# CH555-R0-1v0.net
KiCad netlist of a schematic drawn in Altium Designer
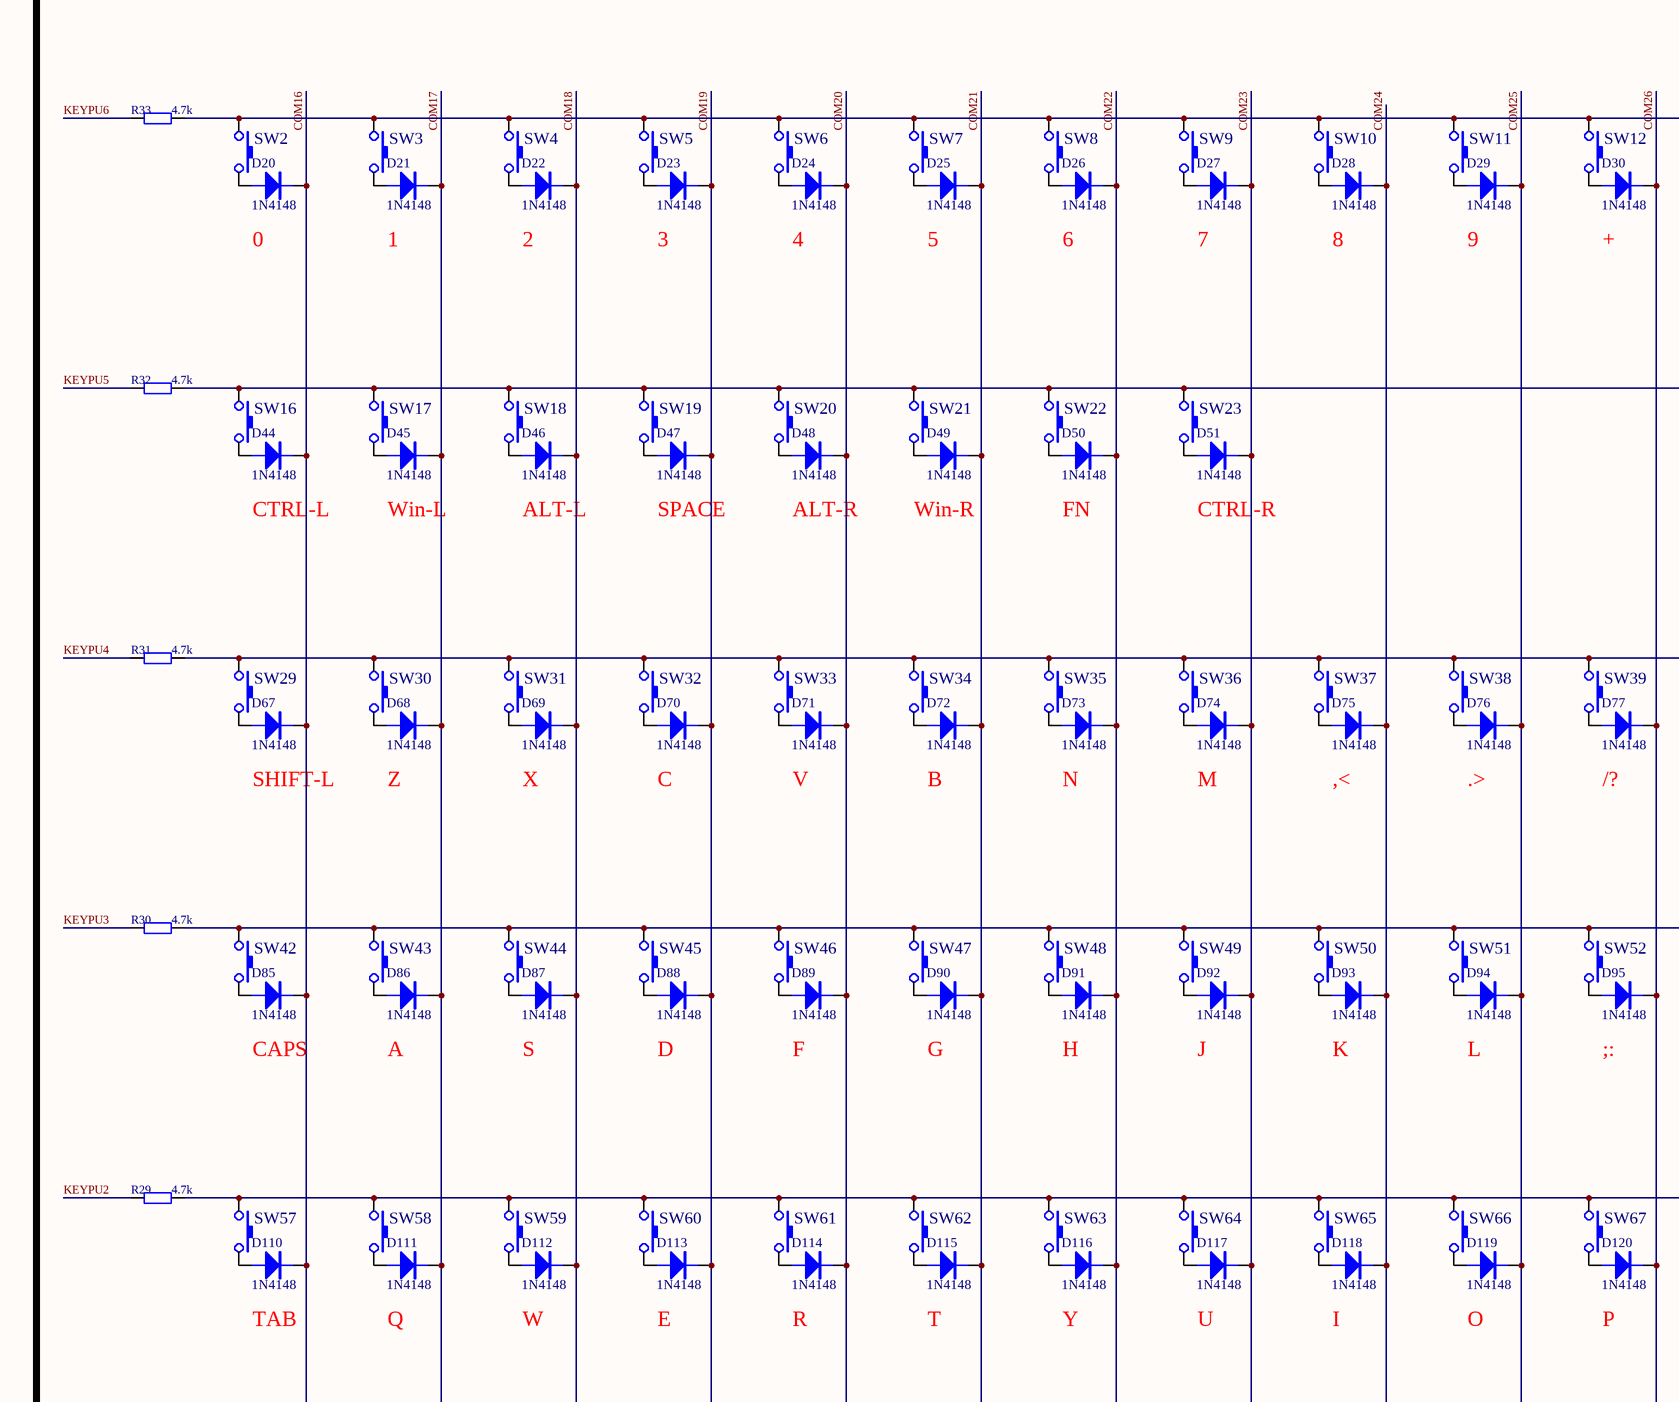
[diagram p0: CH555-R0-1v0.SchDoc, top left]
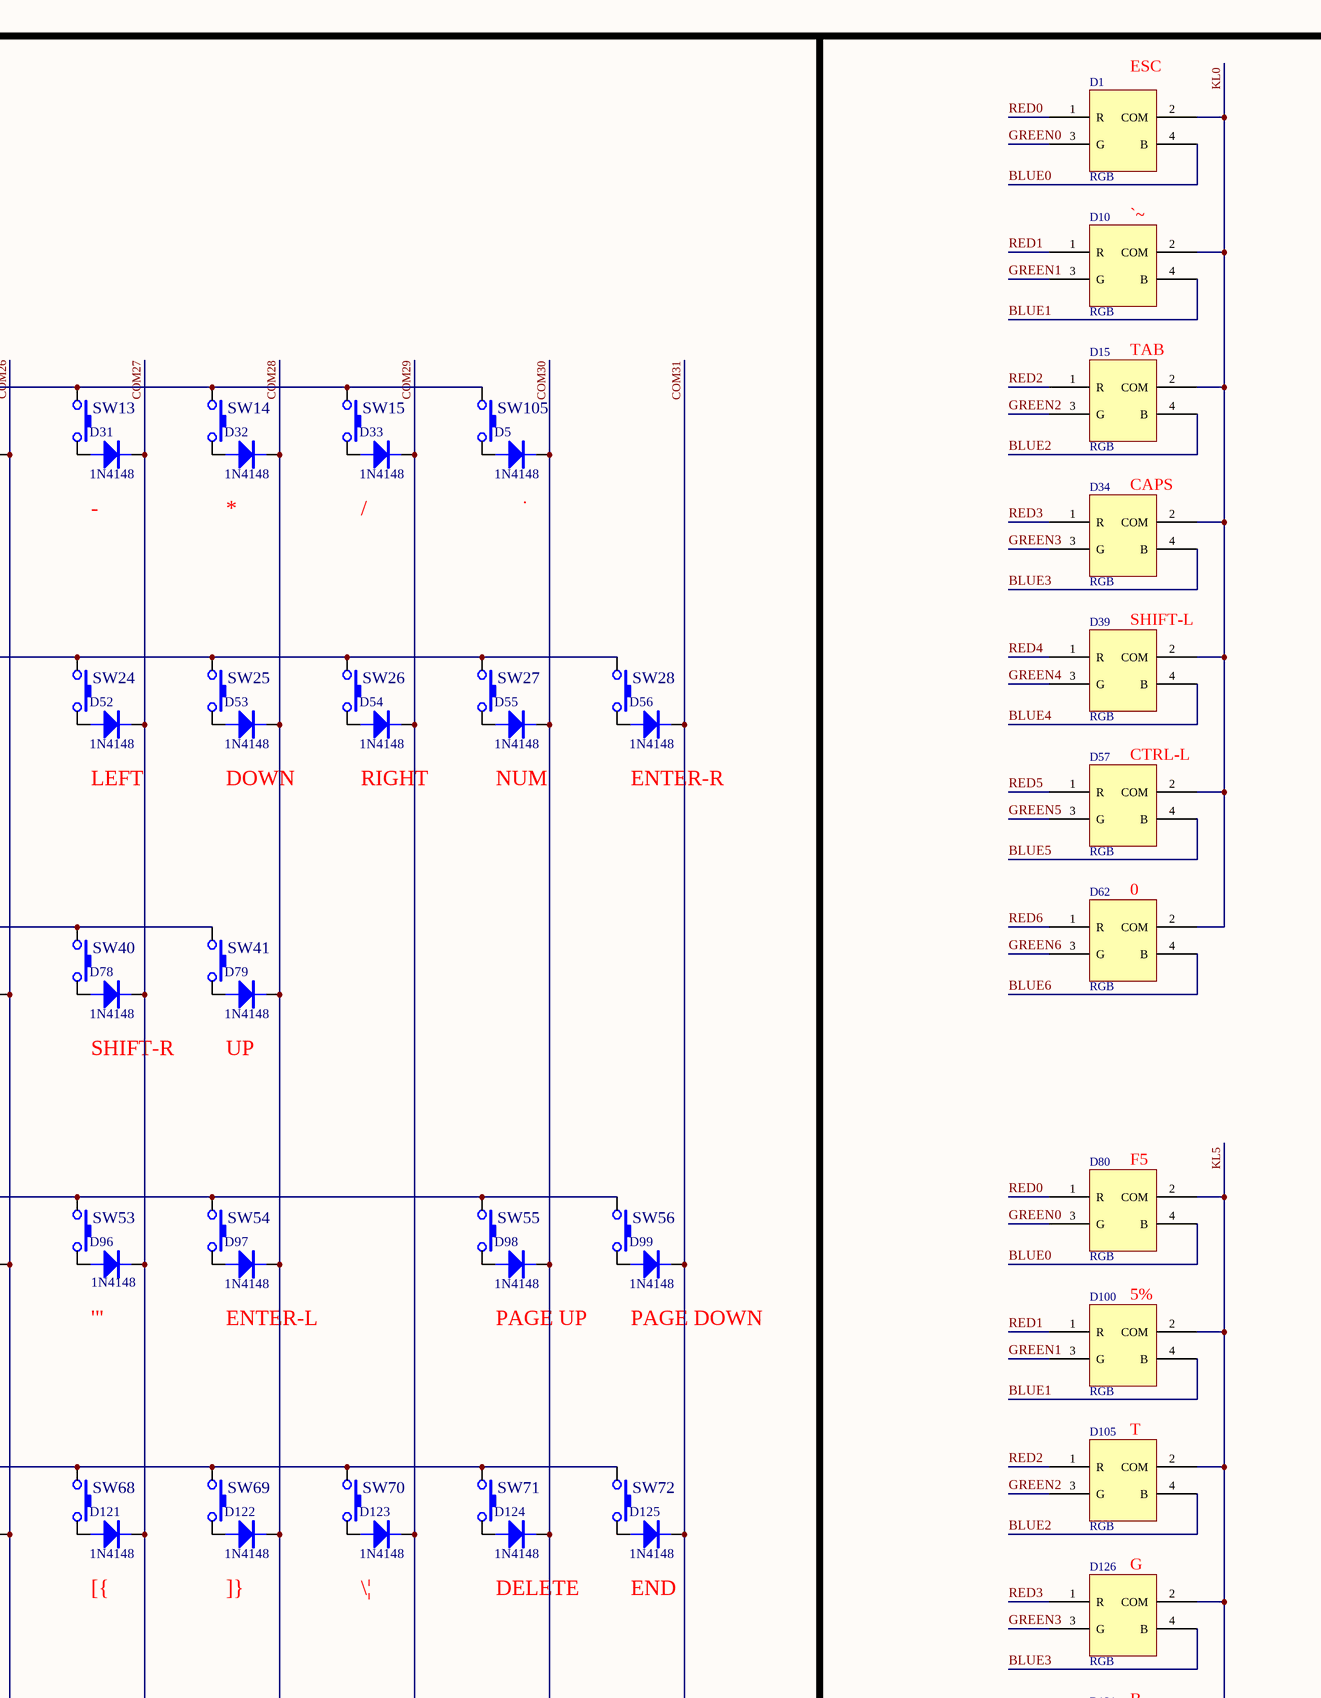
[diagram p1: CH555-R0-1v0.SchDoc, top middle]
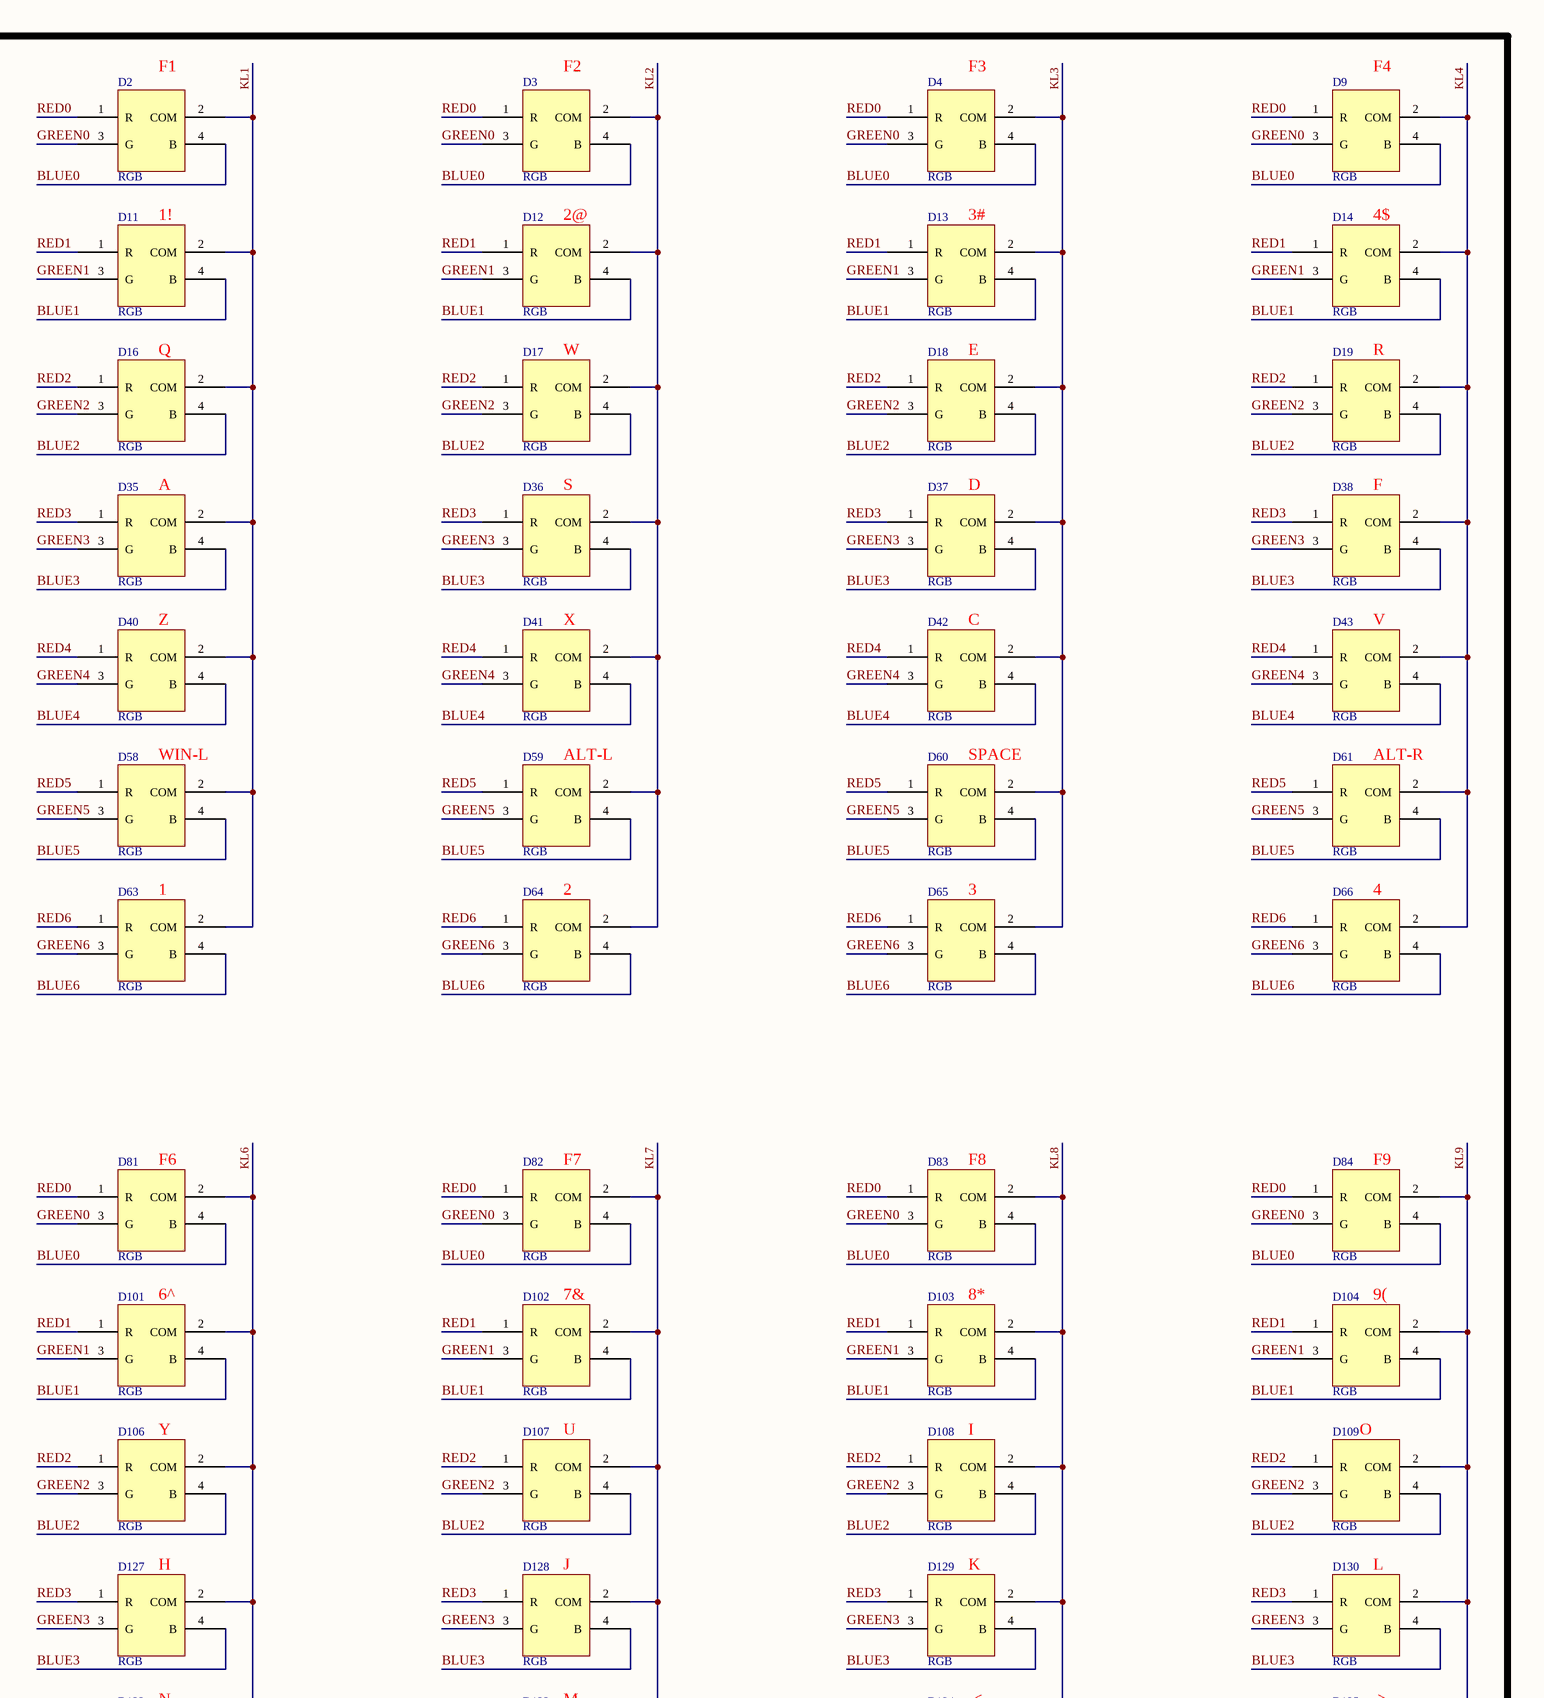
[diagram p2: CH555-R0-1v0.SchDoc, top right]
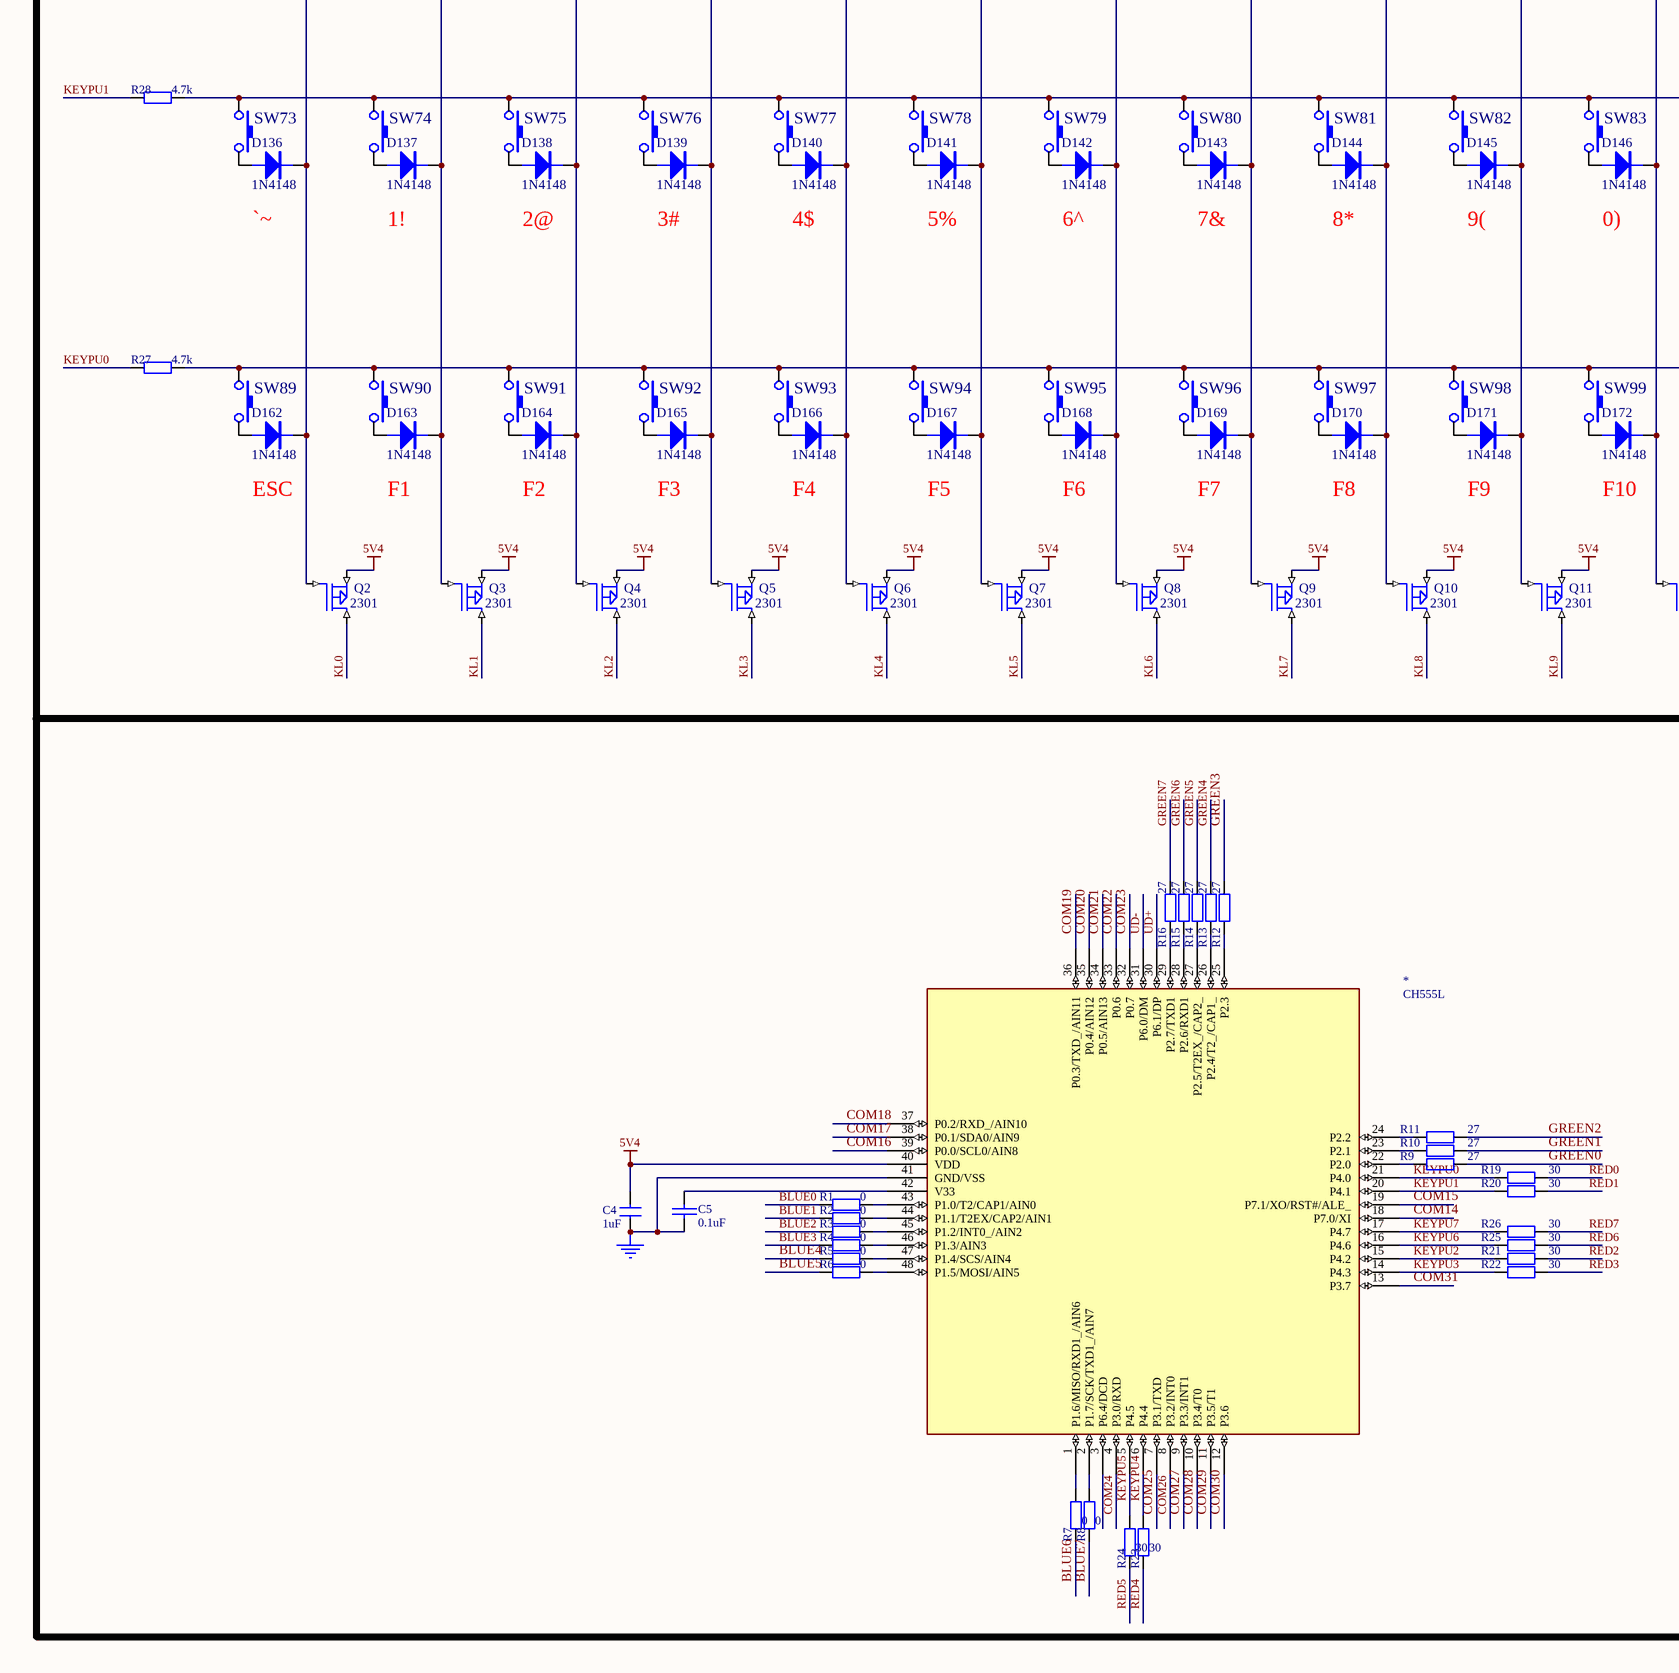
[diagram p3: CH555-R0-1v0.SchDoc, bottom left]
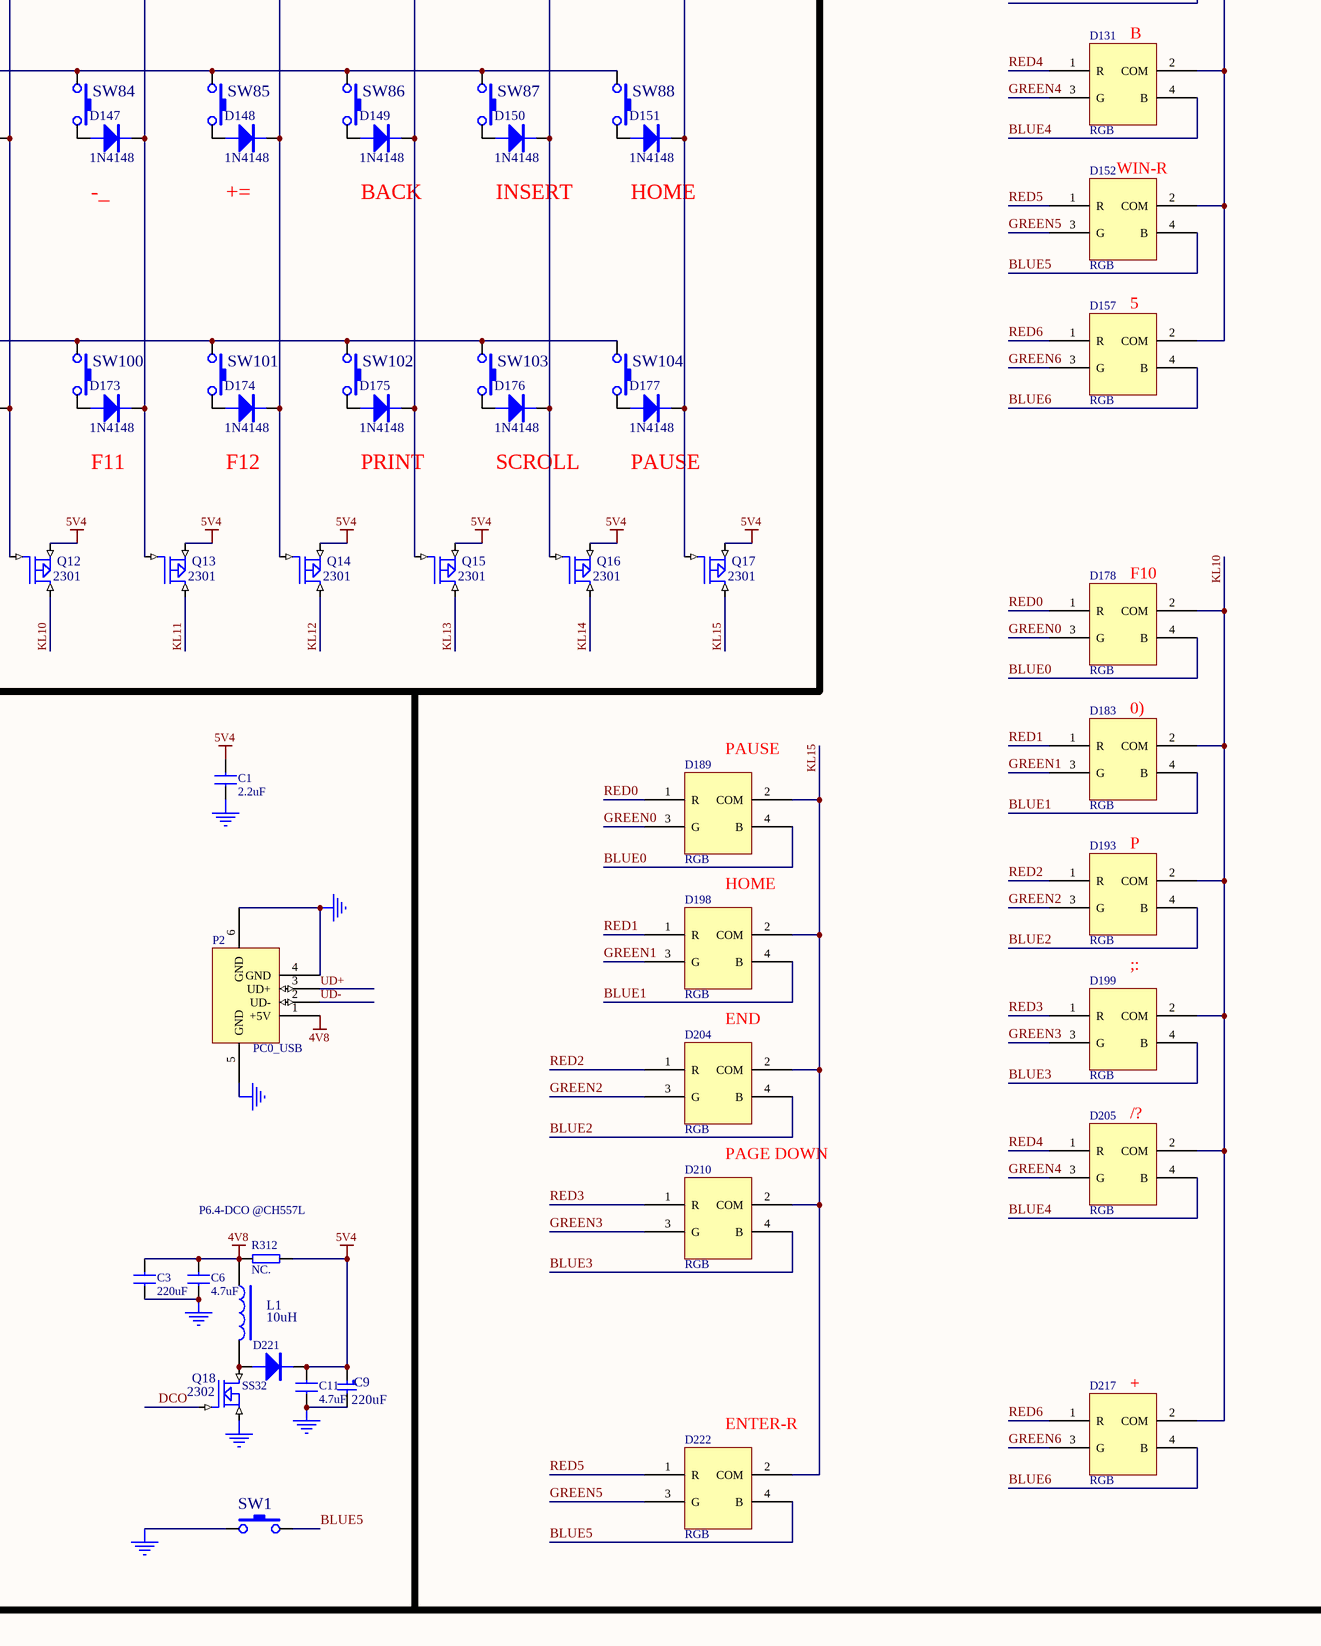
[diagram p4: CH555-R0-1v0.SchDoc, bottom middle]
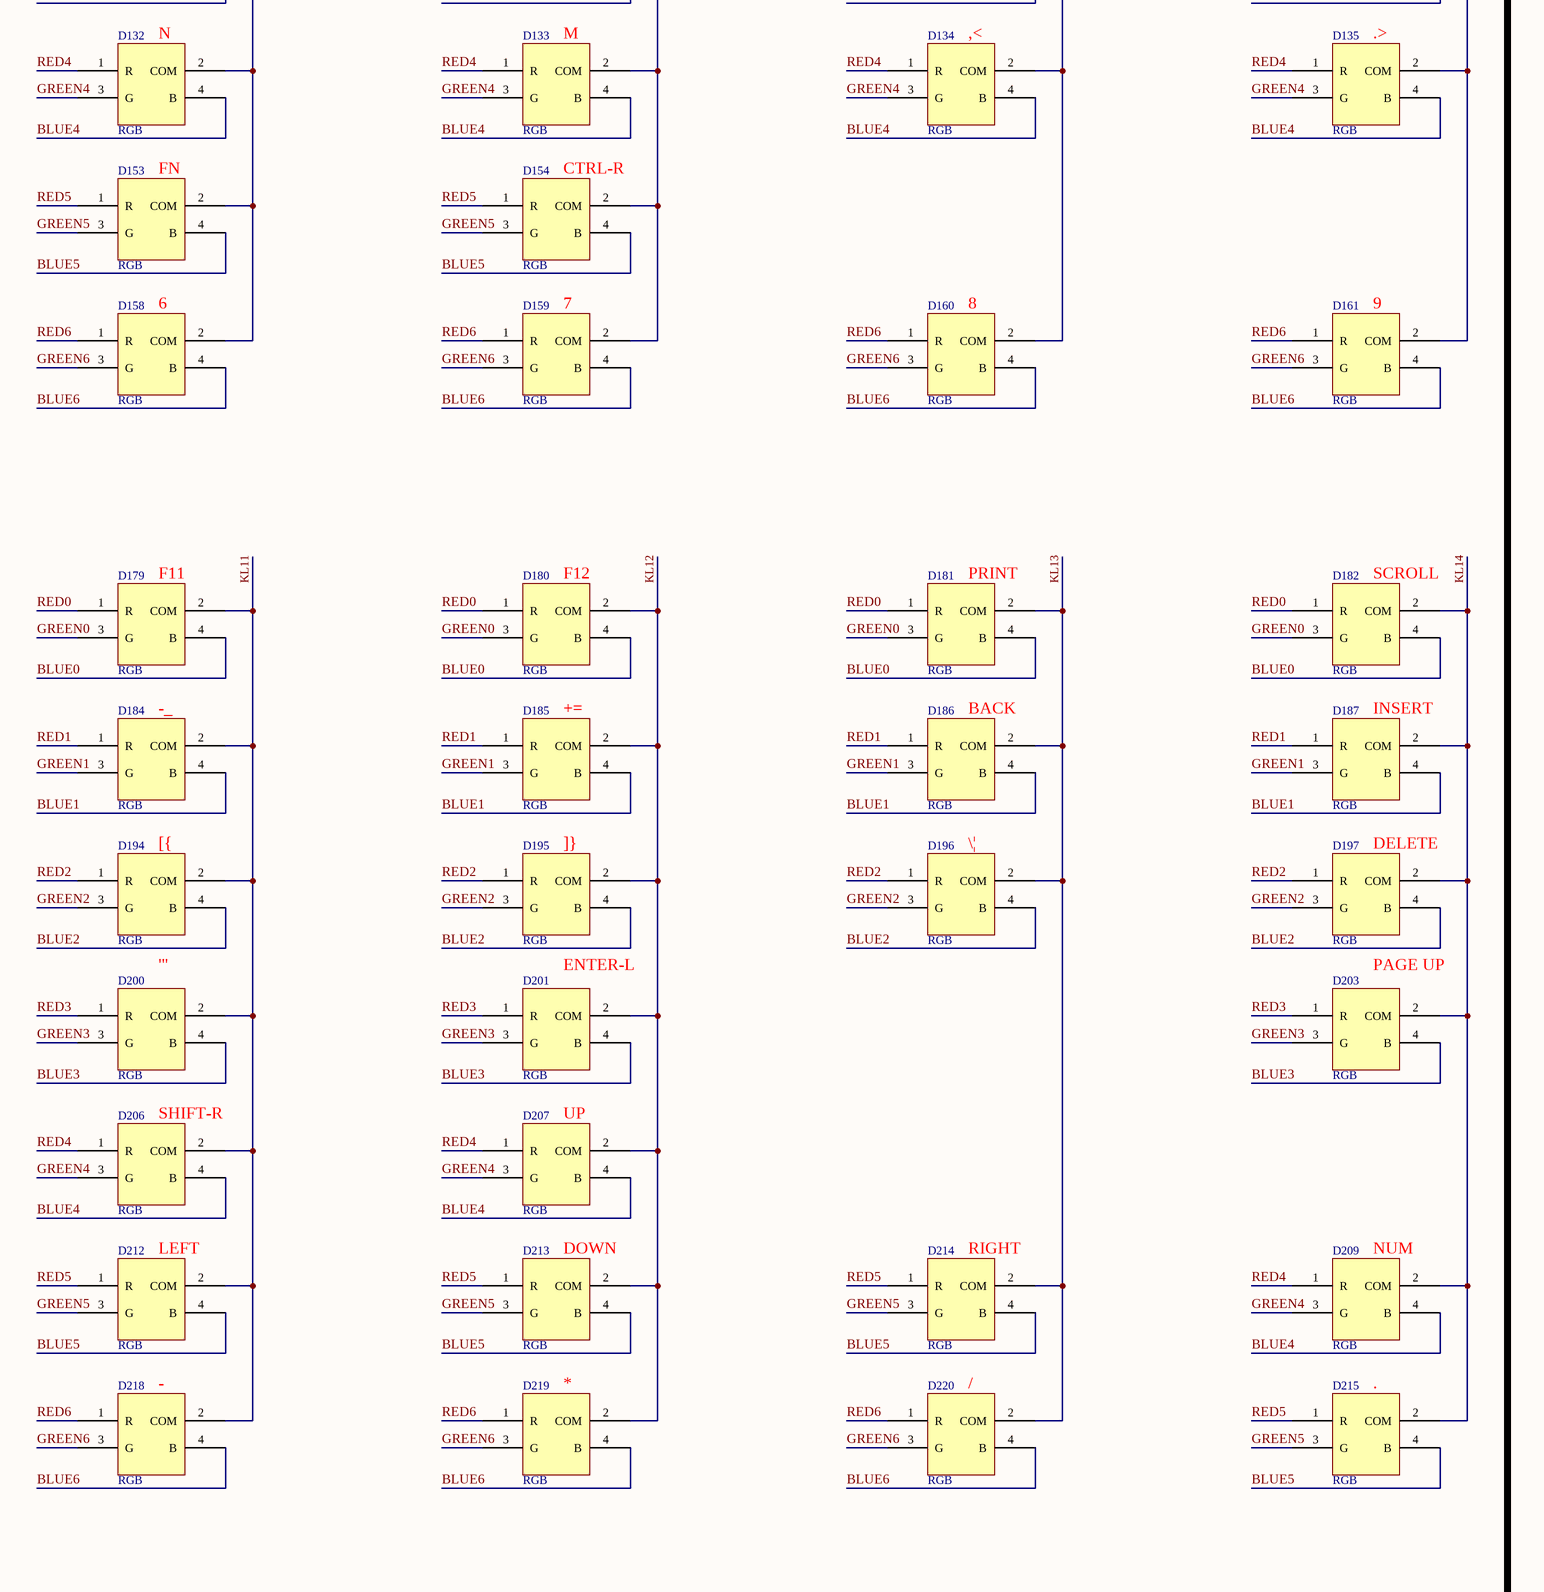
[diagram p5: CH555-R0-1v0.SchDoc, bottom right]

(export (version "E")
  (design (tool "Eeschema 10.0.6"))
  (components
    (comp (ref "*") (value "CH555L") (libsource (lib "WJ-CPU") (part "CH555L")))
    (comp (ref "C1")
      (value "2.2uF")
      (footprint "0603")
      (description "Capacitor")
      (libsource (lib "") (part "CAP_1"))
    )
    (comp (ref "C3")
      (value "220uF")
      (footprint "SMD_6.3x7.7mm")
      (description "Capacitor")
      (fields (field (name "Comment") "2.2uF"))
      (libsource (lib "") (part "CAP_1"))
    )
    (comp (ref "C4")
      (value "1uF")
      (footprint "0603")
      (description "Capacitor")
      (libsource (lib "") (part "CAP_1"))
    )
    (comp (ref "C5")
      (value "0.1uF")
      (footprint "0603")
      (description "Capacitor")
      (libsource (lib "*") (part "CAP"))
    )
    (comp (ref "C6")
      (value "4.7uF")
      (footprint "0603")
      (description "Capacitor")
      (fields (field (name "Comment") "2.2uF"))
      (libsource (lib "") (part "CAP_1"))
    )
    (comp (ref "C9")
      (value "220uF")
      (footprint "SMD_6.3x7.7mm")
      (libsource (lib "*") (part "Pro336.TMP_100u_11"))
    )
    (comp (ref "C11")
      (value "4.7uF")
      (footprint "0603")
      (description "Capacitor")
      (fields (field (name "Comment") "2.2uF"))
      (libsource (lib "") (part "CAP_1"))
    )
    (comp (ref "D1") (value "RGB") (footprint "RGB-2x5x5mm") (libsource (lib "*") (part "RGB")))
    (comp (ref "D2") (value "RGB") (footprint "RGB-2x5x5mm") (libsource (lib "*") (part "RGB")))
    (comp (ref "D3") (value "RGB") (footprint "RGB-2x5x5mm") (libsource (lib "*") (part "RGB")))
    (comp (ref "D4") (value "RGB") (footprint "RGB-2x5x5mm") (libsource (lib "*") (part "RGB")))
    (comp (ref "D5")
      (value "1N4148")
      (footprint "3216+")
      (description "Diode")
      (libsource (lib "*") (part "DIODE"))
    )
    (comp (ref "D9") (value "RGB") (footprint "RGB-2x5x5mm") (libsource (lib "*") (part "RGB")))
    (comp (ref "D10") (value "RGB") (footprint "RGB-2x5x5mm") (libsource (lib "*") (part "RGB")))
    (comp (ref "D11") (value "RGB") (footprint "RGB-2x5x5mm") (libsource (lib "*") (part "RGB")))
    (comp (ref "D12") (value "RGB") (footprint "RGB-2x5x5mm") (libsource (lib "*") (part "RGB")))
    (comp (ref "D13") (value "RGB") (footprint "RGB-2x5x5mm") (libsource (lib "*") (part "RGB")))
    (comp (ref "D14") (value "RGB") (footprint "RGB-2x5x5mm") (libsource (lib "*") (part "RGB")))
    (comp (ref "D15") (value "RGB") (footprint "RGB-2x5x5mm") (libsource (lib "*") (part "RGB")))
    (comp (ref "D16") (value "RGB") (footprint "RGB-2x5x5mm") (libsource (lib "*") (part "RGB")))
    (comp (ref "D17") (value "RGB") (footprint "RGB-2x5x5mm") (libsource (lib "*") (part "RGB")))
    (comp (ref "D18") (value "RGB") (footprint "RGB-2x5x5mm") (libsource (lib "*") (part "RGB")))
    (comp (ref "D19") (value "RGB") (footprint "RGB-2x5x5mm") (libsource (lib "*") (part "RGB")))
    (comp (ref "D20")
      (value "1N4148")
      (footprint "3216+")
      (description "Diode")
      (libsource (lib "*") (part "DIODE"))
    )
    (comp (ref "D21")
      (value "1N4148")
      (footprint "3216+")
      (description "Diode")
      (libsource (lib "*") (part "DIODE"))
    )
    (comp (ref "D22")
      (value "1N4148")
      (footprint "3216+")
      (description "Diode")
      (libsource (lib "*") (part "DIODE"))
    )
    (comp (ref "D23")
      (value "1N4148")
      (footprint "3216+")
      (description "Diode")
      (libsource (lib "*") (part "DIODE"))
    )
    (comp (ref "D24")
      (value "1N4148")
      (footprint "3216+")
      (description "Diode")
      (libsource (lib "*") (part "DIODE"))
    )
    (comp (ref "D25")
      (value "1N4148")
      (footprint "3216+")
      (description "Diode")
      (libsource (lib "*") (part "DIODE"))
    )
    (comp (ref "D26")
      (value "1N4148")
      (footprint "3216+")
      (description "Diode")
      (libsource (lib "*") (part "DIODE"))
    )
    (comp (ref "D27")
      (value "1N4148")
      (footprint "3216+")
      (description "Diode")
      (libsource (lib "*") (part "DIODE"))
    )
    (comp (ref "D28")
      (value "1N4148")
      (footprint "3216+")
      (description "Diode")
      (libsource (lib "*") (part "DIODE"))
    )
    (comp (ref "D29")
      (value "1N4148")
      (footprint "3216+")
      (description "Diode")
      (libsource (lib "*") (part "DIODE"))
    )
    (comp (ref "D30")
      (value "1N4148")
      (footprint "3216+")
      (description "Diode")
      (libsource (lib "*") (part "DIODE"))
    )
    (comp (ref "D31")
      (value "1N4148")
      (footprint "3216+")
      (description "Diode")
      (libsource (lib "*") (part "DIODE"))
    )
    (comp (ref "D32")
      (value "1N4148")
      (footprint "3216+")
      (description "Diode")
      (libsource (lib "*") (part "DIODE"))
    )
    (comp (ref "D33")
      (value "1N4148")
      (footprint "3216+")
      (description "Diode")
      (libsource (lib "*") (part "DIODE"))
    )
    (comp (ref "D34") (value "RGB") (footprint "RGB-2x5x5mm") (libsource (lib "*") (part "RGB")))
    (comp (ref "D35") (value "RGB") (footprint "RGB-2x5x5mm") (libsource (lib "*") (part "RGB")))
    (comp (ref "D36") (value "RGB") (footprint "RGB-2x5x5mm") (libsource (lib "*") (part "RGB")))
    (comp (ref "D37") (value "RGB") (footprint "RGB-2x5x5mm") (libsource (lib "*") (part "RGB")))
    (comp (ref "D38") (value "RGB") (footprint "RGB-2x5x5mm") (libsource (lib "*") (part "RGB")))
    (comp (ref "D39") (value "RGB") (footprint "RGB-2x5x5mm") (libsource (lib "*") (part "RGB")))
    (comp (ref "D40") (value "RGB") (footprint "RGB-2x5x5mm") (libsource (lib "*") (part "RGB")))
    (comp (ref "D41") (value "RGB") (footprint "RGB-2x5x5mm") (libsource (lib "*") (part "RGB")))
    (comp (ref "D42") (value "RGB") (footprint "RGB-2x5x5mm") (libsource (lib "*") (part "RGB")))
    (comp (ref "D43") (value "RGB") (footprint "RGB-2x5x5mm") (libsource (lib "*") (part "RGB")))
    (comp (ref "D44")
      (value "1N4148")
      (footprint "3216+")
      (description "Diode")
      (libsource (lib "*") (part "DIODE"))
    )
    (comp (ref "D45")
      (value "1N4148")
      (footprint "3216+")
      (description "Diode")
      (libsource (lib "*") (part "DIODE"))
    )
    (comp (ref "D46")
      (value "1N4148")
      (footprint "3216+")
      (description "Diode")
      (libsource (lib "*") (part "DIODE"))
    )
    (comp (ref "D47")
      (value "1N4148")
      (footprint "3216+")
      (description "Diode")
      (libsource (lib "*") (part "DIODE"))
    )
    (comp (ref "D48")
      (value "1N4148")
      (footprint "3216+")
      (description "Diode")
      (libsource (lib "*") (part "DIODE"))
    )
    (comp (ref "D49")
      (value "1N4148")
      (footprint "3216+")
      (description "Diode")
      (libsource (lib "*") (part "DIODE"))
    )
    (comp (ref "D50")
      (value "1N4148")
      (footprint "3216+")
      (description "Diode")
      (libsource (lib "*") (part "DIODE"))
    )
    (comp (ref "D51")
      (value "1N4148")
      (footprint "3216+")
      (description "Diode")
      (libsource (lib "*") (part "DIODE"))
    )
    (comp (ref "D52")
      (value "1N4148")
      (footprint "3216+")
      (description "Diode")
      (libsource (lib "*") (part "DIODE"))
    )
    (comp (ref "D53")
      (value "1N4148")
      (footprint "3216+")
      (description "Diode")
      (libsource (lib "*") (part "DIODE"))
    )
    (comp (ref "D54")
      (value "1N4148")
      (footprint "3216+")
      (description "Diode")
      (libsource (lib "*") (part "DIODE"))
    )
    (comp (ref "D55")
      (value "1N4148")
      (footprint "3216+")
      (description "Diode")
      (libsource (lib "*") (part "DIODE"))
    )
    (comp (ref "D56")
      (value "1N4148")
      (footprint "3216+")
      (description "Diode")
      (libsource (lib "*") (part "DIODE"))
    )
    (comp (ref "D57") (value "RGB") (footprint "RGB-2x5x5mm") (libsource (lib "*") (part "RGB")))
    (comp (ref "D58") (value "RGB") (footprint "RGB-2x5x5mm") (libsource (lib "*") (part "RGB")))
    (comp (ref "D59") (value "RGB") (footprint "RGB-2x5x5mm") (libsource (lib "*") (part "RGB")))
    (comp (ref "D60") (value "RGB") (footprint "RGB-2x5x5mm") (libsource (lib "*") (part "RGB")))
    (comp (ref "D61") (value "RGB") (footprint "RGB-2x5x5mm") (libsource (lib "*") (part "RGB")))
    (comp (ref "D62") (value "RGB") (footprint "RGB-2x5x5mm") (libsource (lib "*") (part "RGB")))
    (comp (ref "D63") (value "RGB") (footprint "RGB-2x5x5mm") (libsource (lib "*") (part "RGB")))
    (comp (ref "D64") (value "RGB") (footprint "RGB-2x5x5mm") (libsource (lib "*") (part "RGB")))
    (comp (ref "D65") (value "RGB") (footprint "RGB-2x5x5mm") (libsource (lib "*") (part "RGB")))
    (comp (ref "D66") (value "RGB") (footprint "RGB-2x5x5mm") (libsource (lib "*") (part "RGB")))
    (comp (ref "D67")
      (value "1N4148")
      (footprint "3216+")
      (description "Diode")
      (libsource (lib "*") (part "DIODE"))
    )
    (comp (ref "D68")
      (value "1N4148")
      (footprint "3216+")
      (description "Diode")
      (libsource (lib "*") (part "DIODE"))
    )
    (comp (ref "D69")
      (value "1N4148")
      (footprint "3216+")
      (description "Diode")
      (libsource (lib "*") (part "DIODE"))
    )
    (comp (ref "D70")
      (value "1N4148")
      (footprint "3216+")
      (description "Diode")
      (libsource (lib "*") (part "DIODE"))
    )
    (comp (ref "D71")
      (value "1N4148")
      (footprint "3216+")
      (description "Diode")
      (libsource (lib "*") (part "DIODE"))
    )
    (comp (ref "D72")
      (value "1N4148")
      (footprint "3216+")
      (description "Diode")
      (libsource (lib "*") (part "DIODE"))
    )
    (comp (ref "D73")
      (value "1N4148")
      (footprint "3216+")
      (description "Diode")
      (libsource (lib "*") (part "DIODE"))
    )
    (comp (ref "D74")
      (value "1N4148")
      (footprint "3216+")
      (description "Diode")
      (libsource (lib "*") (part "DIODE"))
    )
    (comp (ref "D75")
      (value "1N4148")
      (footprint "3216+")
      (description "Diode")
      (libsource (lib "*") (part "DIODE"))
    )
    (comp (ref "D76")
      (value "1N4148")
      (footprint "3216+")
      (description "Diode")
      (libsource (lib "*") (part "DIODE"))
    )
    (comp (ref "D77")
      (value "1N4148")
      (footprint "3216+")
      (description "Diode")
      (libsource (lib "*") (part "DIODE"))
    )
    (comp (ref "D78")
      (value "1N4148")
      (footprint "3216+")
      (description "Diode")
      (libsource (lib "*") (part "DIODE"))
    )
    (comp (ref "D79")
      (value "1N4148")
      (footprint "3216+")
      (description "Diode")
      (libsource (lib "*") (part "DIODE"))
    )
    (comp (ref "D80") (value "RGB") (footprint "RGB-2x5x5mm") (libsource (lib "*") (part "RGB")))
    (comp (ref "D81") (value "RGB") (footprint "RGB-2x5x5mm") (libsource (lib "*") (part "RGB")))
    (comp (ref "D82") (value "RGB") (footprint "RGB-2x5x5mm") (libsource (lib "*") (part "RGB")))
    (comp (ref "D83") (value "RGB") (footprint "RGB-2x5x5mm") (libsource (lib "*") (part "RGB")))
    (comp (ref "D84") (value "RGB") (footprint "RGB-2x5x5mm") (libsource (lib "*") (part "RGB")))
    (comp (ref "D85")
      (value "1N4148")
      (footprint "3216+")
      (description "Diode")
      (libsource (lib "*") (part "DIODE"))
    )
    (comp (ref "D86")
      (value "1N4148")
      (footprint "3216+")
      (description "Diode")
      (libsource (lib "*") (part "DIODE"))
    )
    (comp (ref "D87")
      (value "1N4148")
      (footprint "3216+")
      (description "Diode")
      (libsource (lib "*") (part "DIODE"))
    )
    (comp (ref "D88")
      (value "1N4148")
      (footprint "3216+")
      (description "Diode")
      (libsource (lib "*") (part "DIODE"))
    )
    (comp (ref "D89")
      (value "1N4148")
      (footprint "3216+")
      (description "Diode")
      (libsource (lib "*") (part "DIODE"))
    )
    (comp (ref "D90")
      (value "1N4148")
      (footprint "3216+")
      (description "Diode")
      (libsource (lib "*") (part "DIODE"))
    )
    (comp (ref "D91")
      (value "1N4148")
      (footprint "3216+")
      (description "Diode")
      (libsource (lib "*") (part "DIODE"))
    )
    (comp (ref "D92")
      (value "1N4148")
      (footprint "3216+")
      (description "Diode")
      (libsource (lib "*") (part "DIODE"))
    )
    (comp (ref "D93")
      (value "1N4148")
      (footprint "3216+")
      (description "Diode")
      (libsource (lib "*") (part "DIODE"))
    )
    (comp (ref "D94")
      (value "1N4148")
      (footprint "3216+")
      (description "Diode")
      (libsource (lib "*") (part "DIODE"))
    )
    (comp (ref "D95")
      (value "1N4148")
      (footprint "3216+")
      (description "Diode")
      (libsource (lib "*") (part "DIODE"))
    )
    (comp (ref "D96")
      (value "1N4148")
      (footprint "3216+")
      (description "Diode")
      (libsource (lib "*") (part "DIODE"))
    )
    (comp (ref "D97")
      (value "1N4148")
      (footprint "3216+")
      (description "Diode")
      (libsource (lib "*") (part "DIODE"))
    )
    (comp (ref "D98")
      (value "1N4148")
      (footprint "3216+")
      (description "Diode")
      (libsource (lib "*") (part "DIODE"))
    )
    (comp (ref "D99")
      (value "1N4148")
      (footprint "3216+")
      (description "Diode")
      (libsource (lib "*") (part "DIODE"))
    )
    (comp (ref "D100") (value "RGB") (footprint "RGB-2x5x5mm") (libsource (lib "*") (part "RGB")))
    (comp (ref "D101") (value "RGB") (footprint "RGB-2x5x5mm") (libsource (lib "*") (part "RGB")))
    (comp (ref "D102") (value "RGB") (footprint "RGB-2x5x5mm") (libsource (lib "*") (part "RGB")))
    (comp (ref "D103") (value "RGB") (footprint "RGB-2x5x5mm") (libsource (lib "*") (part "RGB")))
    (comp (ref "D104") (value "RGB") (footprint "RGB-2x5x5mm") (libsource (lib "*") (part "RGB")))
    (comp (ref "D105") (value "RGB") (footprint "RGB-2x5x5mm") (libsource (lib "*") (part "RGB")))
    (comp (ref "D106") (value "RGB") (footprint "RGB-2x5x5mm") (libsource (lib "*") (part "RGB")))
    (comp (ref "D107") (value "RGB") (footprint "RGB-2x5x5mm") (libsource (lib "*") (part "RGB")))
    (comp (ref "D108") (value "RGB") (footprint "RGB-2x5x5mm") (libsource (lib "*") (part "RGB")))
    (comp (ref "D109") (value "RGB") (footprint "RGB-2x5x5mm") (libsource (lib "*") (part "RGB")))
    (comp (ref "D110")
      (value "1N4148")
      (footprint "3216+")
      (description "Diode")
      (libsource (lib "*") (part "DIODE"))
    )
    (comp (ref "D111")
      (value "1N4148")
      (footprint "3216+")
      (description "Diode")
      (libsource (lib "*") (part "DIODE"))
    )
    (comp (ref "D112")
      (value "1N4148")
      (footprint "3216+")
      (description "Diode")
      (libsource (lib "*") (part "DIODE"))
    )
    (comp (ref "D113")
      (value "1N4148")
      (footprint "3216+")
      (description "Diode")
      (libsource (lib "*") (part "DIODE"))
    )
    (comp (ref "D114")
      (value "1N4148")
      (footprint "3216+")
      (description "Diode")
      (libsource (lib "*") (part "DIODE"))
    )
    (comp (ref "D115")
      (value "1N4148")
      (footprint "3216+")
      (description "Diode")
      (libsource (lib "*") (part "DIODE"))
    )
    (comp (ref "D116")
      (value "1N4148")
      (footprint "3216+")
      (description "Diode")
      (libsource (lib "*") (part "DIODE"))
    )
    (comp (ref "D117")
      (value "1N4148")
      (footprint "3216+")
      (description "Diode")
      (libsource (lib "*") (part "DIODE"))
    )
    (comp (ref "D118")
      (value "1N4148")
      (footprint "3216+")
      (description "Diode")
      (libsource (lib "*") (part "DIODE"))
    )
    (comp (ref "D119")
      (value "1N4148")
      (footprint "3216+")
      (description "Diode")
      (libsource (lib "*") (part "DIODE"))
    )
    (comp (ref "D120")
      (value "1N4148")
      (footprint "3216+")
      (description "Diode")
      (libsource (lib "*") (part "DIODE"))
    )
    (comp (ref "D121")
      (value "1N4148")
      (footprint "3216+")
      (description "Diode")
      (libsource (lib "*") (part "DIODE"))
    )
    (comp (ref "D122")
      (value "1N4148")
      (footprint "3216+")
      (description "Diode")
      (libsource (lib "*") (part "DIODE"))
    )
    (comp (ref "D123")
      (value "1N4148")
      (footprint "3216+")
      (description "Diode")
      (libsource (lib "*") (part "DIODE"))
    )
    (comp (ref "D124")
      (value "1N4148")
      (footprint "3216+")
      (description "Diode")
      (libsource (lib "*") (part "DIODE"))
    )
    (comp (ref "D125")
      (value "1N4148")
      (footprint "3216+")
      (description "Diode")
      (libsource (lib "*") (part "DIODE"))
    )
    (comp (ref "D126") (value "RGB") (footprint "RGB-2x5x5mm") (libsource (lib "*") (part "RGB")))
    (comp (ref "D127") (value "RGB") (footprint "RGB-2x5x5mm") (libsource (lib "*") (part "RGB")))
    (comp (ref "D128") (value "RGB") (footprint "RGB-2x5x5mm") (libsource (lib "*") (part "RGB")))
    (comp (ref "D129") (value "RGB") (footprint "RGB-2x5x5mm") (libsource (lib "*") (part "RGB")))
    (comp (ref "D130") (value "RGB") (footprint "RGB-2x5x5mm") (libsource (lib "*") (part "RGB")))
    (comp (ref "D131") (value "RGB") (footprint "RGB-2x5x5mm") (libsource (lib "*") (part "RGB")))
    (comp (ref "D132") (value "RGB") (footprint "RGB-2x5x5mm") (libsource (lib "*") (part "RGB")))
    (comp (ref "D133") (value "RGB") (footprint "RGB-2x5x5mm") (libsource (lib "*") (part "RGB")))
    (comp (ref "D134") (value "RGB") (footprint "RGB-2x5x5mm") (libsource (lib "*") (part "RGB")))
    (comp (ref "D135") (value "RGB") (footprint "RGB-2x5x5mm") (libsource (lib "*") (part "RGB")))
    (comp (ref "D136")
      (value "1N4148")
      (footprint "3216+")
      (description "Diode")
      (libsource (lib "*") (part "DIODE"))
    )
    (comp (ref "D137")
      (value "1N4148")
      (footprint "3216+")
      (description "Diode")
      (libsource (lib "*") (part "DIODE"))
    )
    (comp (ref "D138")
      (value "1N4148")
      (footprint "3216+")
      (description "Diode")
      (libsource (lib "*") (part "DIODE"))
    )
    (comp (ref "D139")
      (value "1N4148")
      (footprint "3216+")
      (description "Diode")
      (libsource (lib "*") (part "DIODE"))
    )
    (comp (ref "D140")
      (value "1N4148")
      (footprint "3216+")
      (description "Diode")
      (libsource (lib "*") (part "DIODE"))
    )
    (comp (ref "D141")
      (value "1N4148")
      (footprint "3216+")
      (description "Diode")
      (libsource (lib "*") (part "DIODE"))
    )
    (comp (ref "D142")
      (value "1N4148")
      (footprint "3216+")
      (description "Diode")
      (libsource (lib "*") (part "DIODE"))
    )
    (comp (ref "D143")
      (value "1N4148")
      (footprint "3216+")
      (description "Diode")
      (libsource (lib "*") (part "DIODE"))
    )
    (comp (ref "D144")
      (value "1N4148")
      (footprint "3216+")
      (description "Diode")
      (libsource (lib "*") (part "DIODE"))
    )
    (comp (ref "D145")
      (value "1N4148")
      (footprint "3216+")
      (description "Diode")
      (libsource (lib "*") (part "DIODE"))
    )
    (comp (ref "D146")
      (value "1N4148")
      (footprint "3216+")
      (description "Diode")
      (libsource (lib "*") (part "DIODE"))
    )
    (comp (ref "D147")
      (value "1N4148")
      (footprint "3216+")
      (description "Diode")
      (libsource (lib "*") (part "DIODE"))
    )
    (comp (ref "D148")
      (value "1N4148")
      (footprint "3216+")
      (description "Diode")
      (libsource (lib "*") (part "DIODE"))
    )
    (comp (ref "D149")
      (value "1N4148")
      (footprint "3216+")
      (description "Diode")
      (libsource (lib "*") (part "DIODE"))
    )
    (comp (ref "D150")
      (value "1N4148")
      (footprint "3216+")
      (description "Diode")
      (libsource (lib "*") (part "DIODE"))
    )
    (comp (ref "D151")
      (value "1N4148")
      (footprint "3216+")
      (description "Diode")
      (libsource (lib "*") (part "DIODE"))
    )
    (comp (ref "D152") (value "RGB") (footprint "RGB-2x5x5mm") (libsource (lib "*") (part "RGB")))
    (comp (ref "D153") (value "RGB") (footprint "RGB-2x5x5mm") (libsource (lib "*") (part "RGB")))
    (comp (ref "D154") (value "RGB") (footprint "RGB-2x5x5mm") (libsource (lib "*") (part "RGB")))
    (comp (ref "D157") (value "RGB") (footprint "RGB-2x5x5mm") (libsource (lib "*") (part "RGB")))
    (comp (ref "D158") (value "RGB") (footprint "RGB-2x5x5mm") (libsource (lib "*") (part "RGB")))
    (comp (ref "D159") (value "RGB") (footprint "RGB-2x5x5mm") (libsource (lib "*") (part "RGB")))
    (comp (ref "D160") (value "RGB") (footprint "RGB-2x5x5mm") (libsource (lib "*") (part "RGB")))
    (comp (ref "D161") (value "RGB") (footprint "RGB-2x5x5mm") (libsource (lib "*") (part "RGB")))
    (comp (ref "D162")
      (value "1N4148")
      (footprint "3216+")
      (description "Diode")
      (libsource (lib "*") (part "DIODE"))
    )
    (comp (ref "D163")
      (value "1N4148")
      (footprint "3216+")
      (description "Diode")
      (libsource (lib "*") (part "DIODE"))
    )
    (comp (ref "D164")
      (value "1N4148")
      (footprint "3216+")
      (description "Diode")
      (libsource (lib "*") (part "DIODE"))
    )
    (comp (ref "D165")
      (value "1N4148")
      (footprint "3216+")
      (description "Diode")
      (libsource (lib "*") (part "DIODE"))
    )
    (comp (ref "D166")
      (value "1N4148")
      (footprint "3216+")
      (description "Diode")
      (libsource (lib "*") (part "DIODE"))
    )
    (comp (ref "D167")
      (value "1N4148")
      (footprint "3216+")
      (description "Diode")
      (libsource (lib "*") (part "DIODE"))
    )
    (comp (ref "D168")
      (value "1N4148")
      (footprint "3216+")
      (description "Diode")
      (libsource (lib "*") (part "DIODE"))
    )
    (comp (ref "D169")
      (value "1N4148")
      (footprint "3216+")
      (description "Diode")
      (libsource (lib "*") (part "DIODE"))
    )
    (comp (ref "D170")
      (value "1N4148")
      (footprint "3216+")
      (description "Diode")
      (libsource (lib "*") (part "DIODE"))
    )
    (comp (ref "D171")
      (value "1N4148")
      (footprint "3216+")
      (description "Diode")
      (libsource (lib "*") (part "DIODE"))
    )
    (comp (ref "D172")
      (value "1N4148")
      (footprint "3216+")
      (description "Diode")
      (libsource (lib "*") (part "DIODE"))
    )
    (comp (ref "D173")
      (value "1N4148")
      (footprint "3216+")
      (description "Diode")
      (libsource (lib "*") (part "DIODE"))
    )
    (comp (ref "D174")
      (value "1N4148")
      (footprint "3216+")
      (description "Diode")
      (libsource (lib "*") (part "DIODE"))
    )
    (comp (ref "D175")
      (value "1N4148")
      (footprint "3216+")
      (description "Diode")
      (libsource (lib "*") (part "DIODE"))
    )
    (comp (ref "D176")
      (value "1N4148")
      (footprint "3216+")
      (description "Diode")
      (libsource (lib "*") (part "DIODE"))
    )
    (comp (ref "D177")
      (value "1N4148")
      (footprint "3216+")
      (description "Diode")
      (libsource (lib "*") (part "DIODE"))
    )
    (comp (ref "D178") (value "RGB") (footprint "RGB-2x5x5mm") (libsource (lib "*") (part "RGB")))
    (comp (ref "D179") (value "RGB") (footprint "RGB-2x5x5mm") (libsource (lib "*") (part "RGB")))
    (comp (ref "D180") (value "RGB") (footprint "RGB-2x5x5mm") (libsource (lib "*") (part "RGB")))
    (comp (ref "D181") (value "RGB") (footprint "RGB-2x5x5mm") (libsource (lib "*") (part "RGB")))
    (comp (ref "D182") (value "RGB") (footprint "RGB-2x5x5mm") (libsource (lib "*") (part "RGB")))
    (comp (ref "D183") (value "RGB") (footprint "RGB-2x5x5mm") (libsource (lib "*") (part "RGB")))
    (comp (ref "D184") (value "RGB") (footprint "RGB-2x5x5mm") (libsource (lib "*") (part "RGB")))
    (comp (ref "D185") (value "RGB") (footprint "RGB-2x5x5mm") (libsource (lib "*") (part "RGB")))
    (comp (ref "D186") (value "RGB") (footprint "RGB-2x5x5mm") (libsource (lib "*") (part "RGB")))
    (comp (ref "D187") (value "RGB") (footprint "RGB-2x5x5mm") (libsource (lib "*") (part "RGB")))
    (comp (ref "D189") (value "RGB") (footprint "RGB-2x5x5mm") (libsource (lib "*") (part "RGB")))
    (comp (ref "D193") (value "RGB") (footprint "RGB-2x5x5mm") (libsource (lib "*") (part "RGB")))
    (comp (ref "D194") (value "RGB") (footprint "RGB-2x5x5mm") (libsource (lib "*") (part "RGB")))
    (comp (ref "D195") (value "RGB") (footprint "RGB-2x5x5mm") (libsource (lib "*") (part "RGB")))
    (comp (ref "D196") (value "RGB") (footprint "RGB-2x5x5mm") (libsource (lib "*") (part "RGB")))
    (comp (ref "D197") (value "RGB") (footprint "RGB-2x5x5mm") (libsource (lib "*") (part "RGB")))
    (comp (ref "D198") (value "RGB") (footprint "RGB-2x5x5mm") (libsource (lib "*") (part "RGB")))
    (comp (ref "D199") (value "RGB") (footprint "RGB-2x5x5mm") (libsource (lib "*") (part "RGB")))
    (comp (ref "D200") (value "RGB") (footprint "RGB-2x5x5mm") (libsource (lib "*") (part "RGB")))
    (comp (ref "D201") (value "RGB") (footprint "RGB-2x5x5mm") (libsource (lib "*") (part "RGB")))
    (comp (ref "D203") (value "RGB") (footprint "RGB-2x5x5mm") (libsource (lib "*") (part "RGB")))
    (comp (ref "D204") (value "RGB") (footprint "RGB-2x5x5mm") (libsource (lib "*") (part "RGB")))
    (comp (ref "D205") (value "RGB") (footprint "RGB-2x5x5mm") (libsource (lib "*") (part "RGB")))
    (comp (ref "D206") (value "RGB") (footprint "RGB-2x5x5mm") (libsource (lib "*") (part "RGB")))
    (comp (ref "D207") (value "RGB") (footprint "RGB-2x5x5mm") (libsource (lib "*") (part "RGB")))
    (comp (ref "D209") (value "RGB") (footprint "RGB-2x5x5mm") (libsource (lib "*") (part "RGB")))
    (comp (ref "D210") (value "RGB") (footprint "RGB-2x5x5mm") (libsource (lib "*") (part "RGB")))
    (comp (ref "D212") (value "RGB") (footprint "RGB-2x5x5mm") (libsource (lib "*") (part "RGB")))
    (comp (ref "D213") (value "RGB") (footprint "RGB-2x5x5mm") (libsource (lib "*") (part "RGB")))
    (comp (ref "D214") (value "RGB") (footprint "RGB-2x5x5mm") (libsource (lib "*") (part "RGB")))
    (comp (ref "D215") (value "RGB") (footprint "RGB-2x5x5mm") (libsource (lib "*") (part "RGB")))
    (comp (ref "D217") (value "RGB") (footprint "RGB-2x5x5mm") (libsource (lib "*") (part "RGB")))
    (comp (ref "D218") (value "RGB") (footprint "RGB-2x5x5mm") (libsource (lib "*") (part "RGB")))
    (comp (ref "D219") (value "RGB") (footprint "RGB-2x5x5mm") (libsource (lib "*") (part "RGB")))
    (comp (ref "D220") (value "RGB") (footprint "RGB-2x5x5mm") (libsource (lib "*") (part "RGB")))
    (comp (ref "D221")
      (value "SS32")
      (footprint "7227+")
      (description "Diode")
      (libsource (lib "*") (part "DIODE"))
    )
    (comp (ref "D222") (value "RGB") (footprint "RGB-2x5x5mm") (libsource (lib "*") (part "RGB")))
    (comp (ref "L1") (value "10uH") (footprint "L3.3") (libsource (lib "*") (part "INDUCTOR2")))
    (comp (ref "P2")
      (value "PC0_USB")
      (footprint "USBA-L")
      (description "USB Port")
      (libsource (lib "*") (part "USB"))
    )
    (comp (ref "Q2")
      (value "2301")
      (footprint "SOT23")
      (description "P-MOSFET")
      (libsource (lib "*") (part "PMOS"))
    )
    (comp (ref "Q3")
      (value "2301")
      (footprint "SOT23")
      (description "P-MOSFET")
      (libsource (lib "*") (part "PMOS"))
    )
    (comp (ref "Q4")
      (value "2301")
      (footprint "SOT23")
      (description "P-MOSFET")
      (libsource (lib "*") (part "PMOS"))
    )
    (comp (ref "Q5")
      (value "2301")
      (footprint "SOT23")
      (description "P-MOSFET")
      (libsource (lib "*") (part "PMOS"))
    )
    (comp (ref "Q6")
      (value "2301")
      (footprint "SOT23")
      (description "P-MOSFET")
      (libsource (lib "*") (part "PMOS"))
    )
    (comp (ref "Q7")
      (value "2301")
      (footprint "SOT23")
      (description "P-MOSFET")
      (libsource (lib "*") (part "PMOS"))
    )
    (comp (ref "Q8")
      (value "2301")
      (footprint "SOT23")
      (description "P-MOSFET")
      (libsource (lib "*") (part "PMOS"))
    )
    (comp (ref "Q9")
      (value "2301")
      (footprint "SOT23")
      (description "P-MOSFET")
      (libsource (lib "*") (part "PMOS"))
    )
    (comp (ref "Q10")
      (value "2301")
      (footprint "SOT23")
      (description "P-MOSFET")
      (libsource (lib "*") (part "PMOS"))
    )
    (comp (ref "Q11")
      (value "2301")
      (footprint "SOT23")
      (description "P-MOSFET")
      (libsource (lib "*") (part "PMOS"))
    )
    (comp (ref "Q12")
      (value "2301")
      (footprint "SOT23")
      (description "P-MOSFET")
      (libsource (lib "*") (part "PMOS"))
    )
    (comp (ref "Q13")
      (value "2301")
      (footprint "SOT23")
      (description "P-MOSFET")
      (libsource (lib "*") (part "PMOS"))
    )
    (comp (ref "Q14")
      (value "2301")
      (footprint "SOT23")
      (description "P-MOSFET")
      (libsource (lib "*") (part "PMOS"))
    )
    (comp (ref "Q15")
      (value "2301")
      (footprint "SOT23")
      (description "P-MOSFET")
      (libsource (lib "*") (part "PMOS"))
    )
    (comp (ref "Q16")
      (value "2301")
      (footprint "SOT23")
      (description "P-MOSFET")
      (libsource (lib "*") (part "PMOS"))
    )
    (comp (ref "Q17")
      (value "2301")
      (footprint "SOT23")
      (description "P-MOSFET")
      (libsource (lib "*") (part "PMOS"))
    )
    (comp (ref "Q18")
      (value "2302")
      (footprint "SOT23")
      (description "N-MOSFET")
      (libsource (lib "*") (part "NMOS"))
    )
    (comp (ref "R1")
      (value "0")
      (footprint "0603")
      (description "Resistor")
      (fields (field (name "PUBLISHER") "Altium Limited"))
      (libsource (lib "*") (part "Res2"))
    )
    (comp (ref "R2")
      (value "0")
      (footprint "0603")
      (description "Resistor")
      (fields (field (name "PUBLISHER") "Altium Limited"))
      (libsource (lib "*") (part "Res2"))
    )
    (comp (ref "R3")
      (value "0")
      (footprint "0603")
      (description "Resistor")
      (fields (field (name "PUBLISHER") "Altium Limited"))
      (libsource (lib "*") (part "Res2"))
    )
    (comp (ref "R4")
      (value "0")
      (footprint "0603")
      (description "Resistor")
      (fields (field (name "PUBLISHER") "Altium Limited"))
      (libsource (lib "*") (part "Res2"))
    )
    (comp (ref "R5")
      (value "0")
      (footprint "0603")
      (description "Resistor")
      (fields (field (name "PUBLISHER") "Altium Limited"))
      (libsource (lib "*") (part "Res2"))
    )
    (comp (ref "R6")
      (value "0")
      (footprint "0603")
      (description "Resistor")
      (fields (field (name "PUBLISHER") "Altium Limited"))
      (libsource (lib "*") (part "Res2"))
    )
    (comp (ref "R7")
      (value "0")
      (footprint "0603")
      (description "Resistor")
      (fields (field (name "PUBLISHER") "Altium Limited"))
      (libsource (lib "") (part "Res2_2"))
    )
    (comp (ref "R8")
      (value "0")
      (footprint "0603")
      (description "Resistor")
      (fields (field (name "PUBLISHER") "Altium Limited"))
      (libsource (lib "") (part "Res2_1"))
    )
    (comp (ref "R9")
      (value "27")
      (footprint "0603")
      (description "Resistor")
      (fields (field (name "PUBLISHER") "Altium Limited"))
      (libsource (lib "*") (part "Res2"))
    )
    (comp (ref "R10")
      (value "27")
      (footprint "0603")
      (description "Resistor")
      (fields (field (name "PUBLISHER") "Altium Limited"))
      (libsource (lib "*") (part "Res2"))
    )
    (comp (ref "R11")
      (value "27")
      (footprint "0603")
      (description "Resistor")
      (fields (field (name "PUBLISHER") "Altium Limited"))
      (libsource (lib "*") (part "Res2"))
    )
    (comp (ref "R12")
      (value "27")
      (footprint "0603")
      (description "Resistor")
      (fields (field (name "PUBLISHER") "Altium Limited"))
      (libsource (lib "") (part "Res2_1"))
    )
    (comp (ref "R13")
      (value "27")
      (footprint "0603")
      (description "Resistor")
      (fields (field (name "PUBLISHER") "Altium Limited"))
      (libsource (lib "") (part "Res2_1"))
    )
    (comp (ref "R14")
      (value "27")
      (footprint "0603")
      (description "Resistor")
      (fields (field (name "PUBLISHER") "Altium Limited"))
      (libsource (lib "") (part "Res2_1"))
    )
    (comp (ref "R15")
      (value "27")
      (footprint "0603")
      (description "Resistor")
      (fields (field (name "PUBLISHER") "Altium Limited"))
      (libsource (lib "") (part "Res2_1"))
    )
    (comp (ref "R16")
      (value "27")
      (footprint "0603")
      (description "Resistor")
      (fields (field (name "PUBLISHER") "Altium Limited"))
      (libsource (lib "") (part "Res2_1"))
    )
    (comp (ref "R19")
      (value "30")
      (footprint "0603")
      (description "Resistor")
      (fields (field (name "PUBLISHER") "Altium Limited"))
      (libsource (lib "*") (part "Res2"))
    )
    (comp (ref "R20")
      (value "30")
      (footprint "0603")
      (description "Resistor")
      (fields (field (name "PUBLISHER") "Altium Limited"))
      (libsource (lib "*") (part "Res2"))
    )
    (comp (ref "R21")
      (value "30")
      (footprint "0603")
      (description "Resistor")
      (fields (field (name "PUBLISHER") "Altium Limited"))
      (libsource (lib "*") (part "Res2"))
    )
    (comp (ref "R22")
      (value "30")
      (footprint "0603")
      (description "Resistor")
      (fields (field (name "PUBLISHER") "Altium Limited"))
      (libsource (lib "*") (part "Res2"))
    )
    (comp (ref "R23")
      (value "30")
      (footprint "0603")
      (description "Resistor")
      (fields (field (name "PUBLISHER") "Altium Limited"))
      (libsource (lib "") (part "Res2_2"))
    )
    (comp (ref "R24")
      (value "30")
      (footprint "0603")
      (description "Resistor")
      (fields (field (name "PUBLISHER") "Altium Limited"))
      (libsource (lib "") (part "Res2_2"))
    )
    (comp (ref "R25")
      (value "30")
      (footprint "0603")
      (description "Resistor")
      (fields (field (name "PUBLISHER") "Altium Limited"))
      (libsource (lib "*") (part "Res2"))
    )
    (comp (ref "R26")
      (value "30")
      (footprint "0603")
      (description "Resistor")
      (fields (field (name "PUBLISHER") "Altium Limited"))
      (libsource (lib "*") (part "Res2"))
    )
    (comp (ref "R27")
      (value "4.7k")
      (footprint "0603")
      (description "Resistor")
      (fields (field (name "PUBLISHER") "Altium Limited"))
      (libsource (lib "*") (part "Res2"))
    )
    (comp (ref "R28")
      (value "4.7k")
      (footprint "0603")
      (description "Resistor")
      (fields (field (name "PUBLISHER") "Altium Limited"))
      (libsource (lib "*") (part "Res2"))
    )
    (comp (ref "R29")
      (value "4.7k")
      (footprint "0603")
      (description "Resistor")
      (fields (field (name "PUBLISHER") "Altium Limited"))
      (libsource (lib "*") (part "Res2"))
    )
    (comp (ref "R30")
      (value "4.7k")
      (footprint "0603")
      (description "Resistor")
      (fields (field (name "PUBLISHER") "Altium Limited"))
      (libsource (lib "*") (part "Res2"))
    )
    (comp (ref "R31")
      (value "4.7k")
      (footprint "0603")
      (description "Resistor")
      (fields (field (name "PUBLISHER") "Altium Limited"))
      (libsource (lib "*") (part "Res2"))
    )
    (comp (ref "R32")
      (value "4.7k")
      (footprint "0603")
      (description "Resistor")
      (fields (field (name "PUBLISHER") "Altium Limited"))
      (libsource (lib "*") (part "Res2"))
    )
    (comp (ref "R33")
      (value "4.7k")
      (footprint "0603")
      (description "Resistor")
      (fields (field (name "PUBLISHER") "Altium Limited"))
      (libsource (lib "*") (part "Res2"))
    )
    (comp (ref "R312") (value "NC.") (footprint "0603") (libsource (lib "*") (part "DZ")))
    (comp (ref "SW1")
      (value "~")
      (footprint "SMD_6.1x3.65x2.5mm-KEY")
      (libsource (lib "PCB_Project1") (part "Pro1BB.tmp_UnNamed_18"))
    )
    (comp (ref "SW2")
      (value "~")
      (footprint "黑轴4.2mm")
      (libsource (lib "PCB_Project1") (part "Pro1BB.tmp_UnNamed_18"))
    )
    (comp (ref "SW3")
      (value "~")
      (footprint "黑轴4.2mm")
      (libsource (lib "PCB_Project1") (part "Pro1BB.tmp_UnNamed_18"))
    )
    (comp (ref "SW4")
      (value "~")
      (footprint "黑轴4.2mm")
      (libsource (lib "PCB_Project1") (part "Pro1BB.tmp_UnNamed_18"))
    )
    (comp (ref "SW5")
      (value "~")
      (footprint "黑轴4.2mm")
      (libsource (lib "PCB_Project1") (part "Pro1BB.tmp_UnNamed_18"))
    )
    (comp (ref "SW6")
      (value "~")
      (footprint "黑轴4.2mm")
      (libsource (lib "PCB_Project1") (part "Pro1BB.tmp_UnNamed_18"))
    )
    (comp (ref "SW7")
      (value "~")
      (footprint "黑轴4.2mm")
      (libsource (lib "PCB_Project1") (part "Pro1BB.tmp_UnNamed_18"))
    )
    (comp (ref "SW8")
      (value "~")
      (footprint "黑轴4.2mm")
      (libsource (lib "PCB_Project1") (part "Pro1BB.tmp_UnNamed_18"))
    )
    (comp (ref "SW9")
      (value "~")
      (footprint "黑轴4.2mm")
      (libsource (lib "PCB_Project1") (part "Pro1BB.tmp_UnNamed_18"))
    )
    (comp (ref "SW10")
      (value "~")
      (footprint "黑轴4.2mm")
      (libsource (lib "PCB_Project1") (part "Pro1BB.tmp_UnNamed_18"))
    )
    (comp (ref "SW11")
      (value "~")
      (footprint "黑轴4.2mm")
      (libsource (lib "PCB_Project1") (part "Pro1BB.tmp_UnNamed_18"))
    )
    (comp (ref "SW12")
      (value "~")
      (footprint "黑轴4.2mm")
      (libsource (lib "PCB_Project1") (part "Pro1BB.tmp_UnNamed_18"))
    )
    (comp (ref "SW13")
      (value "~")
      (footprint "黑轴4.2mm")
      (libsource (lib "PCB_Project1") (part "Pro1BB.tmp_UnNamed_18"))
    )
    (comp (ref "SW14")
      (value "~")
      (footprint "黑轴4.2mm")
      (libsource (lib "PCB_Project1") (part "Pro1BB.tmp_UnNamed_18"))
    )
    (comp (ref "SW15")
      (value "~")
      (footprint "黑轴4.2mm")
      (libsource (lib "PCB_Project1") (part "Pro1BB.tmp_UnNamed_18"))
    )
    (comp (ref "SW16")
      (value "~")
      (footprint "黑轴4.2mm")
      (libsource (lib "PCB_Project1") (part "Pro1BB.tmp_UnNamed_18"))
    )
    (comp (ref "SW17")
      (value "~")
      (footprint "黑轴4.2mm")
      (libsource (lib "PCB_Project1") (part "Pro1BB.tmp_UnNamed_18"))
    )
    (comp (ref "SW18")
      (value "~")
      (footprint "黑轴4.2mm")
      (libsource (lib "PCB_Project1") (part "Pro1BB.tmp_UnNamed_18"))
    )
    (comp (ref "SW19")
      (value "~")
      (footprint "黑轴4.2mm")
      (libsource (lib "PCB_Project1") (part "Pro1BB.tmp_UnNamed_18"))
    )
    (comp (ref "SW20")
      (value "~")
      (footprint "黑轴4.2mm")
      (libsource (lib "PCB_Project1") (part "Pro1BB.tmp_UnNamed_18"))
    )
    (comp (ref "SW21")
      (value "~")
      (footprint "黑轴4.2mm")
      (libsource (lib "PCB_Project1") (part "Pro1BB.tmp_UnNamed_18"))
    )
    (comp (ref "SW22")
      (value "~")
      (footprint "黑轴4.2mm")
      (libsource (lib "PCB_Project1") (part "Pro1BB.tmp_UnNamed_18"))
    )
    (comp (ref "SW23")
      (value "~")
      (footprint "黑轴4.2mm")
      (libsource (lib "PCB_Project1") (part "Pro1BB.tmp_UnNamed_18"))
    )
    (comp (ref "SW24")
      (value "~")
      (footprint "黑轴4.2mm")
      (libsource (lib "PCB_Project1") (part "Pro1BB.tmp_UnNamed_18"))
    )
    (comp (ref "SW25")
      (value "~")
      (footprint "黑轴4.2mm")
      (libsource (lib "PCB_Project1") (part "Pro1BB.tmp_UnNamed_18"))
    )
    (comp (ref "SW26")
      (value "~")
      (footprint "黑轴4.2mm")
      (libsource (lib "PCB_Project1") (part "Pro1BB.tmp_UnNamed_18"))
    )
    (comp (ref "SW27")
      (value "~")
      (footprint "黑轴4.2mm")
      (libsource (lib "PCB_Project1") (part "Pro1BB.tmp_UnNamed_18"))
    )
    (comp (ref "SW28")
      (value "~")
      (footprint "黑轴4.2mm")
      (libsource (lib "PCB_Project1") (part "Pro1BB.tmp_UnNamed_18"))
    )
    (comp (ref "SW29")
      (value "~")
      (footprint "黑轴4.2mm")
      (libsource (lib "PCB_Project1") (part "Pro1BB.tmp_UnNamed_18"))
    )
    (comp (ref "SW30")
      (value "~")
      (footprint "黑轴4.2mm")
      (libsource (lib "PCB_Project1") (part "Pro1BB.tmp_UnNamed_18"))
    )
    (comp (ref "SW31")
      (value "~")
      (footprint "黑轴4.2mm")
      (libsource (lib "PCB_Project1") (part "Pro1BB.tmp_UnNamed_18"))
    )
    (comp (ref "SW32")
      (value "~")
      (footprint "黑轴4.2mm")
      (libsource (lib "PCB_Project1") (part "Pro1BB.tmp_UnNamed_18"))
    )
    (comp (ref "SW33")
      (value "~")
      (footprint "黑轴4.2mm")
      (libsource (lib "PCB_Project1") (part "Pro1BB.tmp_UnNamed_18"))
    )
    (comp (ref "SW34")
      (value "~")
      (footprint "黑轴4.2mm")
      (libsource (lib "PCB_Project1") (part "Pro1BB.tmp_UnNamed_18"))
    )
    (comp (ref "SW35")
      (value "~")
      (footprint "黑轴4.2mm")
      (libsource (lib "PCB_Project1") (part "Pro1BB.tmp_UnNamed_18"))
    )
    (comp (ref "SW36")
      (value "~")
      (footprint "黑轴4.2mm")
      (libsource (lib "PCB_Project1") (part "Pro1BB.tmp_UnNamed_18"))
    )
    (comp (ref "SW37")
      (value "~")
      (footprint "黑轴4.2mm")
      (libsource (lib "PCB_Project1") (part "Pro1BB.tmp_UnNamed_18"))
    )
    (comp (ref "SW38")
      (value "~")
      (footprint "黑轴4.2mm")
      (libsource (lib "PCB_Project1") (part "Pro1BB.tmp_UnNamed_18"))
    )
    (comp (ref "SW39")
      (value "~")
      (footprint "黑轴4.2mm")
      (libsource (lib "PCB_Project1") (part "Pro1BB.tmp_UnNamed_18"))
    )
    (comp (ref "SW40")
      (value "~")
      (footprint "黑轴4.2mm")
      (libsource (lib "PCB_Project1") (part "Pro1BB.tmp_UnNamed_18"))
    )
    (comp (ref "SW41")
      (value "~")
      (footprint "黑轴4.2mm")
      (libsource (lib "PCB_Project1") (part "Pro1BB.tmp_UnNamed_18"))
    )
    (comp (ref "SW42")
      (value "~")
      (footprint "黑轴4.2mm")
      (libsource (lib "PCB_Project1") (part "Pro1BB.tmp_UnNamed_18"))
    )
    (comp (ref "SW43")
      (value "~")
      (footprint "黑轴4.2mm")
      (libsource (lib "PCB_Project1") (part "Pro1BB.tmp_UnNamed_18"))
    )
    (comp (ref "SW44")
      (value "~")
      (footprint "黑轴4.2mm")
      (libsource (lib "PCB_Project1") (part "Pro1BB.tmp_UnNamed_18"))
    )
    (comp (ref "SW45")
      (value "~")
      (footprint "黑轴4.2mm")
      (libsource (lib "PCB_Project1") (part "Pro1BB.tmp_UnNamed_18"))
    )
    (comp (ref "SW46")
      (value "~")
      (footprint "黑轴4.2mm")
      (libsource (lib "PCB_Project1") (part "Pro1BB.tmp_UnNamed_18"))
    )
    (comp (ref "SW47")
      (value "~")
      (footprint "黑轴4.2mm")
      (libsource (lib "PCB_Project1") (part "Pro1BB.tmp_UnNamed_18"))
    )
    (comp (ref "SW48")
      (value "~")
      (footprint "黑轴4.2mm")
      (libsource (lib "PCB_Project1") (part "Pro1BB.tmp_UnNamed_18"))
    )
    (comp (ref "SW49")
      (value "~")
      (footprint "黑轴4.2mm")
      (libsource (lib "PCB_Project1") (part "Pro1BB.tmp_UnNamed_18"))
    )
    (comp (ref "SW50")
      (value "~")
      (footprint "黑轴4.2mm")
      (libsource (lib "PCB_Project1") (part "Pro1BB.tmp_UnNamed_18"))
    )
    (comp (ref "SW51")
      (value "~")
      (footprint "黑轴4.2mm")
      (libsource (lib "PCB_Project1") (part "Pro1BB.tmp_UnNamed_18"))
    )
    (comp (ref "SW52")
      (value "~")
      (footprint "黑轴4.2mm")
      (libsource (lib "PCB_Project1") (part "Pro1BB.tmp_UnNamed_18"))
    )
    (comp (ref "SW53")
      (value "~")
      (footprint "黑轴4.2mm")
      (libsource (lib "PCB_Project1") (part "Pro1BB.tmp_UnNamed_18"))
    )
    (comp (ref "SW54")
      (value "~")
      (footprint "黑轴4.2mm")
      (libsource (lib "PCB_Project1") (part "Pro1BB.tmp_UnNamed_18"))
    )
    (comp (ref "SW55")
      (value "~")
      (footprint "黑轴4.2mm")
      (libsource (lib "PCB_Project1") (part "Pro1BB.tmp_UnNamed_18"))
    )
    (comp (ref "SW56")
      (value "~")
      (footprint "黑轴4.2mm")
      (libsource (lib "PCB_Project1") (part "Pro1BB.tmp_UnNamed_18"))
    )
    (comp (ref "SW57")
      (value "~")
      (footprint "黑轴4.2mm")
      (libsource (lib "PCB_Project1") (part "Pro1BB.tmp_UnNamed_18"))
    )
    (comp (ref "SW58")
      (value "~")
      (footprint "黑轴4.2mm")
      (libsource (lib "PCB_Project1") (part "Pro1BB.tmp_UnNamed_18"))
    )
    (comp (ref "SW59")
      (value "~")
      (footprint "黑轴4.2mm")
      (libsource (lib "PCB_Project1") (part "Pro1BB.tmp_UnNamed_18"))
    )
    (comp (ref "SW60")
      (value "~")
      (footprint "黑轴4.2mm")
      (libsource (lib "PCB_Project1") (part "Pro1BB.tmp_UnNamed_18"))
    )
    (comp (ref "SW61")
      (value "~")
      (footprint "黑轴4.2mm")
      (libsource (lib "PCB_Project1") (part "Pro1BB.tmp_UnNamed_18"))
    )
    (comp (ref "SW62")
      (value "~")
      (footprint "黑轴4.2mm")
      (libsource (lib "PCB_Project1") (part "Pro1BB.tmp_UnNamed_18"))
    )
    (comp (ref "SW63")
      (value "~")
      (footprint "黑轴4.2mm")
      (libsource (lib "PCB_Project1") (part "Pro1BB.tmp_UnNamed_18"))
    )
    (comp (ref "SW64")
      (value "~")
      (footprint "黑轴4.2mm")
      (libsource (lib "PCB_Project1") (part "Pro1BB.tmp_UnNamed_18"))
    )
    (comp (ref "SW65")
      (value "~")
      (footprint "黑轴4.2mm")
      (libsource (lib "PCB_Project1") (part "Pro1BB.tmp_UnNamed_18"))
    )
    (comp (ref "SW66")
      (value "~")
      (footprint "黑轴4.2mm")
      (libsource (lib "PCB_Project1") (part "Pro1BB.tmp_UnNamed_18"))
    )
    (comp (ref "SW67")
      (value "~")
      (footprint "黑轴4.2mm")
      (libsource (lib "PCB_Project1") (part "Pro1BB.tmp_UnNamed_18"))
    )
    (comp (ref "SW68")
      (value "~")
      (footprint "黑轴4.2mm")
      (libsource (lib "PCB_Project1") (part "Pro1BB.tmp_UnNamed_18"))
    )
    (comp (ref "SW69")
      (value "~")
      (footprint "黑轴4.2mm")
      (libsource (lib "PCB_Project1") (part "Pro1BB.tmp_UnNamed_18"))
    )
    (comp (ref "SW70")
      (value "~")
      (footprint "黑轴4.2mm")
      (libsource (lib "PCB_Project1") (part "Pro1BB.tmp_UnNamed_18"))
    )
    (comp (ref "SW71")
      (value "~")
      (footprint "黑轴4.2mm")
      (libsource (lib "PCB_Project1") (part "Pro1BB.tmp_UnNamed_18"))
    )
    (comp (ref "SW72")
      (value "~")
      (footprint "黑轴4.2mm")
      (libsource (lib "PCB_Project1") (part "Pro1BB.tmp_UnNamed_18"))
    )
    (comp (ref "SW73")
      (value "~")
      (footprint "黑轴4.2mm")
      (libsource (lib "PCB_Project1") (part "Pro1BB.tmp_UnNamed_18"))
    )
    (comp (ref "SW74")
      (value "~")
      (footprint "黑轴4.2mm")
      (libsource (lib "PCB_Project1") (part "Pro1BB.tmp_UnNamed_18"))
    )
    (comp (ref "SW75")
      (value "~")
      (footprint "黑轴4.2mm")
      (libsource (lib "PCB_Project1") (part "Pro1BB.tmp_UnNamed_18"))
    )
    (comp (ref "SW76")
      (value "~")
      (footprint "黑轴4.2mm")
      (libsource (lib "PCB_Project1") (part "Pro1BB.tmp_UnNamed_18"))
    )
    (comp (ref "SW77")
      (value "~")
      (footprint "黑轴4.2mm")
      (libsource (lib "PCB_Project1") (part "Pro1BB.tmp_UnNamed_18"))
    )
    (comp (ref "SW78")
      (value "~")
      (footprint "黑轴4.2mm")
      (libsource (lib "PCB_Project1") (part "Pro1BB.tmp_UnNamed_18"))
    )
    (comp (ref "SW79")
      (value "~")
      (footprint "黑轴4.2mm")
      (libsource (lib "PCB_Project1") (part "Pro1BB.tmp_UnNamed_18"))
    )
    (comp (ref "SW80")
      (value "~")
      (footprint "黑轴4.2mm")
      (libsource (lib "PCB_Project1") (part "Pro1BB.tmp_UnNamed_18"))
    )
    (comp (ref "SW81")
      (value "~")
      (footprint "黑轴4.2mm")
      (libsource (lib "PCB_Project1") (part "Pro1BB.tmp_UnNamed_18"))
    )
    (comp (ref "SW82")
      (value "~")
      (footprint "黑轴4.2mm")
      (libsource (lib "PCB_Project1") (part "Pro1BB.tmp_UnNamed_18"))
    )
    (comp (ref "SW83")
      (value "~")
      (footprint "黑轴4.2mm")
      (libsource (lib "PCB_Project1") (part "Pro1BB.tmp_UnNamed_18"))
    )
    (comp (ref "SW84")
      (value "~")
      (footprint "黑轴4.2mm")
      (libsource (lib "PCB_Project1") (part "Pro1BB.tmp_UnNamed_18"))
    )
    (comp (ref "SW85")
      (value "~")
      (footprint "黑轴4.2mm")
      (libsource (lib "PCB_Project1") (part "Pro1BB.tmp_UnNamed_18"))
    )
    (comp (ref "SW86")
      (value "~")
      (footprint "黑轴4.2mm")
      (libsource (lib "PCB_Project1") (part "Pro1BB.tmp_UnNamed_18"))
    )
    (comp (ref "SW87")
      (value "~")
      (footprint "黑轴4.2mm")
      (libsource (lib "PCB_Project1") (part "Pro1BB.tmp_UnNamed_18"))
    )
    (comp (ref "SW88")
      (value "~")
      (footprint "黑轴4.2mm")
      (libsource (lib "PCB_Project1") (part "Pro1BB.tmp_UnNamed_18"))
    )
    (comp (ref "SW89")
      (value "~")
      (footprint "黑轴4.2mm")
      (libsource (lib "PCB_Project1") (part "Pro1BB.tmp_UnNamed_18"))
    )
    (comp (ref "SW90")
      (value "~")
      (footprint "黑轴4.2mm")
      (libsource (lib "PCB_Project1") (part "Pro1BB.tmp_UnNamed_18"))
    )
    (comp (ref "SW91")
      (value "~")
      (footprint "黑轴4.2mm")
      (libsource (lib "PCB_Project1") (part "Pro1BB.tmp_UnNamed_18"))
    )
    (comp (ref "SW92")
      (value "~")
      (footprint "黑轴4.2mm")
      (libsource (lib "PCB_Project1") (part "Pro1BB.tmp_UnNamed_18"))
    )
    (comp (ref "SW93")
      (value "~")
      (footprint "黑轴4.2mm")
      (libsource (lib "PCB_Project1") (part "Pro1BB.tmp_UnNamed_18"))
    )
    (comp (ref "SW94")
      (value "~")
      (footprint "黑轴4.2mm")
      (libsource (lib "PCB_Project1") (part "Pro1BB.tmp_UnNamed_18"))
    )
    (comp (ref "SW95")
      (value "~")
      (footprint "黑轴4.2mm")
      (libsource (lib "PCB_Project1") (part "Pro1BB.tmp_UnNamed_18"))
    )
    (comp (ref "SW96")
      (value "~")
      (footprint "黑轴4.2mm")
      (libsource (lib "PCB_Project1") (part "Pro1BB.tmp_UnNamed_18"))
    )
    (comp (ref "SW97")
      (value "~")
      (footprint "黑轴4.2mm")
      (libsource (lib "PCB_Project1") (part "Pro1BB.tmp_UnNamed_18"))
    )
    (comp (ref "SW98")
      (value "~")
      (footprint "黑轴4.2mm")
      (libsource (lib "PCB_Project1") (part "Pro1BB.tmp_UnNamed_18"))
    )
    (comp (ref "SW99")
      (value "~")
      (footprint "黑轴4.2mm")
      (libsource (lib "PCB_Project1") (part "Pro1BB.tmp_UnNamed_18"))
    )
    (comp (ref "SW100")
      (value "~")
      (footprint "黑轴4.2mm")
      (libsource (lib "PCB_Project1") (part "Pro1BB.tmp_UnNamed_18"))
    )
    (comp (ref "SW101")
      (value "~")
      (footprint "黑轴4.2mm")
      (libsource (lib "PCB_Project1") (part "Pro1BB.tmp_UnNamed_18"))
    )
    (comp (ref "SW102")
      (value "~")
      (footprint "黑轴4.2mm")
      (libsource (lib "PCB_Project1") (part "Pro1BB.tmp_UnNamed_18"))
    )
    (comp (ref "SW103")
      (value "~")
      (footprint "黑轴4.2mm")
      (libsource (lib "PCB_Project1") (part "Pro1BB.tmp_UnNamed_18"))
    )
    (comp (ref "SW104")
      (value "~")
      (footprint "黑轴4.2mm")
      (libsource (lib "PCB_Project1") (part "Pro1BB.tmp_UnNamed_18"))
    )
    (comp (ref "SW105")
      (value "~")
      (footprint "黑轴4.2mm")
      (libsource (lib "PCB_Project1") (part "Pro1BB.tmp_UnNamed_18"))
    )
  )
  (nets
    (net (code "1") (name "/BLUE0") (class "Default")
      (node (ref "D1") (pin "4") (pinfunction "B_4") (pintype "passive"))
      (node (ref "D178") (pin "4") (pinfunction "B_4") (pintype "passive"))
      (node (ref "D179") (pin "4") (pinfunction "B_4") (pintype "passive"))
      (node (ref "D180") (pin "4") (pinfunction "B_4") (pintype "passive"))
      (node (ref "D181") (pin "4") (pinfunction "B_4") (pintype "passive"))
      (node (ref "D182") (pin "4") (pinfunction "B_4") (pintype "passive"))
      (node (ref "D189") (pin "4") (pinfunction "B_4") (pintype "passive"))
      (node (ref "D2") (pin "4") (pinfunction "B_4") (pintype "passive"))
      (node (ref "D3") (pin "4") (pinfunction "B_4") (pintype "passive"))
      (node (ref "D4") (pin "4") (pinfunction "B_4") (pintype "passive"))
      (node (ref "D80") (pin "4") (pinfunction "B_4") (pintype "passive"))
      (node (ref "D81") (pin "4") (pinfunction "B_4") (pintype "passive"))
      (node (ref "D82") (pin "4") (pinfunction "B_4") (pintype "passive"))
      (node (ref "D83") (pin "4") (pinfunction "B_4") (pintype "passive"))
      (node (ref "D84") (pin "4") (pinfunction "B_4") (pintype "passive"))
      (node (ref "D9") (pin "4") (pinfunction "B_4") (pintype "passive"))
      (node (ref "R1") (pin "1") (pinfunction "1_1") (pintype "passive"))
    )
    (net (code "2") (name "/BLUE1") (class "Default")
      (node (ref "D10") (pin "4") (pinfunction "B_4") (pintype "passive"))
      (node (ref "D100") (pin "4") (pinfunction "B_4") (pintype "passive"))
      (node (ref "D101") (pin "4") (pinfunction "B_4") (pintype "passive"))
      (node (ref "D102") (pin "4") (pinfunction "B_4") (pintype "passive"))
      (node (ref "D103") (pin "4") (pinfunction "B_4") (pintype "passive"))
      (node (ref "D104") (pin "4") (pinfunction "B_4") (pintype "passive"))
      (node (ref "D11") (pin "4") (pinfunction "B_4") (pintype "passive"))
      (node (ref "D12") (pin "4") (pinfunction "B_4") (pintype "passive"))
      (node (ref "D13") (pin "4") (pinfunction "B_4") (pintype "passive"))
      (node (ref "D14") (pin "4") (pinfunction "B_4") (pintype "passive"))
      (node (ref "D183") (pin "4") (pinfunction "B_4") (pintype "passive"))
      (node (ref "D184") (pin "4") (pinfunction "B_4") (pintype "passive"))
      (node (ref "D185") (pin "4") (pinfunction "B_4") (pintype "passive"))
      (node (ref "D186") (pin "4") (pinfunction "B_4") (pintype "passive"))
      (node (ref "D187") (pin "4") (pinfunction "B_4") (pintype "passive"))
      (node (ref "D198") (pin "4") (pinfunction "B_4") (pintype "passive"))
      (node (ref "R2") (pin "1") (pinfunction "1_1") (pintype "passive"))
    )
    (net (code "3") (name "/BLUE2") (class "Default")
      (node (ref "D105") (pin "4") (pinfunction "B_4") (pintype "passive"))
      (node (ref "D106") (pin "4") (pinfunction "B_4") (pintype "passive"))
      (node (ref "D107") (pin "4") (pinfunction "B_4") (pintype "passive"))
      (node (ref "D108") (pin "4") (pinfunction "B_4") (pintype "passive"))
      (node (ref "D109") (pin "4") (pinfunction "B_4") (pintype "passive"))
      (node (ref "D15") (pin "4") (pinfunction "B_4") (pintype "passive"))
      (node (ref "D16") (pin "4") (pinfunction "B_4") (pintype "passive"))
      (node (ref "D17") (pin "4") (pinfunction "B_4") (pintype "passive"))
      (node (ref "D18") (pin "4") (pinfunction "B_4") (pintype "passive"))
      (node (ref "D19") (pin "4") (pinfunction "B_4") (pintype "passive"))
      (node (ref "D193") (pin "4") (pinfunction "B_4") (pintype "passive"))
      (node (ref "D194") (pin "4") (pinfunction "B_4") (pintype "passive"))
      (node (ref "D195") (pin "4") (pinfunction "B_4") (pintype "passive"))
      (node (ref "D196") (pin "4") (pinfunction "B_4") (pintype "passive"))
      (node (ref "D197") (pin "4") (pinfunction "B_4") (pintype "passive"))
      (node (ref "D204") (pin "4") (pinfunction "B_4") (pintype "passive"))
      (node (ref "R3") (pin "1") (pinfunction "1_1") (pintype "passive"))
    )
    (net (code "4") (name "/BLUE3") (class "Default")
      (node (ref "D126") (pin "4") (pinfunction "B_4") (pintype "passive"))
      (node (ref "D127") (pin "4") (pinfunction "B_4") (pintype "passive"))
      (node (ref "D128") (pin "4") (pinfunction "B_4") (pintype "passive"))
      (node (ref "D129") (pin "4") (pinfunction "B_4") (pintype "passive"))
      (node (ref "D130") (pin "4") (pinfunction "B_4") (pintype "passive"))
      (node (ref "D199") (pin "4") (pinfunction "B_4") (pintype "passive"))
      (node (ref "D200") (pin "4") (pinfunction "B_4") (pintype "passive"))
      (node (ref "D201") (pin "4") (pinfunction "B_4") (pintype "passive"))
      (node (ref "D203") (pin "4") (pinfunction "B_4") (pintype "passive"))
      (node (ref "D210") (pin "4") (pinfunction "B_4") (pintype "passive"))
      (node (ref "D34") (pin "4") (pinfunction "B_4") (pintype "passive"))
      (node (ref "D35") (pin "4") (pinfunction "B_4") (pintype "passive"))
      (node (ref "D36") (pin "4") (pinfunction "B_4") (pintype "passive"))
      (node (ref "D37") (pin "4") (pinfunction "B_4") (pintype "passive"))
      (node (ref "D38") (pin "4") (pinfunction "B_4") (pintype "passive"))
      (node (ref "R4") (pin "1") (pinfunction "1_1") (pintype "passive"))
    )
    (net (code "5") (name "/BLUE4") (class "Default")
      (node (ref "D131") (pin "4") (pinfunction "B_4") (pintype "passive"))
      (node (ref "D132") (pin "4") (pinfunction "B_4") (pintype "passive"))
      (node (ref "D133") (pin "4") (pinfunction "B_4") (pintype "passive"))
      (node (ref "D134") (pin "4") (pinfunction "B_4") (pintype "passive"))
      (node (ref "D135") (pin "4") (pinfunction "B_4") (pintype "passive"))
      (node (ref "D205") (pin "4") (pinfunction "B_4") (pintype "passive"))
      (node (ref "D206") (pin "4") (pinfunction "B_4") (pintype "passive"))
      (node (ref "D207") (pin "4") (pinfunction "B_4") (pintype "passive"))
      (node (ref "D209") (pin "4") (pinfunction "B_4") (pintype "passive"))
      (node (ref "D39") (pin "4") (pinfunction "B_4") (pintype "passive"))
      (node (ref "D40") (pin "4") (pinfunction "B_4") (pintype "passive"))
      (node (ref "D41") (pin "4") (pinfunction "B_4") (pintype "passive"))
      (node (ref "D42") (pin "4") (pinfunction "B_4") (pintype "passive"))
      (node (ref "D43") (pin "4") (pinfunction "B_4") (pintype "passive"))
      (node (ref "R5") (pin "1") (pinfunction "1_1") (pintype "passive"))
    )
    (net (code "6") (name "/BLUE5") (class "Default")
      (node (ref "D152") (pin "4") (pinfunction "B_4") (pintype "passive"))
      (node (ref "D153") (pin "4") (pinfunction "B_4") (pintype "passive"))
      (node (ref "D154") (pin "4") (pinfunction "B_4") (pintype "passive"))
      (node (ref "D212") (pin "4") (pinfunction "B_4") (pintype "passive"))
      (node (ref "D213") (pin "4") (pinfunction "B_4") (pintype "passive"))
      (node (ref "D214") (pin "4") (pinfunction "B_4") (pintype "passive"))
      (node (ref "D215") (pin "4") (pinfunction "B_4") (pintype "passive"))
      (node (ref "D222") (pin "4") (pinfunction "B_4") (pintype "passive"))
      (node (ref "D57") (pin "4") (pinfunction "B_4") (pintype "passive"))
      (node (ref "D58") (pin "4") (pinfunction "B_4") (pintype "passive"))
      (node (ref "D59") (pin "4") (pinfunction "B_4") (pintype "passive"))
      (node (ref "D60") (pin "4") (pinfunction "B_4") (pintype "passive"))
      (node (ref "D61") (pin "4") (pinfunction "B_4") (pintype "passive"))
      (node (ref "R6") (pin "1") (pinfunction "1_1") (pintype "passive"))
      (node (ref "SW1") (pin "1") (pintype "passive"))
    )
    (net (code "7") (name "/BLUE6") (class "Default")
      (node (ref "D157") (pin "4") (pinfunction "B_4") (pintype "passive"))
      (node (ref "D158") (pin "4") (pinfunction "B_4") (pintype "passive"))
      (node (ref "D159") (pin "4") (pinfunction "B_4") (pintype "passive"))
      (node (ref "D160") (pin "4") (pinfunction "B_4") (pintype "passive"))
      (node (ref "D161") (pin "4") (pinfunction "B_4") (pintype "passive"))
      (node (ref "D217") (pin "4") (pinfunction "B_4") (pintype "passive"))
      (node (ref "D218") (pin "4") (pinfunction "B_4") (pintype "passive"))
      (node (ref "D219") (pin "4") (pinfunction "B_4") (pintype "passive"))
      (node (ref "D220") (pin "4") (pinfunction "B_4") (pintype "passive"))
      (node (ref "D62") (pin "4") (pinfunction "B_4") (pintype "passive"))
      (node (ref "D63") (pin "4") (pinfunction "B_4") (pintype "passive"))
      (node (ref "D64") (pin "4") (pinfunction "B_4") (pintype "passive"))
      (node (ref "D65") (pin "4") (pinfunction "B_4") (pintype "passive"))
      (node (ref "D66") (pin "4") (pinfunction "B_4") (pintype "passive"))
      (node (ref "R7") (pin "2") (pinfunction "2_2") (pintype "passive"))
    )
    (net (code "8") (name "/BLUE7") (class "Default")
      (node (ref "R8") (pin "1") (pinfunction "1_1") (pintype "passive"))
    )
    (net (code "9") (name "/COM14") (class "Default")
      (node (ref "*") (pin "18") (pinfunction "P7.0/XI_18") (pintype "bidirectional"))
    )
    (net (code "10") (name "/COM15") (class "Default")
      (node (ref "*") (pin "19") (pinfunction "P7.1/XO/RST#/ALE__19") (pintype "bidirectional"))
    )
    (net (code "11") (name "/COM16") (class "Default")
      (node (ref "*") (pin "39") (pinfunction "P0.0/SCL0/AIN8_39") (pintype "bidirectional"))
      (node (ref "D110") (pin "2") (pinfunction "K_2") (pintype "passive"))
      (node (ref "D136") (pin "2") (pinfunction "K_2") (pintype "passive"))
      (node (ref "D162") (pin "2") (pinfunction "K_2") (pintype "passive"))
      (node (ref "D20") (pin "2") (pinfunction "K_2") (pintype "passive"))
      (node (ref "D44") (pin "2") (pinfunction "K_2") (pintype "passive"))
      (node (ref "D67") (pin "2") (pinfunction "K_2") (pintype "passive"))
      (node (ref "D85") (pin "2") (pinfunction "K_2") (pintype "passive"))
      (node (ref "Q2") (pin "1") (pinfunction "G_1") (pintype "input"))
    )
    (net (code "12") (name "/COM17") (class "Default")
      (node (ref "*") (pin "38") (pinfunction "P0.1/SDA0/AIN9_38") (pintype "bidirectional"))
      (node (ref "D111") (pin "2") (pinfunction "K_2") (pintype "passive"))
      (node (ref "D137") (pin "2") (pinfunction "K_2") (pintype "passive"))
      (node (ref "D163") (pin "2") (pinfunction "K_2") (pintype "passive"))
      (node (ref "D21") (pin "2") (pinfunction "K_2") (pintype "passive"))
      (node (ref "D45") (pin "2") (pinfunction "K_2") (pintype "passive"))
      (node (ref "D68") (pin "2") (pinfunction "K_2") (pintype "passive"))
      (node (ref "D86") (pin "2") (pinfunction "K_2") (pintype "passive"))
      (node (ref "Q3") (pin "1") (pinfunction "G_1") (pintype "input"))
    )
    (net (code "13") (name "/COM18") (class "Default")
      (node (ref "*") (pin "37") (pinfunction "P0.2/RXD_/AIN10_37") (pintype "bidirectional"))
      (node (ref "D112") (pin "2") (pinfunction "K_2") (pintype "passive"))
      (node (ref "D138") (pin "2") (pinfunction "K_2") (pintype "passive"))
      (node (ref "D164") (pin "2") (pinfunction "K_2") (pintype "passive"))
      (node (ref "D22") (pin "2") (pinfunction "K_2") (pintype "passive"))
      (node (ref "D46") (pin "2") (pinfunction "K_2") (pintype "passive"))
      (node (ref "D69") (pin "2") (pinfunction "K_2") (pintype "passive"))
      (node (ref "D87") (pin "2") (pinfunction "K_2") (pintype "passive"))
      (node (ref "Q4") (pin "1") (pinfunction "G_1") (pintype "input"))
    )
    (net (code "14") (name "/COM19") (class "Default")
      (node (ref "*") (pin "36") (pinfunction "P0.3/TXD_/AIN11_36") (pintype "bidirectional"))
      (node (ref "D113") (pin "2") (pinfunction "K_2") (pintype "passive"))
      (node (ref "D139") (pin "2") (pinfunction "K_2") (pintype "passive"))
      (node (ref "D165") (pin "2") (pinfunction "K_2") (pintype "passive"))
      (node (ref "D23") (pin "2") (pinfunction "K_2") (pintype "passive"))
      (node (ref "D47") (pin "2") (pinfunction "K_2") (pintype "passive"))
      (node (ref "D70") (pin "2") (pinfunction "K_2") (pintype "passive"))
      (node (ref "D88") (pin "2") (pinfunction "K_2") (pintype "passive"))
      (node (ref "Q5") (pin "1") (pinfunction "G_1") (pintype "input"))
    )
    (net (code "15") (name "/COM20") (class "Default")
      (node (ref "*") (pin "35") (pinfunction "P0.4/AIN12_35") (pintype "bidirectional"))
      (node (ref "D114") (pin "2") (pinfunction "K_2") (pintype "passive"))
      (node (ref "D140") (pin "2") (pinfunction "K_2") (pintype "passive"))
      (node (ref "D166") (pin "2") (pinfunction "K_2") (pintype "passive"))
      (node (ref "D24") (pin "2") (pinfunction "K_2") (pintype "passive"))
      (node (ref "D48") (pin "2") (pinfunction "K_2") (pintype "passive"))
      (node (ref "D71") (pin "2") (pinfunction "K_2") (pintype "passive"))
      (node (ref "D89") (pin "2") (pinfunction "K_2") (pintype "passive"))
      (node (ref "Q6") (pin "1") (pinfunction "G_1") (pintype "input"))
    )
    (net (code "16") (name "/COM21") (class "Default")
      (node (ref "*") (pin "34") (pinfunction "P0.5/AIN13_34") (pintype "bidirectional"))
      (node (ref "D115") (pin "2") (pinfunction "K_2") (pintype "passive"))
      (node (ref "D141") (pin "2") (pinfunction "K_2") (pintype "passive"))
      (node (ref "D167") (pin "2") (pinfunction "K_2") (pintype "passive"))
      (node (ref "D25") (pin "2") (pinfunction "K_2") (pintype "passive"))
      (node (ref "D49") (pin "2") (pinfunction "K_2") (pintype "passive"))
      (node (ref "D72") (pin "2") (pinfunction "K_2") (pintype "passive"))
      (node (ref "D90") (pin "2") (pinfunction "K_2") (pintype "passive"))
      (node (ref "Q7") (pin "1") (pinfunction "G_1") (pintype "input"))
    )
    (net (code "17") (name "/COM22") (class "Default")
      (node (ref "*") (pin "33") (pinfunction "P0.6_33") (pintype "bidirectional"))
      (node (ref "D116") (pin "2") (pinfunction "K_2") (pintype "passive"))
      (node (ref "D142") (pin "2") (pinfunction "K_2") (pintype "passive"))
      (node (ref "D168") (pin "2") (pinfunction "K_2") (pintype "passive"))
      (node (ref "D26") (pin "2") (pinfunction "K_2") (pintype "passive"))
      (node (ref "D50") (pin "2") (pinfunction "K_2") (pintype "passive"))
      (node (ref "D73") (pin "2") (pinfunction "K_2") (pintype "passive"))
      (node (ref "D91") (pin "2") (pinfunction "K_2") (pintype "passive"))
      (node (ref "Q8") (pin "1") (pinfunction "G_1") (pintype "input"))
    )
    (net (code "18") (name "/COM23") (class "Default")
      (node (ref "*") (pin "32") (pinfunction "P0.7_32") (pintype "bidirectional"))
      (node (ref "D117") (pin "2") (pinfunction "K_2") (pintype "passive"))
      (node (ref "D143") (pin "2") (pinfunction "K_2") (pintype "passive"))
      (node (ref "D169") (pin "2") (pinfunction "K_2") (pintype "passive"))
      (node (ref "D27") (pin "2") (pinfunction "K_2") (pintype "passive"))
      (node (ref "D51") (pin "2") (pinfunction "K_2") (pintype "passive"))
      (node (ref "D74") (pin "2") (pinfunction "K_2") (pintype "passive"))
      (node (ref "D92") (pin "2") (pinfunction "K_2") (pintype "passive"))
      (node (ref "Q9") (pin "1") (pinfunction "G_1") (pintype "input"))
    )
    (net (code "19") (name "/COM24") (class "Default")
      (node (ref "*") (pin "4") (pinfunction "P3.0/RXD_4") (pintype "bidirectional"))
      (node (ref "D118") (pin "2") (pinfunction "K_2") (pintype "passive"))
      (node (ref "D144") (pin "2") (pinfunction "K_2") (pintype "passive"))
      (node (ref "D170") (pin "2") (pinfunction "K_2") (pintype "passive"))
      (node (ref "D28") (pin "2") (pinfunction "K_2") (pintype "passive"))
      (node (ref "D75") (pin "2") (pinfunction "K_2") (pintype "passive"))
      (node (ref "D93") (pin "2") (pinfunction "K_2") (pintype "passive"))
      (node (ref "Q10") (pin "1") (pinfunction "G_1") (pintype "input"))
    )
    (net (code "20") (name "/COM25") (class "Default")
      (node (ref "*") (pin "7") (pinfunction "P3.1/TXD_7") (pintype "bidirectional"))
      (node (ref "D119") (pin "2") (pinfunction "K_2") (pintype "passive"))
      (node (ref "D145") (pin "2") (pinfunction "K_2") (pintype "passive"))
      (node (ref "D171") (pin "2") (pinfunction "K_2") (pintype "passive"))
      (node (ref "D29") (pin "2") (pinfunction "K_2") (pintype "passive"))
      (node (ref "D76") (pin "2") (pinfunction "K_2") (pintype "passive"))
      (node (ref "D94") (pin "2") (pinfunction "K_2") (pintype "passive"))
      (node (ref "Q11") (pin "1") (pinfunction "G_1") (pintype "input"))
    )
    (net (code "21") (name "/COM26") (class "Default")
      (node (ref "*") (pin "8") (pinfunction "P3.2/INT0_8") (pintype "bidirectional"))
      (node (ref "D120") (pin "2") (pinfunction "K_2") (pintype "passive"))
      (node (ref "D146") (pin "2") (pinfunction "K_2") (pintype "passive"))
      (node (ref "D172") (pin "2") (pinfunction "K_2") (pintype "passive"))
      (node (ref "D30") (pin "2") (pinfunction "K_2") (pintype "passive"))
      (node (ref "D77") (pin "2") (pinfunction "K_2") (pintype "passive"))
      (node (ref "D95") (pin "2") (pinfunction "K_2") (pintype "passive"))
      (node (ref "Q12") (pin "1") (pinfunction "G_1") (pintype "input"))
    )
    (net (code "22") (name "/COM27") (class "Default")
      (node (ref "*") (pin "9") (pinfunction "P3.3/INT1_9") (pintype "bidirectional"))
      (node (ref "D121") (pin "2") (pinfunction "K_2") (pintype "passive"))
      (node (ref "D147") (pin "2") (pinfunction "K_2") (pintype "passive"))
      (node (ref "D173") (pin "2") (pinfunction "K_2") (pintype "passive"))
      (node (ref "D31") (pin "2") (pinfunction "K_2") (pintype "passive"))
      (node (ref "D52") (pin "2") (pinfunction "K_2") (pintype "passive"))
      (node (ref "D78") (pin "2") (pinfunction "K_2") (pintype "passive"))
      (node (ref "D96") (pin "2") (pinfunction "K_2") (pintype "passive"))
      (node (ref "Q13") (pin "1") (pinfunction "G_1") (pintype "input"))
    )
    (net (code "23") (name "/COM28") (class "Default")
      (node (ref "*") (pin "10") (pinfunction "P3.4/T0_10") (pintype "bidirectional"))
      (node (ref "D122") (pin "2") (pinfunction "K_2") (pintype "passive"))
      (node (ref "D148") (pin "2") (pinfunction "K_2") (pintype "passive"))
      (node (ref "D174") (pin "2") (pinfunction "K_2") (pintype "passive"))
      (node (ref "D32") (pin "2") (pinfunction "K_2") (pintype "passive"))
      (node (ref "D53") (pin "2") (pinfunction "K_2") (pintype "passive"))
      (node (ref "D79") (pin "2") (pinfunction "K_2") (pintype "passive"))
      (node (ref "D97") (pin "2") (pinfunction "K_2") (pintype "passive"))
      (node (ref "Q14") (pin "1") (pinfunction "G_1") (pintype "input"))
    )
    (net (code "24") (name "/COM29") (class "Default")
      (node (ref "*") (pin "11") (pinfunction "P3.5/T1_11") (pintype "bidirectional"))
      (node (ref "D123") (pin "2") (pinfunction "K_2") (pintype "passive"))
      (node (ref "D149") (pin "2") (pinfunction "K_2") (pintype "passive"))
      (node (ref "D175") (pin "2") (pinfunction "K_2") (pintype "passive"))
      (node (ref "D33") (pin "2") (pinfunction "K_2") (pintype "passive"))
      (node (ref "D54") (pin "2") (pinfunction "K_2") (pintype "passive"))
      (node (ref "Q15") (pin "1") (pinfunction "G_1") (pintype "input"))
    )
    (net (code "25") (name "/COM30") (class "Default")
      (node (ref "*") (pin "12") (pinfunction "P3.6_12") (pintype "bidirectional"))
      (node (ref "D124") (pin "2") (pinfunction "K_2") (pintype "passive"))
      (node (ref "D150") (pin "2") (pinfunction "K_2") (pintype "passive"))
      (node (ref "D176") (pin "2") (pinfunction "K_2") (pintype "passive"))
      (node (ref "D5") (pin "2") (pinfunction "K_2") (pintype "passive"))
      (node (ref "D55") (pin "2") (pinfunction "K_2") (pintype "passive"))
      (node (ref "D98") (pin "2") (pinfunction "K_2") (pintype "passive"))
      (node (ref "Q16") (pin "1") (pinfunction "G_1") (pintype "input"))
    )
    (net (code "26") (name "/COM31") (class "Default")
      (node (ref "*") (pin "13") (pinfunction "P3.7_13") (pintype "bidirectional"))
      (node (ref "D125") (pin "2") (pinfunction "K_2") (pintype "passive"))
      (node (ref "D151") (pin "2") (pinfunction "K_2") (pintype "passive"))
      (node (ref "D177") (pin "2") (pinfunction "K_2") (pintype "passive"))
      (node (ref "D56") (pin "2") (pinfunction "K_2") (pintype "passive"))
      (node (ref "D99") (pin "2") (pinfunction "K_2") (pintype "passive"))
      (node (ref "Q17") (pin "1") (pinfunction "G_1") (pintype "input"))
    )
    (net (code "27") (name "/DCO") (class "Default")
      (node (ref "Q18") (pin "1") (pinfunction "G_1") (pintype "input"))
    )
    (net (code "28") (name "/GREEN0") (class "Default")
      (node (ref "D1") (pin "3") (pinfunction "G_3") (pintype "passive"))
      (node (ref "D178") (pin "3") (pinfunction "G_3") (pintype "passive"))
      (node (ref "D179") (pin "3") (pinfunction "G_3") (pintype "passive"))
      (node (ref "D180") (pin "3") (pinfunction "G_3") (pintype "passive"))
      (node (ref "D181") (pin "3") (pinfunction "G_3") (pintype "passive"))
      (node (ref "D182") (pin "3") (pinfunction "G_3") (pintype "passive"))
      (node (ref "D189") (pin "3") (pinfunction "G_3") (pintype "passive"))
      (node (ref "D2") (pin "3") (pinfunction "G_3") (pintype "passive"))
      (node (ref "D3") (pin "3") (pinfunction "G_3") (pintype "passive"))
      (node (ref "D4") (pin "3") (pinfunction "G_3") (pintype "passive"))
      (node (ref "D80") (pin "3") (pinfunction "G_3") (pintype "passive"))
      (node (ref "D81") (pin "3") (pinfunction "G_3") (pintype "passive"))
      (node (ref "D82") (pin "3") (pinfunction "G_3") (pintype "passive"))
      (node (ref "D83") (pin "3") (pinfunction "G_3") (pintype "passive"))
      (node (ref "D84") (pin "3") (pinfunction "G_3") (pintype "passive"))
      (node (ref "D9") (pin "3") (pinfunction "G_3") (pintype "passive"))
      (node (ref "R9") (pin "2") (pinfunction "2_2") (pintype "passive"))
    )
    (net (code "29") (name "/GREEN1") (class "Default")
      (node (ref "D10") (pin "3") (pinfunction "G_3") (pintype "passive"))
      (node (ref "D100") (pin "3") (pinfunction "G_3") (pintype "passive"))
      (node (ref "D101") (pin "3") (pinfunction "G_3") (pintype "passive"))
      (node (ref "D102") (pin "3") (pinfunction "G_3") (pintype "passive"))
      (node (ref "D103") (pin "3") (pinfunction "G_3") (pintype "passive"))
      (node (ref "D104") (pin "3") (pinfunction "G_3") (pintype "passive"))
      (node (ref "D11") (pin "3") (pinfunction "G_3") (pintype "passive"))
      (node (ref "D12") (pin "3") (pinfunction "G_3") (pintype "passive"))
      (node (ref "D13") (pin "3") (pinfunction "G_3") (pintype "passive"))
      (node (ref "D14") (pin "3") (pinfunction "G_3") (pintype "passive"))
      (node (ref "D183") (pin "3") (pinfunction "G_3") (pintype "passive"))
      (node (ref "D184") (pin "3") (pinfunction "G_3") (pintype "passive"))
      (node (ref "D185") (pin "3") (pinfunction "G_3") (pintype "passive"))
      (node (ref "D186") (pin "3") (pinfunction "G_3") (pintype "passive"))
      (node (ref "D187") (pin "3") (pinfunction "G_3") (pintype "passive"))
      (node (ref "D198") (pin "3") (pinfunction "G_3") (pintype "passive"))
      (node (ref "R10") (pin "2") (pinfunction "2_2") (pintype "passive"))
    )
    (net (code "30") (name "/GREEN2") (class "Default")
      (node (ref "D105") (pin "3") (pinfunction "G_3") (pintype "passive"))
      (node (ref "D106") (pin "3") (pinfunction "G_3") (pintype "passive"))
      (node (ref "D107") (pin "3") (pinfunction "G_3") (pintype "passive"))
      (node (ref "D108") (pin "3") (pinfunction "G_3") (pintype "passive"))
      (node (ref "D109") (pin "3") (pinfunction "G_3") (pintype "passive"))
      (node (ref "D15") (pin "3") (pinfunction "G_3") (pintype "passive"))
      (node (ref "D16") (pin "3") (pinfunction "G_3") (pintype "passive"))
      (node (ref "D17") (pin "3") (pinfunction "G_3") (pintype "passive"))
      (node (ref "D18") (pin "3") (pinfunction "G_3") (pintype "passive"))
      (node (ref "D19") (pin "3") (pinfunction "G_3") (pintype "passive"))
      (node (ref "D193") (pin "3") (pinfunction "G_3") (pintype "passive"))
      (node (ref "D194") (pin "3") (pinfunction "G_3") (pintype "passive"))
      (node (ref "D195") (pin "3") (pinfunction "G_3") (pintype "passive"))
      (node (ref "D196") (pin "3") (pinfunction "G_3") (pintype "passive"))
      (node (ref "D197") (pin "3") (pinfunction "G_3") (pintype "passive"))
      (node (ref "D204") (pin "3") (pinfunction "G_3") (pintype "passive"))
      (node (ref "R11") (pin "2") (pinfunction "2_2") (pintype "passive"))
    )
    (net (code "31") (name "/GREEN3") (class "Default")
      (node (ref "D126") (pin "3") (pinfunction "G_3") (pintype "passive"))
      (node (ref "D127") (pin "3") (pinfunction "G_3") (pintype "passive"))
      (node (ref "D128") (pin "3") (pinfunction "G_3") (pintype "passive"))
      (node (ref "D129") (pin "3") (pinfunction "G_3") (pintype "passive"))
      (node (ref "D130") (pin "3") (pinfunction "G_3") (pintype "passive"))
      (node (ref "D199") (pin "3") (pinfunction "G_3") (pintype "passive"))
      (node (ref "D200") (pin "3") (pinfunction "G_3") (pintype "passive"))
      (node (ref "D201") (pin "3") (pinfunction "G_3") (pintype "passive"))
      (node (ref "D203") (pin "3") (pinfunction "G_3") (pintype "passive"))
      (node (ref "D210") (pin "3") (pinfunction "G_3") (pintype "passive"))
      (node (ref "D34") (pin "3") (pinfunction "G_3") (pintype "passive"))
      (node (ref "D35") (pin "3") (pinfunction "G_3") (pintype "passive"))
      (node (ref "D36") (pin "3") (pinfunction "G_3") (pintype "passive"))
      (node (ref "D37") (pin "3") (pinfunction "G_3") (pintype "passive"))
      (node (ref "D38") (pin "3") (pinfunction "G_3") (pintype "passive"))
      (node (ref "R12") (pin "2") (pinfunction "2_2") (pintype "passive"))
    )
    (net (code "32") (name "/GREEN4") (class "Default")
      (node (ref "D131") (pin "3") (pinfunction "G_3") (pintype "passive"))
      (node (ref "D132") (pin "3") (pinfunction "G_3") (pintype "passive"))
      (node (ref "D133") (pin "3") (pinfunction "G_3") (pintype "passive"))
      (node (ref "D134") (pin "3") (pinfunction "G_3") (pintype "passive"))
      (node (ref "D135") (pin "3") (pinfunction "G_3") (pintype "passive"))
      (node (ref "D205") (pin "3") (pinfunction "G_3") (pintype "passive"))
      (node (ref "D206") (pin "3") (pinfunction "G_3") (pintype "passive"))
      (node (ref "D207") (pin "3") (pinfunction "G_3") (pintype "passive"))
      (node (ref "D209") (pin "3") (pinfunction "G_3") (pintype "passive"))
      (node (ref "D39") (pin "3") (pinfunction "G_3") (pintype "passive"))
      (node (ref "D40") (pin "3") (pinfunction "G_3") (pintype "passive"))
      (node (ref "D41") (pin "3") (pinfunction "G_3") (pintype "passive"))
      (node (ref "D42") (pin "3") (pinfunction "G_3") (pintype "passive"))
      (node (ref "D43") (pin "3") (pinfunction "G_3") (pintype "passive"))
      (node (ref "R13") (pin "2") (pinfunction "2_2") (pintype "passive"))
    )
    (net (code "33") (name "/GREEN5") (class "Default")
      (node (ref "D152") (pin "3") (pinfunction "G_3") (pintype "passive"))
      (node (ref "D153") (pin "3") (pinfunction "G_3") (pintype "passive"))
      (node (ref "D154") (pin "3") (pinfunction "G_3") (pintype "passive"))
      (node (ref "D212") (pin "3") (pinfunction "G_3") (pintype "passive"))
      (node (ref "D213") (pin "3") (pinfunction "G_3") (pintype "passive"))
      (node (ref "D214") (pin "3") (pinfunction "G_3") (pintype "passive"))
      (node (ref "D215") (pin "3") (pinfunction "G_3") (pintype "passive"))
      (node (ref "D222") (pin "3") (pinfunction "G_3") (pintype "passive"))
      (node (ref "D57") (pin "3") (pinfunction "G_3") (pintype "passive"))
      (node (ref "D58") (pin "3") (pinfunction "G_3") (pintype "passive"))
      (node (ref "D59") (pin "3") (pinfunction "G_3") (pintype "passive"))
      (node (ref "D60") (pin "3") (pinfunction "G_3") (pintype "passive"))
      (node (ref "D61") (pin "3") (pinfunction "G_3") (pintype "passive"))
      (node (ref "R14") (pin "2") (pinfunction "2_2") (pintype "passive"))
    )
    (net (code "34") (name "/GREEN6") (class "Default")
      (node (ref "D157") (pin "3") (pinfunction "G_3") (pintype "passive"))
      (node (ref "D158") (pin "3") (pinfunction "G_3") (pintype "passive"))
      (node (ref "D159") (pin "3") (pinfunction "G_3") (pintype "passive"))
      (node (ref "D160") (pin "3") (pinfunction "G_3") (pintype "passive"))
      (node (ref "D161") (pin "3") (pinfunction "G_3") (pintype "passive"))
      (node (ref "D217") (pin "3") (pinfunction "G_3") (pintype "passive"))
      (node (ref "D218") (pin "3") (pinfunction "G_3") (pintype "passive"))
      (node (ref "D219") (pin "3") (pinfunction "G_3") (pintype "passive"))
      (node (ref "D220") (pin "3") (pinfunction "G_3") (pintype "passive"))
      (node (ref "D62") (pin "3") (pinfunction "G_3") (pintype "passive"))
      (node (ref "D63") (pin "3") (pinfunction "G_3") (pintype "passive"))
      (node (ref "D64") (pin "3") (pinfunction "G_3") (pintype "passive"))
      (node (ref "D65") (pin "3") (pinfunction "G_3") (pintype "passive"))
      (node (ref "D66") (pin "3") (pinfunction "G_3") (pintype "passive"))
      (node (ref "R15") (pin "2") (pinfunction "2_2") (pintype "passive"))
    )
    (net (code "35") (name "/GREEN7") (class "Default")
      (node (ref "R16") (pin "2") (pinfunction "2_2") (pintype "passive"))
    )
    (net (code "36") (name "/KEYPU0") (class "Default")
      (node (ref "*") (pin "21") (pinfunction "P4.0_21") (pintype "bidirectional"))
      (node (ref "R19") (pin "1") (pinfunction "1_1") (pintype "passive"))
      (node (ref "R27") (pin "1") (pinfunction "1_1") (pintype "passive"))
    )
    (net (code "37") (name "/KEYPU1") (class "Default")
      (node (ref "*") (pin "20") (pinfunction "P4.1_20") (pintype "bidirectional"))
      (node (ref "R20") (pin "1") (pinfunction "1_1") (pintype "passive"))
      (node (ref "R28") (pin "1") (pinfunction "1_1") (pintype "passive"))
    )
    (net (code "38") (name "/KEYPU2") (class "Default")
      (node (ref "*") (pin "15") (pinfunction "P4.2_15") (pintype "bidirectional"))
      (node (ref "R21") (pin "1") (pinfunction "1_1") (pintype "passive"))
      (node (ref "R29") (pin "1") (pinfunction "1_1") (pintype "passive"))
    )
    (net (code "39") (name "/KEYPU3") (class "Default")
      (node (ref "*") (pin "14") (pinfunction "P4.3_14") (pintype "bidirectional"))
      (node (ref "R22") (pin "1") (pinfunction "1_1") (pintype "passive"))
      (node (ref "R30") (pin "1") (pinfunction "1_1") (pintype "passive"))
    )
    (net (code "40") (name "/KEYPU4") (class "Default")
      (node (ref "*") (pin "6") (pinfunction "P4.4_6") (pintype "bidirectional"))
      (node (ref "R23") (pin "1") (pinfunction "1_1") (pintype "passive"))
      (node (ref "R31") (pin "1") (pinfunction "1_1") (pintype "passive"))
    )
    (net (code "41") (name "/KEYPU5") (class "Default")
      (node (ref "*") (pin "5") (pinfunction "P4.5_5") (pintype "bidirectional"))
      (node (ref "R24") (pin "1") (pinfunction "1_1") (pintype "passive"))
      (node (ref "R32") (pin "1") (pinfunction "1_1") (pintype "passive"))
    )
    (net (code "42") (name "/KEYPU6") (class "Default")
      (node (ref "*") (pin "16") (pinfunction "P4.6_16") (pintype "bidirectional"))
      (node (ref "R25") (pin "1") (pinfunction "1_1") (pintype "passive"))
      (node (ref "R33") (pin "1") (pinfunction "1_1") (pintype "passive"))
    )
    (net (code "43") (name "/KEYPU7") (class "Default")
      (node (ref "*") (pin "17") (pinfunction "P4.7_17") (pintype "bidirectional"))
      (node (ref "R26") (pin "1") (pinfunction "1_1") (pintype "passive"))
    )
    (net (code "44") (name "/KL0") (class "Default")
      (node (ref "D1") (pin "2") (pinfunction "COM_2") (pintype "passive"))
      (node (ref "D10") (pin "2") (pinfunction "COM_2") (pintype "passive"))
      (node (ref "D15") (pin "2") (pinfunction "COM_2") (pintype "passive"))
      (node (ref "D34") (pin "2") (pinfunction "COM_2") (pintype "passive"))
      (node (ref "D39") (pin "2") (pinfunction "COM_2") (pintype "passive"))
      (node (ref "D57") (pin "2") (pinfunction "COM_2") (pintype "passive"))
      (node (ref "D62") (pin "2") (pinfunction "COM_2") (pintype "passive"))
      (node (ref "Q2") (pin "3") (pinfunction "D_3") (pintype "input"))
    )
    (net (code "45") (name "/KL1") (class "Default")
      (node (ref "D11") (pin "2") (pinfunction "COM_2") (pintype "passive"))
      (node (ref "D16") (pin "2") (pinfunction "COM_2") (pintype "passive"))
      (node (ref "D2") (pin "2") (pinfunction "COM_2") (pintype "passive"))
      (node (ref "D35") (pin "2") (pinfunction "COM_2") (pintype "passive"))
      (node (ref "D40") (pin "2") (pinfunction "COM_2") (pintype "passive"))
      (node (ref "D58") (pin "2") (pinfunction "COM_2") (pintype "passive"))
      (node (ref "D63") (pin "2") (pinfunction "COM_2") (pintype "passive"))
      (node (ref "Q3") (pin "3") (pinfunction "D_3") (pintype "input"))
    )
    (net (code "46") (name "/KL2") (class "Default")
      (node (ref "D12") (pin "2") (pinfunction "COM_2") (pintype "passive"))
      (node (ref "D17") (pin "2") (pinfunction "COM_2") (pintype "passive"))
      (node (ref "D3") (pin "2") (pinfunction "COM_2") (pintype "passive"))
      (node (ref "D36") (pin "2") (pinfunction "COM_2") (pintype "passive"))
      (node (ref "D41") (pin "2") (pinfunction "COM_2") (pintype "passive"))
      (node (ref "D59") (pin "2") (pinfunction "COM_2") (pintype "passive"))
      (node (ref "D64") (pin "2") (pinfunction "COM_2") (pintype "passive"))
      (node (ref "Q4") (pin "3") (pinfunction "D_3") (pintype "input"))
    )
    (net (code "47") (name "/KL3") (class "Default")
      (node (ref "D13") (pin "2") (pinfunction "COM_2") (pintype "passive"))
      (node (ref "D18") (pin "2") (pinfunction "COM_2") (pintype "passive"))
      (node (ref "D37") (pin "2") (pinfunction "COM_2") (pintype "passive"))
      (node (ref "D4") (pin "2") (pinfunction "COM_2") (pintype "passive"))
      (node (ref "D42") (pin "2") (pinfunction "COM_2") (pintype "passive"))
      (node (ref "D60") (pin "2") (pinfunction "COM_2") (pintype "passive"))
      (node (ref "D65") (pin "2") (pinfunction "COM_2") (pintype "passive"))
      (node (ref "Q5") (pin "3") (pinfunction "D_3") (pintype "input"))
    )
    (net (code "48") (name "/KL4") (class "Default")
      (node (ref "D14") (pin "2") (pinfunction "COM_2") (pintype "passive"))
      (node (ref "D19") (pin "2") (pinfunction "COM_2") (pintype "passive"))
      (node (ref "D38") (pin "2") (pinfunction "COM_2") (pintype "passive"))
      (node (ref "D43") (pin "2") (pinfunction "COM_2") (pintype "passive"))
      (node (ref "D61") (pin "2") (pinfunction "COM_2") (pintype "passive"))
      (node (ref "D66") (pin "2") (pinfunction "COM_2") (pintype "passive"))
      (node (ref "D9") (pin "2") (pinfunction "COM_2") (pintype "passive"))
      (node (ref "Q6") (pin "3") (pinfunction "D_3") (pintype "input"))
    )
    (net (code "49") (name "/KL5") (class "Default")
      (node (ref "D100") (pin "2") (pinfunction "COM_2") (pintype "passive"))
      (node (ref "D105") (pin "2") (pinfunction "COM_2") (pintype "passive"))
      (node (ref "D126") (pin "2") (pinfunction "COM_2") (pintype "passive"))
      (node (ref "D131") (pin "2") (pinfunction "COM_2") (pintype "passive"))
      (node (ref "D152") (pin "2") (pinfunction "COM_2") (pintype "passive"))
      (node (ref "D157") (pin "2") (pinfunction "COM_2") (pintype "passive"))
      (node (ref "D80") (pin "2") (pinfunction "COM_2") (pintype "passive"))
      (node (ref "Q7") (pin "3") (pinfunction "D_3") (pintype "input"))
    )
    (net (code "50") (name "/KL6") (class "Default")
      (node (ref "D101") (pin "2") (pinfunction "COM_2") (pintype "passive"))
      (node (ref "D106") (pin "2") (pinfunction "COM_2") (pintype "passive"))
      (node (ref "D127") (pin "2") (pinfunction "COM_2") (pintype "passive"))
      (node (ref "D132") (pin "2") (pinfunction "COM_2") (pintype "passive"))
      (node (ref "D153") (pin "2") (pinfunction "COM_2") (pintype "passive"))
      (node (ref "D158") (pin "2") (pinfunction "COM_2") (pintype "passive"))
      (node (ref "D81") (pin "2") (pinfunction "COM_2") (pintype "passive"))
      (node (ref "Q8") (pin "3") (pinfunction "D_3") (pintype "input"))
    )
    (net (code "51") (name "/KL7") (class "Default")
      (node (ref "D102") (pin "2") (pinfunction "COM_2") (pintype "passive"))
      (node (ref "D107") (pin "2") (pinfunction "COM_2") (pintype "passive"))
      (node (ref "D128") (pin "2") (pinfunction "COM_2") (pintype "passive"))
      (node (ref "D133") (pin "2") (pinfunction "COM_2") (pintype "passive"))
      (node (ref "D154") (pin "2") (pinfunction "COM_2") (pintype "passive"))
      (node (ref "D159") (pin "2") (pinfunction "COM_2") (pintype "passive"))
      (node (ref "D82") (pin "2") (pinfunction "COM_2") (pintype "passive"))
      (node (ref "Q9") (pin "3") (pinfunction "D_3") (pintype "input"))
    )
    (net (code "52") (name "/KL8") (class "Default")
      (node (ref "D103") (pin "2") (pinfunction "COM_2") (pintype "passive"))
      (node (ref "D108") (pin "2") (pinfunction "COM_2") (pintype "passive"))
      (node (ref "D129") (pin "2") (pinfunction "COM_2") (pintype "passive"))
      (node (ref "D134") (pin "2") (pinfunction "COM_2") (pintype "passive"))
      (node (ref "D160") (pin "2") (pinfunction "COM_2") (pintype "passive"))
      (node (ref "D83") (pin "2") (pinfunction "COM_2") (pintype "passive"))
      (node (ref "Q10") (pin "3") (pinfunction "D_3") (pintype "input"))
    )
    (net (code "53") (name "/KL9") (class "Default")
      (node (ref "D104") (pin "2") (pinfunction "COM_2") (pintype "passive"))
      (node (ref "D109") (pin "2") (pinfunction "COM_2") (pintype "passive"))
      (node (ref "D130") (pin "2") (pinfunction "COM_2") (pintype "passive"))
      (node (ref "D135") (pin "2") (pinfunction "COM_2") (pintype "passive"))
      (node (ref "D161") (pin "2") (pinfunction "COM_2") (pintype "passive"))
      (node (ref "D84") (pin "2") (pinfunction "COM_2") (pintype "passive"))
      (node (ref "Q11") (pin "3") (pinfunction "D_3") (pintype "input"))
    )
    (net (code "54") (name "/KL10") (class "Default")
      (node (ref "D178") (pin "2") (pinfunction "COM_2") (pintype "passive"))
      (node (ref "D183") (pin "2") (pinfunction "COM_2") (pintype "passive"))
      (node (ref "D193") (pin "2") (pinfunction "COM_2") (pintype "passive"))
      (node (ref "D199") (pin "2") (pinfunction "COM_2") (pintype "passive"))
      (node (ref "D205") (pin "2") (pinfunction "COM_2") (pintype "passive"))
      (node (ref "D217") (pin "2") (pinfunction "COM_2") (pintype "passive"))
      (node (ref "Q12") (pin "3") (pinfunction "D_3") (pintype "input"))
    )
    (net (code "55") (name "/KL11") (class "Default")
      (node (ref "D179") (pin "2") (pinfunction "COM_2") (pintype "passive"))
      (node (ref "D184") (pin "2") (pinfunction "COM_2") (pintype "passive"))
      (node (ref "D194") (pin "2") (pinfunction "COM_2") (pintype "passive"))
      (node (ref "D200") (pin "2") (pinfunction "COM_2") (pintype "passive"))
      (node (ref "D206") (pin "2") (pinfunction "COM_2") (pintype "passive"))
      (node (ref "D212") (pin "2") (pinfunction "COM_2") (pintype "passive"))
      (node (ref "D218") (pin "2") (pinfunction "COM_2") (pintype "passive"))
      (node (ref "Q13") (pin "3") (pinfunction "D_3") (pintype "input"))
    )
    (net (code "56") (name "/KL12") (class "Default")
      (node (ref "D180") (pin "2") (pinfunction "COM_2") (pintype "passive"))
      (node (ref "D185") (pin "2") (pinfunction "COM_2") (pintype "passive"))
      (node (ref "D195") (pin "2") (pinfunction "COM_2") (pintype "passive"))
      (node (ref "D201") (pin "2") (pinfunction "COM_2") (pintype "passive"))
      (node (ref "D207") (pin "2") (pinfunction "COM_2") (pintype "passive"))
      (node (ref "D213") (pin "2") (pinfunction "COM_2") (pintype "passive"))
      (node (ref "D219") (pin "2") (pinfunction "COM_2") (pintype "passive"))
      (node (ref "Q14") (pin "3") (pinfunction "D_3") (pintype "input"))
    )
    (net (code "57") (name "/KL13") (class "Default")
      (node (ref "D181") (pin "2") (pinfunction "COM_2") (pintype "passive"))
      (node (ref "D186") (pin "2") (pinfunction "COM_2") (pintype "passive"))
      (node (ref "D196") (pin "2") (pinfunction "COM_2") (pintype "passive"))
      (node (ref "D214") (pin "2") (pinfunction "COM_2") (pintype "passive"))
      (node (ref "D220") (pin "2") (pinfunction "COM_2") (pintype "passive"))
      (node (ref "Q15") (pin "3") (pinfunction "D_3") (pintype "input"))
    )
    (net (code "58") (name "/KL14") (class "Default")
      (node (ref "D182") (pin "2") (pinfunction "COM_2") (pintype "passive"))
      (node (ref "D187") (pin "2") (pinfunction "COM_2") (pintype "passive"))
      (node (ref "D197") (pin "2") (pinfunction "COM_2") (pintype "passive"))
      (node (ref "D203") (pin "2") (pinfunction "COM_2") (pintype "passive"))
      (node (ref "D209") (pin "2") (pinfunction "COM_2") (pintype "passive"))
      (node (ref "D215") (pin "2") (pinfunction "COM_2") (pintype "passive"))
      (node (ref "Q16") (pin "3") (pinfunction "D_3") (pintype "input"))
    )
    (net (code "59") (name "/KL15") (class "Default")
      (node (ref "D189") (pin "2") (pinfunction "COM_2") (pintype "passive"))
      (node (ref "D198") (pin "2") (pinfunction "COM_2") (pintype "passive"))
      (node (ref "D204") (pin "2") (pinfunction "COM_2") (pintype "passive"))
      (node (ref "D210") (pin "2") (pinfunction "COM_2") (pintype "passive"))
      (node (ref "D222") (pin "2") (pinfunction "COM_2") (pintype "passive"))
      (node (ref "Q17") (pin "3") (pinfunction "D_3") (pintype "input"))
    )
    (net (code "60") (name "/RED0") (class "Default")
      (node (ref "D1") (pin "1") (pinfunction "R_1") (pintype "passive"))
      (node (ref "D178") (pin "1") (pinfunction "R_1") (pintype "passive"))
      (node (ref "D179") (pin "1") (pinfunction "R_1") (pintype "passive"))
      (node (ref "D180") (pin "1") (pinfunction "R_1") (pintype "passive"))
      (node (ref "D181") (pin "1") (pinfunction "R_1") (pintype "passive"))
      (node (ref "D182") (pin "1") (pinfunction "R_1") (pintype "passive"))
      (node (ref "D189") (pin "1") (pinfunction "R_1") (pintype "passive"))
      (node (ref "D2") (pin "1") (pinfunction "R_1") (pintype "passive"))
      (node (ref "D3") (pin "1") (pinfunction "R_1") (pintype "passive"))
      (node (ref "D4") (pin "1") (pinfunction "R_1") (pintype "passive"))
      (node (ref "D80") (pin "1") (pinfunction "R_1") (pintype "passive"))
      (node (ref "D81") (pin "1") (pinfunction "R_1") (pintype "passive"))
      (node (ref "D82") (pin "1") (pinfunction "R_1") (pintype "passive"))
      (node (ref "D83") (pin "1") (pinfunction "R_1") (pintype "passive"))
      (node (ref "D84") (pin "1") (pinfunction "R_1") (pintype "passive"))
      (node (ref "D9") (pin "1") (pinfunction "R_1") (pintype "passive"))
      (node (ref "R19") (pin "2") (pinfunction "2_2") (pintype "passive"))
    )
    (net (code "61") (name "/RED1") (class "Default")
      (node (ref "D10") (pin "1") (pinfunction "R_1") (pintype "passive"))
      (node (ref "D100") (pin "1") (pinfunction "R_1") (pintype "passive"))
      (node (ref "D101") (pin "1") (pinfunction "R_1") (pintype "passive"))
      (node (ref "D102") (pin "1") (pinfunction "R_1") (pintype "passive"))
      (node (ref "D103") (pin "1") (pinfunction "R_1") (pintype "passive"))
      (node (ref "D104") (pin "1") (pinfunction "R_1") (pintype "passive"))
      (node (ref "D11") (pin "1") (pinfunction "R_1") (pintype "passive"))
      (node (ref "D12") (pin "1") (pinfunction "R_1") (pintype "passive"))
      (node (ref "D13") (pin "1") (pinfunction "R_1") (pintype "passive"))
      (node (ref "D14") (pin "1") (pinfunction "R_1") (pintype "passive"))
      (node (ref "D183") (pin "1") (pinfunction "R_1") (pintype "passive"))
      (node (ref "D184") (pin "1") (pinfunction "R_1") (pintype "passive"))
      (node (ref "D185") (pin "1") (pinfunction "R_1") (pintype "passive"))
      (node (ref "D186") (pin "1") (pinfunction "R_1") (pintype "passive"))
      (node (ref "D187") (pin "1") (pinfunction "R_1") (pintype "passive"))
      (node (ref "D198") (pin "1") (pinfunction "R_1") (pintype "passive"))
      (node (ref "R20") (pin "2") (pinfunction "2_2") (pintype "passive"))
    )
    (net (code "62") (name "/RED2") (class "Default")
      (node (ref "D105") (pin "1") (pinfunction "R_1") (pintype "passive"))
      (node (ref "D106") (pin "1") (pinfunction "R_1") (pintype "passive"))
      (node (ref "D107") (pin "1") (pinfunction "R_1") (pintype "passive"))
      (node (ref "D108") (pin "1") (pinfunction "R_1") (pintype "passive"))
      (node (ref "D109") (pin "1") (pinfunction "R_1") (pintype "passive"))
      (node (ref "D15") (pin "1") (pinfunction "R_1") (pintype "passive"))
      (node (ref "D16") (pin "1") (pinfunction "R_1") (pintype "passive"))
      (node (ref "D17") (pin "1") (pinfunction "R_1") (pintype "passive"))
      (node (ref "D18") (pin "1") (pinfunction "R_1") (pintype "passive"))
      (node (ref "D19") (pin "1") (pinfunction "R_1") (pintype "passive"))
      (node (ref "D193") (pin "1") (pinfunction "R_1") (pintype "passive"))
      (node (ref "D194") (pin "1") (pinfunction "R_1") (pintype "passive"))
      (node (ref "D195") (pin "1") (pinfunction "R_1") (pintype "passive"))
      (node (ref "D196") (pin "1") (pinfunction "R_1") (pintype "passive"))
      (node (ref "D197") (pin "1") (pinfunction "R_1") (pintype "passive"))
      (node (ref "D204") (pin "1") (pinfunction "R_1") (pintype "passive"))
      (node (ref "R21") (pin "2") (pinfunction "2_2") (pintype "passive"))
    )
    (net (code "63") (name "/RED3") (class "Default")
      (node (ref "D126") (pin "1") (pinfunction "R_1") (pintype "passive"))
      (node (ref "D127") (pin "1") (pinfunction "R_1") (pintype "passive"))
      (node (ref "D128") (pin "1") (pinfunction "R_1") (pintype "passive"))
      (node (ref "D129") (pin "1") (pinfunction "R_1") (pintype "passive"))
      (node (ref "D130") (pin "1") (pinfunction "R_1") (pintype "passive"))
      (node (ref "D199") (pin "1") (pinfunction "R_1") (pintype "passive"))
      (node (ref "D200") (pin "1") (pinfunction "R_1") (pintype "passive"))
      (node (ref "D201") (pin "1") (pinfunction "R_1") (pintype "passive"))
      (node (ref "D203") (pin "1") (pinfunction "R_1") (pintype "passive"))
      (node (ref "D210") (pin "1") (pinfunction "R_1") (pintype "passive"))
      (node (ref "D34") (pin "1") (pinfunction "R_1") (pintype "passive"))
      (node (ref "D35") (pin "1") (pinfunction "R_1") (pintype "passive"))
      (node (ref "D36") (pin "1") (pinfunction "R_1") (pintype "passive"))
      (node (ref "D37") (pin "1") (pinfunction "R_1") (pintype "passive"))
      (node (ref "D38") (pin "1") (pinfunction "R_1") (pintype "passive"))
      (node (ref "R22") (pin "2") (pinfunction "2_2") (pintype "passive"))
    )
    (net (code "64") (name "/RED4") (class "Default")
      (node (ref "D131") (pin "1") (pinfunction "R_1") (pintype "passive"))
      (node (ref "D132") (pin "1") (pinfunction "R_1") (pintype "passive"))
      (node (ref "D133") (pin "1") (pinfunction "R_1") (pintype "passive"))
      (node (ref "D134") (pin "1") (pinfunction "R_1") (pintype "passive"))
      (node (ref "D135") (pin "1") (pinfunction "R_1") (pintype "passive"))
      (node (ref "D205") (pin "1") (pinfunction "R_1") (pintype "passive"))
      (node (ref "D206") (pin "1") (pinfunction "R_1") (pintype "passive"))
      (node (ref "D207") (pin "1") (pinfunction "R_1") (pintype "passive"))
      (node (ref "D209") (pin "1") (pinfunction "R_1") (pintype "passive"))
      (node (ref "D39") (pin "1") (pinfunction "R_1") (pintype "passive"))
      (node (ref "D40") (pin "1") (pinfunction "R_1") (pintype "passive"))
      (node (ref "D41") (pin "1") (pinfunction "R_1") (pintype "passive"))
      (node (ref "D42") (pin "1") (pinfunction "R_1") (pintype "passive"))
      (node (ref "D43") (pin "1") (pinfunction "R_1") (pintype "passive"))
      (node (ref "R23") (pin "2") (pinfunction "2_2") (pintype "passive"))
    )
    (net (code "65") (name "/RED5") (class "Default")
      (node (ref "D152") (pin "1") (pinfunction "R_1") (pintype "passive"))
      (node (ref "D153") (pin "1") (pinfunction "R_1") (pintype "passive"))
      (node (ref "D154") (pin "1") (pinfunction "R_1") (pintype "passive"))
      (node (ref "D212") (pin "1") (pinfunction "R_1") (pintype "passive"))
      (node (ref "D213") (pin "1") (pinfunction "R_1") (pintype "passive"))
      (node (ref "D214") (pin "1") (pinfunction "R_1") (pintype "passive"))
      (node (ref "D215") (pin "1") (pinfunction "R_1") (pintype "passive"))
      (node (ref "D222") (pin "1") (pinfunction "R_1") (pintype "passive"))
      (node (ref "D57") (pin "1") (pinfunction "R_1") (pintype "passive"))
      (node (ref "D58") (pin "1") (pinfunction "R_1") (pintype "passive"))
      (node (ref "D59") (pin "1") (pinfunction "R_1") (pintype "passive"))
      (node (ref "D60") (pin "1") (pinfunction "R_1") (pintype "passive"))
      (node (ref "D61") (pin "1") (pinfunction "R_1") (pintype "passive"))
      (node (ref "R24") (pin "2") (pinfunction "2_2") (pintype "passive"))
    )
    (net (code "66") (name "/RED6") (class "Default")
      (node (ref "D157") (pin "1") (pinfunction "R_1") (pintype "passive"))
      (node (ref "D158") (pin "1") (pinfunction "R_1") (pintype "passive"))
      (node (ref "D159") (pin "1") (pinfunction "R_1") (pintype "passive"))
      (node (ref "D160") (pin "1") (pinfunction "R_1") (pintype "passive"))
      (node (ref "D161") (pin "1") (pinfunction "R_1") (pintype "passive"))
      (node (ref "D217") (pin "1") (pinfunction "R_1") (pintype "passive"))
      (node (ref "D218") (pin "1") (pinfunction "R_1") (pintype "passive"))
      (node (ref "D219") (pin "1") (pinfunction "R_1") (pintype "passive"))
      (node (ref "D220") (pin "1") (pinfunction "R_1") (pintype "passive"))
      (node (ref "D62") (pin "1") (pinfunction "R_1") (pintype "passive"))
      (node (ref "D63") (pin "1") (pinfunction "R_1") (pintype "passive"))
      (node (ref "D64") (pin "1") (pinfunction "R_1") (pintype "passive"))
      (node (ref "D65") (pin "1") (pinfunction "R_1") (pintype "passive"))
      (node (ref "D66") (pin "1") (pinfunction "R_1") (pintype "passive"))
      (node (ref "R25") (pin "2") (pinfunction "2_2") (pintype "passive"))
    )
    (net (code "67") (name "/RED7") (class "Default")
      (node (ref "R26") (pin "2") (pinfunction "2_2") (pintype "passive"))
    )
    (net (code "68") (name "/UD+") (class "Default")
      (node (ref "*") (pin "30") (pinfunction "P6.1/DP_30") (pintype "bidirectional"))
      (node (ref "P2") (pin "3") (pinfunction "UD+_3") (pintype "bidirectional"))
    )
    (net (code "69") (name "/UD-") (class "Default")
      (node (ref "*") (pin "31") (pinfunction "P6.0/DM_31") (pintype "bidirectional"))
      (node (ref "P2") (pin "2") (pinfunction "UD-_2") (pintype "bidirectional"))
    )
    (net (code "70") (name "4V8") (class "Default")
      (node (ref "C3") (pin "1") (pinfunction "1_1") (pintype "passive"))
      (node (ref "C6") (pin "1") (pinfunction "1_1") (pintype "passive"))
      (node (ref "L1") (pin "1") (pinfunction "1_1") (pintype "passive"))
      (node (ref "P2") (pin "1") (pinfunction "+5V_1") (pintype "power_in"))
      (node (ref "R312") (pin "1") (pintype "passive"))
    )
    (net (code "71") (name "5V4") (class "Default")
      (node (ref "*") (pin "40") (pinfunction "VDD_40") (pintype "power_in"))
      (node (ref "C1") (pin "1") (pinfunction "1_1") (pintype "passive"))
      (node (ref "C11") (pin "1") (pinfunction "1_1") (pintype "passive"))
      (node (ref "C4") (pin "1") (pinfunction "1_1") (pintype "passive"))
      (node (ref "C9") (pin "1") (pintype "passive"))
      (node (ref "D221") (pin "2") (pinfunction "K_2") (pintype "passive"))
      (node (ref "Q10") (pin "2") (pinfunction "S_2") (pintype "input"))
      (node (ref "Q11") (pin "2") (pinfunction "S_2") (pintype "input"))
      (node (ref "Q12") (pin "2") (pinfunction "S_2") (pintype "input"))
      (node (ref "Q13") (pin "2") (pinfunction "S_2") (pintype "input"))
      (node (ref "Q14") (pin "2") (pinfunction "S_2") (pintype "input"))
      (node (ref "Q15") (pin "2") (pinfunction "S_2") (pintype "input"))
      (node (ref "Q16") (pin "2") (pinfunction "S_2") (pintype "input"))
      (node (ref "Q17") (pin "2") (pinfunction "S_2") (pintype "input"))
      (node (ref "Q2") (pin "2") (pinfunction "S_2") (pintype "input"))
      (node (ref "Q3") (pin "2") (pinfunction "S_2") (pintype "input"))
      (node (ref "Q4") (pin "2") (pinfunction "S_2") (pintype "input"))
      (node (ref "Q5") (pin "2") (pinfunction "S_2") (pintype "input"))
      (node (ref "Q6") (pin "2") (pinfunction "S_2") (pintype "input"))
      (node (ref "Q7") (pin "2") (pinfunction "S_2") (pintype "input"))
      (node (ref "Q8") (pin "2") (pinfunction "S_2") (pintype "input"))
      (node (ref "Q9") (pin "2") (pinfunction "S_2") (pintype "input"))
      (node (ref "R312") (pin "2") (pintype "passive"))
    )
    (net (code "72") (name "GND") (class "Default")
      (node (ref "*") (pin "41") (pinfunction "GND/VSS_41") (pintype "power_in"))
      (node (ref "C1") (pin "2") (pinfunction "2_2") (pintype "passive"))
      (node (ref "C11") (pin "2") (pinfunction "2_2") (pintype "passive"))
      (node (ref "C3") (pin "2") (pinfunction "2_2") (pintype "passive"))
      (node (ref "C4") (pin "2") (pinfunction "2_2") (pintype "passive"))
      (node (ref "C5") (pin "2") (pinfunction "2_2") (pintype "passive"))
      (node (ref "C6") (pin "2") (pinfunction "2_2") (pintype "passive"))
      (node (ref "C9") (pin "2") (pintype "passive"))
      (node (ref "P2") (pin "4") (pinfunction "GND_4") (pintype "power_in"))
      (node (ref "P2") (pin "5") (pinfunction "GND_5") (pintype "power_in"))
      (node (ref "P2") (pin "6") (pinfunction "GND_6") (pintype "power_in"))
      (node (ref "Q18") (pin "2") (pinfunction "S_2") (pintype "input"))
      (node (ref "SW1") (pin "2") (pintype "passive"))
    )
    (net (code "73") (name "Net-(*-P1.0{slash}T2{slash}CAP1{slash}AIN0)") (class "Default")
      (node (ref "*") (pin "43") (pinfunction "P1.0/T2/CAP1/AIN0_43") (pintype "bidirectional"))
      (node (ref "R1") (pin "2") (pinfunction "2_2") (pintype "passive"))
    )
    (net (code "74") (name "Net-(*-P1.1{slash}T2EX{slash}CAP2{slash}AIN1)") (class "Default")
      (node (ref "*") (pin "44") (pinfunction "P1.1/T2EX/CAP2/AIN1_44") (pintype "bidirectional"))
      (node (ref "R2") (pin "2") (pinfunction "2_2") (pintype "passive"))
    )
    (net (code "75") (name "Net-(*-P1.2{slash}INT0_{slash}AIN2)") (class "Default")
      (node (ref "*") (pin "45") (pinfunction "P1.2/INT0_/AIN2_45") (pintype "bidirectional"))
      (node (ref "R3") (pin "2") (pinfunction "2_2") (pintype "passive"))
    )
    (net (code "76") (name "Net-(*-P1.3{slash}AIN3)") (class "Default")
      (node (ref "*") (pin "46") (pinfunction "P1.3/AIN3_46") (pintype "bidirectional"))
      (node (ref "R4") (pin "2") (pinfunction "2_2") (pintype "passive"))
    )
    (net (code "77") (name "Net-(*-P1.4{slash}SCS{slash}AIN4)") (class "Default")
      (node (ref "*") (pin "47") (pinfunction "P1.4/SCS/AIN4_47") (pintype "bidirectional"))
      (node (ref "R5") (pin "2") (pinfunction "2_2") (pintype "passive"))
    )
    (net (code "78") (name "Net-(*-P1.5{slash}MOSI{slash}AIN5)") (class "Default")
      (node (ref "*") (pin "48") (pinfunction "P1.5/MOSI/AIN5_48") (pintype "bidirectional"))
      (node (ref "R6") (pin "2") (pinfunction "2_2") (pintype "passive"))
    )
    (net (code "79") (name "Net-(*-P1.6{slash}MISO{slash}RXD1_{slash}AIN6)") (class "Default")
      (node (ref "*") (pin "1") (pinfunction "P1.6/MISO/RXD1_/AIN6_1") (pintype "bidirectional"))
      (node (ref "R7") (pin "1") (pinfunction "1_1") (pintype "passive"))
    )
    (net (code "80") (name "Net-(*-P1.7{slash}SCK{slash}TXD1_{slash}AIN7)") (class "Default")
      (node (ref "*") (pin "2") (pinfunction "P1.7/SCK/TXD1_/AIN7_2") (pintype "bidirectional"))
      (node (ref "R8") (pin "2") (pinfunction "2_2") (pintype "passive"))
    )
    (net (code "81") (name "Net-(*-P2.0)") (class "Default")
      (node (ref "*") (pin "22") (pinfunction "P2.0_22") (pintype "bidirectional"))
      (node (ref "R9") (pin "1") (pinfunction "1_1") (pintype "passive"))
    )
    (net (code "82") (name "Net-(*-P2.1)") (class "Default")
      (node (ref "*") (pin "23") (pinfunction "P2.1_23") (pintype "bidirectional"))
      (node (ref "R10") (pin "1") (pinfunction "1_1") (pintype "passive"))
    )
    (net (code "83") (name "Net-(*-P2.2)") (class "Default")
      (node (ref "*") (pin "24") (pinfunction "P2.2_24") (pintype "bidirectional"))
      (node (ref "R11") (pin "1") (pinfunction "1_1") (pintype "passive"))
    )
    (net (code "84") (name "Net-(*-P2.3)") (class "Default")
      (node (ref "*") (pin "25") (pinfunction "P2.3_25") (pintype "bidirectional"))
      (node (ref "R12") (pin "1") (pinfunction "1_1") (pintype "passive"))
    )
    (net (code "85") (name "Net-(*-P2.4{slash}T2_{slash}CAP1_)") (class "Default")
      (node (ref "*") (pin "26") (pinfunction "P2.4/T2_/CAP1__26") (pintype "bidirectional"))
      (node (ref "R13") (pin "1") (pinfunction "1_1") (pintype "passive"))
    )
    (net (code "86") (name "Net-(*-P2.5{slash}T2EX_{slash}CAP2_)") (class "Default")
      (node (ref "*") (pin "27") (pinfunction "P2.5/T2EX_/CAP2__27") (pintype "bidirectional"))
      (node (ref "R14") (pin "1") (pinfunction "1_1") (pintype "passive"))
    )
    (net (code "87") (name "Net-(*-P2.6{slash}RXD1)") (class "Default")
      (node (ref "*") (pin "28") (pinfunction "P2.6/RXD1_28") (pintype "bidirectional"))
      (node (ref "R15") (pin "1") (pinfunction "1_1") (pintype "passive"))
    )
    (net (code "88") (name "Net-(*-P2.7{slash}TXD1)") (class "Default")
      (node (ref "*") (pin "29") (pinfunction "P2.7/TXD1_29") (pintype "bidirectional"))
      (node (ref "R16") (pin "1") (pinfunction "1_1") (pintype "passive"))
    )
    (net (code "89") (name "Net-(*-V33)") (class "Default")
      (node (ref "*") (pin "42") (pinfunction "V33_42") (pintype "power_in"))
      (node (ref "C5") (pin "1") (pinfunction "1_1") (pintype "passive"))
    )
    (net (code "90") (name "Net-(D5-A)") (class "Default")
      (node (ref "D5") (pin "1") (pinfunction "A_1") (pintype "passive"))
      (node (ref "SW105") (pin "1") (pintype "passive"))
    )
    (net (code "91") (name "Net-(D20-A)") (class "Default")
      (node (ref "D20") (pin "1") (pinfunction "A_1") (pintype "passive"))
      (node (ref "SW2") (pin "1") (pintype "passive"))
    )
    (net (code "92") (name "Net-(D21-A)") (class "Default")
      (node (ref "D21") (pin "1") (pinfunction "A_1") (pintype "passive"))
      (node (ref "SW3") (pin "1") (pintype "passive"))
    )
    (net (code "93") (name "Net-(D22-A)") (class "Default")
      (node (ref "D22") (pin "1") (pinfunction "A_1") (pintype "passive"))
      (node (ref "SW4") (pin "1") (pintype "passive"))
    )
    (net (code "94") (name "Net-(D23-A)") (class "Default")
      (node (ref "D23") (pin "1") (pinfunction "A_1") (pintype "passive"))
      (node (ref "SW5") (pin "1") (pintype "passive"))
    )
    (net (code "95") (name "Net-(D24-A)") (class "Default")
      (node (ref "D24") (pin "1") (pinfunction "A_1") (pintype "passive"))
      (node (ref "SW6") (pin "1") (pintype "passive"))
    )
    (net (code "96") (name "Net-(D25-A)") (class "Default")
      (node (ref "D25") (pin "1") (pinfunction "A_1") (pintype "passive"))
      (node (ref "SW7") (pin "1") (pintype "passive"))
    )
    (net (code "97") (name "Net-(D26-A)") (class "Default")
      (node (ref "D26") (pin "1") (pinfunction "A_1") (pintype "passive"))
      (node (ref "SW8") (pin "1") (pintype "passive"))
    )
    (net (code "98") (name "Net-(D27-A)") (class "Default")
      (node (ref "D27") (pin "1") (pinfunction "A_1") (pintype "passive"))
      (node (ref "SW9") (pin "1") (pintype "passive"))
    )
    (net (code "99") (name "Net-(D28-A)") (class "Default")
      (node (ref "D28") (pin "1") (pinfunction "A_1") (pintype "passive"))
      (node (ref "SW10") (pin "1") (pintype "passive"))
    )
    (net (code "100") (name "Net-(D29-A)") (class "Default")
      (node (ref "D29") (pin "1") (pinfunction "A_1") (pintype "passive"))
      (node (ref "SW11") (pin "1") (pintype "passive"))
    )
    (net (code "101") (name "Net-(D30-A)") (class "Default")
      (node (ref "D30") (pin "1") (pinfunction "A_1") (pintype "passive"))
      (node (ref "SW12") (pin "1") (pintype "passive"))
    )
    (net (code "102") (name "Net-(D31-A)") (class "Default")
      (node (ref "D31") (pin "1") (pinfunction "A_1") (pintype "passive"))
      (node (ref "SW13") (pin "1") (pintype "passive"))
    )
    (net (code "103") (name "Net-(D32-A)") (class "Default")
      (node (ref "D32") (pin "1") (pinfunction "A_1") (pintype "passive"))
      (node (ref "SW14") (pin "1") (pintype "passive"))
    )
    (net (code "104") (name "Net-(D33-A)") (class "Default")
      (node (ref "D33") (pin "1") (pinfunction "A_1") (pintype "passive"))
      (node (ref "SW15") (pin "1") (pintype "passive"))
    )
    (net (code "105") (name "Net-(D44-A)") (class "Default")
      (node (ref "D44") (pin "1") (pinfunction "A_1") (pintype "passive"))
      (node (ref "SW16") (pin "1") (pintype "passive"))
    )
    (net (code "106") (name "Net-(D45-A)") (class "Default")
      (node (ref "D45") (pin "1") (pinfunction "A_1") (pintype "passive"))
      (node (ref "SW17") (pin "1") (pintype "passive"))
    )
    (net (code "107") (name "Net-(D46-A)") (class "Default")
      (node (ref "D46") (pin "1") (pinfunction "A_1") (pintype "passive"))
      (node (ref "SW18") (pin "1") (pintype "passive"))
    )
    (net (code "108") (name "Net-(D47-A)") (class "Default")
      (node (ref "D47") (pin "1") (pinfunction "A_1") (pintype "passive"))
      (node (ref "SW19") (pin "1") (pintype "passive"))
    )
    (net (code "109") (name "Net-(D48-A)") (class "Default")
      (node (ref "D48") (pin "1") (pinfunction "A_1") (pintype "passive"))
      (node (ref "SW20") (pin "1") (pintype "passive"))
    )
    (net (code "110") (name "Net-(D49-A)") (class "Default")
      (node (ref "D49") (pin "1") (pinfunction "A_1") (pintype "passive"))
      (node (ref "SW21") (pin "1") (pintype "passive"))
    )
    (net (code "111") (name "Net-(D50-A)") (class "Default")
      (node (ref "D50") (pin "1") (pinfunction "A_1") (pintype "passive"))
      (node (ref "SW22") (pin "1") (pintype "passive"))
    )
    (net (code "112") (name "Net-(D51-A)") (class "Default")
      (node (ref "D51") (pin "1") (pinfunction "A_1") (pintype "passive"))
      (node (ref "SW23") (pin "1") (pintype "passive"))
    )
    (net (code "113") (name "Net-(D52-A)") (class "Default")
      (node (ref "D52") (pin "1") (pinfunction "A_1") (pintype "passive"))
      (node (ref "SW24") (pin "1") (pintype "passive"))
    )
    (net (code "114") (name "Net-(D53-A)") (class "Default")
      (node (ref "D53") (pin "1") (pinfunction "A_1") (pintype "passive"))
      (node (ref "SW25") (pin "1") (pintype "passive"))
    )
    (net (code "115") (name "Net-(D54-A)") (class "Default")
      (node (ref "D54") (pin "1") (pinfunction "A_1") (pintype "passive"))
      (node (ref "SW26") (pin "1") (pintype "passive"))
    )
    (net (code "116") (name "Net-(D55-A)") (class "Default")
      (node (ref "D55") (pin "1") (pinfunction "A_1") (pintype "passive"))
      (node (ref "SW27") (pin "1") (pintype "passive"))
    )
    (net (code "117") (name "Net-(D56-A)") (class "Default")
      (node (ref "D56") (pin "1") (pinfunction "A_1") (pintype "passive"))
      (node (ref "SW28") (pin "1") (pintype "passive"))
    )
    (net (code "118") (name "Net-(D67-A)") (class "Default")
      (node (ref "D67") (pin "1") (pinfunction "A_1") (pintype "passive"))
      (node (ref "SW29") (pin "1") (pintype "passive"))
    )
    (net (code "119") (name "Net-(D68-A)") (class "Default")
      (node (ref "D68") (pin "1") (pinfunction "A_1") (pintype "passive"))
      (node (ref "SW30") (pin "1") (pintype "passive"))
    )
    (net (code "120") (name "Net-(D69-A)") (class "Default")
      (node (ref "D69") (pin "1") (pinfunction "A_1") (pintype "passive"))
      (node (ref "SW31") (pin "1") (pintype "passive"))
    )
    (net (code "121") (name "Net-(D70-A)") (class "Default")
      (node (ref "D70") (pin "1") (pinfunction "A_1") (pintype "passive"))
      (node (ref "SW32") (pin "1") (pintype "passive"))
    )
    (net (code "122") (name "Net-(D71-A)") (class "Default")
      (node (ref "D71") (pin "1") (pinfunction "A_1") (pintype "passive"))
      (node (ref "SW33") (pin "1") (pintype "passive"))
    )
    (net (code "123") (name "Net-(D72-A)") (class "Default")
      (node (ref "D72") (pin "1") (pinfunction "A_1") (pintype "passive"))
      (node (ref "SW34") (pin "1") (pintype "passive"))
    )
    (net (code "124") (name "Net-(D73-A)") (class "Default")
      (node (ref "D73") (pin "1") (pinfunction "A_1") (pintype "passive"))
      (node (ref "SW35") (pin "1") (pintype "passive"))
    )
    (net (code "125") (name "Net-(D74-A)") (class "Default")
      (node (ref "D74") (pin "1") (pinfunction "A_1") (pintype "passive"))
      (node (ref "SW36") (pin "1") (pintype "passive"))
    )
    (net (code "126") (name "Net-(D75-A)") (class "Default")
      (node (ref "D75") (pin "1") (pinfunction "A_1") (pintype "passive"))
      (node (ref "SW37") (pin "1") (pintype "passive"))
    )
    (net (code "127") (name "Net-(D76-A)") (class "Default")
      (node (ref "D76") (pin "1") (pinfunction "A_1") (pintype "passive"))
      (node (ref "SW38") (pin "1") (pintype "passive"))
    )
    (net (code "128") (name "Net-(D77-A)") (class "Default")
      (node (ref "D77") (pin "1") (pinfunction "A_1") (pintype "passive"))
      (node (ref "SW39") (pin "1") (pintype "passive"))
    )
    (net (code "129") (name "Net-(D78-A)") (class "Default")
      (node (ref "D78") (pin "1") (pinfunction "A_1") (pintype "passive"))
      (node (ref "SW40") (pin "1") (pintype "passive"))
    )
    (net (code "130") (name "Net-(D79-A)") (class "Default")
      (node (ref "D79") (pin "1") (pinfunction "A_1") (pintype "passive"))
      (node (ref "SW41") (pin "1") (pintype "passive"))
    )
    (net (code "131") (name "Net-(D85-A)") (class "Default")
      (node (ref "D85") (pin "1") (pinfunction "A_1") (pintype "passive"))
      (node (ref "SW42") (pin "1") (pintype "passive"))
    )
    (net (code "132") (name "Net-(D86-A)") (class "Default")
      (node (ref "D86") (pin "1") (pinfunction "A_1") (pintype "passive"))
      (node (ref "SW43") (pin "1") (pintype "passive"))
    )
    (net (code "133") (name "Net-(D87-A)") (class "Default")
      (node (ref "D87") (pin "1") (pinfunction "A_1") (pintype "passive"))
      (node (ref "SW44") (pin "1") (pintype "passive"))
    )
    (net (code "134") (name "Net-(D88-A)") (class "Default")
      (node (ref "D88") (pin "1") (pinfunction "A_1") (pintype "passive"))
      (node (ref "SW45") (pin "1") (pintype "passive"))
    )
    (net (code "135") (name "Net-(D89-A)") (class "Default")
      (node (ref "D89") (pin "1") (pinfunction "A_1") (pintype "passive"))
      (node (ref "SW46") (pin "1") (pintype "passive"))
    )
    (net (code "136") (name "Net-(D90-A)") (class "Default")
      (node (ref "D90") (pin "1") (pinfunction "A_1") (pintype "passive"))
      (node (ref "SW47") (pin "1") (pintype "passive"))
    )
    (net (code "137") (name "Net-(D91-A)") (class "Default")
      (node (ref "D91") (pin "1") (pinfunction "A_1") (pintype "passive"))
      (node (ref "SW48") (pin "1") (pintype "passive"))
    )
    (net (code "138") (name "Net-(D92-A)") (class "Default")
      (node (ref "D92") (pin "1") (pinfunction "A_1") (pintype "passive"))
      (node (ref "SW49") (pin "1") (pintype "passive"))
    )
    (net (code "139") (name "Net-(D93-A)") (class "Default")
      (node (ref "D93") (pin "1") (pinfunction "A_1") (pintype "passive"))
      (node (ref "SW50") (pin "1") (pintype "passive"))
    )
    (net (code "140") (name "Net-(D94-A)") (class "Default")
      (node (ref "D94") (pin "1") (pinfunction "A_1") (pintype "passive"))
      (node (ref "SW51") (pin "1") (pintype "passive"))
    )
    (net (code "141") (name "Net-(D95-A)") (class "Default")
      (node (ref "D95") (pin "1") (pinfunction "A_1") (pintype "passive"))
      (node (ref "SW52") (pin "1") (pintype "passive"))
    )
    (net (code "142") (name "Net-(D96-A)") (class "Default")
      (node (ref "D96") (pin "1") (pinfunction "A_1") (pintype "passive"))
      (node (ref "SW53") (pin "1") (pintype "passive"))
    )
    (net (code "143") (name "Net-(D97-A)") (class "Default")
      (node (ref "D97") (pin "1") (pinfunction "A_1") (pintype "passive"))
      (node (ref "SW54") (pin "1") (pintype "passive"))
    )
    (net (code "144") (name "Net-(D98-A)") (class "Default")
      (node (ref "D98") (pin "1") (pinfunction "A_1") (pintype "passive"))
      (node (ref "SW55") (pin "1") (pintype "passive"))
    )
    (net (code "145") (name "Net-(D99-A)") (class "Default")
      (node (ref "D99") (pin "1") (pinfunction "A_1") (pintype "passive"))
      (node (ref "SW56") (pin "1") (pintype "passive"))
    )
    (net (code "146") (name "Net-(D110-A)") (class "Default")
      (node (ref "D110") (pin "1") (pinfunction "A_1") (pintype "passive"))
      (node (ref "SW57") (pin "1") (pintype "passive"))
    )
    (net (code "147") (name "Net-(D111-A)") (class "Default")
      (node (ref "D111") (pin "1") (pinfunction "A_1") (pintype "passive"))
      (node (ref "SW58") (pin "1") (pintype "passive"))
    )
    (net (code "148") (name "Net-(D112-A)") (class "Default")
      (node (ref "D112") (pin "1") (pinfunction "A_1") (pintype "passive"))
      (node (ref "SW59") (pin "1") (pintype "passive"))
    )
    (net (code "149") (name "Net-(D113-A)") (class "Default")
      (node (ref "D113") (pin "1") (pinfunction "A_1") (pintype "passive"))
      (node (ref "SW60") (pin "1") (pintype "passive"))
    )
    (net (code "150") (name "Net-(D114-A)") (class "Default")
      (node (ref "D114") (pin "1") (pinfunction "A_1") (pintype "passive"))
      (node (ref "SW61") (pin "1") (pintype "passive"))
    )
    (net (code "151") (name "Net-(D115-A)") (class "Default")
      (node (ref "D115") (pin "1") (pinfunction "A_1") (pintype "passive"))
      (node (ref "SW62") (pin "1") (pintype "passive"))
    )
    (net (code "152") (name "Net-(D116-A)") (class "Default")
      (node (ref "D116") (pin "1") (pinfunction "A_1") (pintype "passive"))
      (node (ref "SW63") (pin "1") (pintype "passive"))
    )
    (net (code "153") (name "Net-(D117-A)") (class "Default")
      (node (ref "D117") (pin "1") (pinfunction "A_1") (pintype "passive"))
      (node (ref "SW64") (pin "1") (pintype "passive"))
    )
    (net (code "154") (name "Net-(D118-A)") (class "Default")
      (node (ref "D118") (pin "1") (pinfunction "A_1") (pintype "passive"))
      (node (ref "SW65") (pin "1") (pintype "passive"))
    )
    (net (code "155") (name "Net-(D119-A)") (class "Default")
      (node (ref "D119") (pin "1") (pinfunction "A_1") (pintype "passive"))
      (node (ref "SW66") (pin "1") (pintype "passive"))
    )
    (net (code "156") (name "Net-(D120-A)") (class "Default")
      (node (ref "D120") (pin "1") (pinfunction "A_1") (pintype "passive"))
      (node (ref "SW67") (pin "1") (pintype "passive"))
    )
    (net (code "157") (name "Net-(D121-A)") (class "Default")
      (node (ref "D121") (pin "1") (pinfunction "A_1") (pintype "passive"))
      (node (ref "SW68") (pin "1") (pintype "passive"))
    )
    (net (code "158") (name "Net-(D122-A)") (class "Default")
      (node (ref "D122") (pin "1") (pinfunction "A_1") (pintype "passive"))
      (node (ref "SW69") (pin "1") (pintype "passive"))
    )
    (net (code "159") (name "Net-(D123-A)") (class "Default")
      (node (ref "D123") (pin "1") (pinfunction "A_1") (pintype "passive"))
      (node (ref "SW70") (pin "1") (pintype "passive"))
    )
    (net (code "160") (name "Net-(D124-A)") (class "Default")
      (node (ref "D124") (pin "1") (pinfunction "A_1") (pintype "passive"))
      (node (ref "SW71") (pin "1") (pintype "passive"))
    )
    (net (code "161") (name "Net-(D125-A)") (class "Default")
      (node (ref "D125") (pin "1") (pinfunction "A_1") (pintype "passive"))
      (node (ref "SW72") (pin "1") (pintype "passive"))
    )
    (net (code "162") (name "Net-(D136-A)") (class "Default")
      (node (ref "D136") (pin "1") (pinfunction "A_1") (pintype "passive"))
      (node (ref "SW73") (pin "1") (pintype "passive"))
    )
    (net (code "163") (name "Net-(D137-A)") (class "Default")
      (node (ref "D137") (pin "1") (pinfunction "A_1") (pintype "passive"))
      (node (ref "SW74") (pin "1") (pintype "passive"))
    )
    (net (code "164") (name "Net-(D138-A)") (class "Default")
      (node (ref "D138") (pin "1") (pinfunction "A_1") (pintype "passive"))
      (node (ref "SW75") (pin "1") (pintype "passive"))
    )
    (net (code "165") (name "Net-(D139-A)") (class "Default")
      (node (ref "D139") (pin "1") (pinfunction "A_1") (pintype "passive"))
      (node (ref "SW76") (pin "1") (pintype "passive"))
    )
    (net (code "166") (name "Net-(D140-A)") (class "Default")
      (node (ref "D140") (pin "1") (pinfunction "A_1") (pintype "passive"))
      (node (ref "SW77") (pin "1") (pintype "passive"))
    )
    (net (code "167") (name "Net-(D141-A)") (class "Default")
      (node (ref "D141") (pin "1") (pinfunction "A_1") (pintype "passive"))
      (node (ref "SW78") (pin "1") (pintype "passive"))
    )
    (net (code "168") (name "Net-(D142-A)") (class "Default")
      (node (ref "D142") (pin "1") (pinfunction "A_1") (pintype "passive"))
      (node (ref "SW79") (pin "1") (pintype "passive"))
    )
    (net (code "169") (name "Net-(D143-A)") (class "Default")
      (node (ref "D143") (pin "1") (pinfunction "A_1") (pintype "passive"))
      (node (ref "SW80") (pin "1") (pintype "passive"))
    )
    (net (code "170") (name "Net-(D144-A)") (class "Default")
      (node (ref "D144") (pin "1") (pinfunction "A_1") (pintype "passive"))
      (node (ref "SW81") (pin "1") (pintype "passive"))
    )
    (net (code "171") (name "Net-(D145-A)") (class "Default")
      (node (ref "D145") (pin "1") (pinfunction "A_1") (pintype "passive"))
      (node (ref "SW82") (pin "1") (pintype "passive"))
    )
    (net (code "172") (name "Net-(D146-A)") (class "Default")
      (node (ref "D146") (pin "1") (pinfunction "A_1") (pintype "passive"))
      (node (ref "SW83") (pin "1") (pintype "passive"))
    )
    (net (code "173") (name "Net-(D147-A)") (class "Default")
      (node (ref "D147") (pin "1") (pinfunction "A_1") (pintype "passive"))
      (node (ref "SW84") (pin "1") (pintype "passive"))
    )
    (net (code "174") (name "Net-(D148-A)") (class "Default")
      (node (ref "D148") (pin "1") (pinfunction "A_1") (pintype "passive"))
      (node (ref "SW85") (pin "1") (pintype "passive"))
    )
    (net (code "175") (name "Net-(D149-A)") (class "Default")
      (node (ref "D149") (pin "1") (pinfunction "A_1") (pintype "passive"))
      (node (ref "SW86") (pin "1") (pintype "passive"))
    )
    (net (code "176") (name "Net-(D150-A)") (class "Default")
      (node (ref "D150") (pin "1") (pinfunction "A_1") (pintype "passive"))
      (node (ref "SW87") (pin "1") (pintype "passive"))
    )
    (net (code "177") (name "Net-(D151-A)") (class "Default")
      (node (ref "D151") (pin "1") (pinfunction "A_1") (pintype "passive"))
      (node (ref "SW88") (pin "1") (pintype "passive"))
    )
    (net (code "178") (name "Net-(D162-A)") (class "Default")
      (node (ref "D162") (pin "1") (pinfunction "A_1") (pintype "passive"))
      (node (ref "SW89") (pin "1") (pintype "passive"))
    )
    (net (code "179") (name "Net-(D163-A)") (class "Default")
      (node (ref "D163") (pin "1") (pinfunction "A_1") (pintype "passive"))
      (node (ref "SW90") (pin "1") (pintype "passive"))
    )
    (net (code "180") (name "Net-(D164-A)") (class "Default")
      (node (ref "D164") (pin "1") (pinfunction "A_1") (pintype "passive"))
      (node (ref "SW91") (pin "1") (pintype "passive"))
    )
    (net (code "181") (name "Net-(D165-A)") (class "Default")
      (node (ref "D165") (pin "1") (pinfunction "A_1") (pintype "passive"))
      (node (ref "SW92") (pin "1") (pintype "passive"))
    )
    (net (code "182") (name "Net-(D166-A)") (class "Default")
      (node (ref "D166") (pin "1") (pinfunction "A_1") (pintype "passive"))
      (node (ref "SW93") (pin "1") (pintype "passive"))
    )
    (net (code "183") (name "Net-(D167-A)") (class "Default")
      (node (ref "D167") (pin "1") (pinfunction "A_1") (pintype "passive"))
      (node (ref "SW94") (pin "1") (pintype "passive"))
    )
    (net (code "184") (name "Net-(D168-A)") (class "Default")
      (node (ref "D168") (pin "1") (pinfunction "A_1") (pintype "passive"))
      (node (ref "SW95") (pin "1") (pintype "passive"))
    )
    (net (code "185") (name "Net-(D169-A)") (class "Default")
      (node (ref "D169") (pin "1") (pinfunction "A_1") (pintype "passive"))
      (node (ref "SW96") (pin "1") (pintype "passive"))
    )
    (net (code "186") (name "Net-(D170-A)") (class "Default")
      (node (ref "D170") (pin "1") (pinfunction "A_1") (pintype "passive"))
      (node (ref "SW97") (pin "1") (pintype "passive"))
    )
    (net (code "187") (name "Net-(D171-A)") (class "Default")
      (node (ref "D171") (pin "1") (pinfunction "A_1") (pintype "passive"))
      (node (ref "SW98") (pin "1") (pintype "passive"))
    )
    (net (code "188") (name "Net-(D172-A)") (class "Default")
      (node (ref "D172") (pin "1") (pinfunction "A_1") (pintype "passive"))
      (node (ref "SW99") (pin "1") (pintype "passive"))
    )
    (net (code "189") (name "Net-(D173-A)") (class "Default")
      (node (ref "D173") (pin "1") (pinfunction "A_1") (pintype "passive"))
      (node (ref "SW100") (pin "1") (pintype "passive"))
    )
    (net (code "190") (name "Net-(D174-A)") (class "Default")
      (node (ref "D174") (pin "1") (pinfunction "A_1") (pintype "passive"))
      (node (ref "SW101") (pin "1") (pintype "passive"))
    )
    (net (code "191") (name "Net-(D175-A)") (class "Default")
      (node (ref "D175") (pin "1") (pinfunction "A_1") (pintype "passive"))
      (node (ref "SW102") (pin "1") (pintype "passive"))
    )
    (net (code "192") (name "Net-(D176-A)") (class "Default")
      (node (ref "D176") (pin "1") (pinfunction "A_1") (pintype "passive"))
      (node (ref "SW103") (pin "1") (pintype "passive"))
    )
    (net (code "193") (name "Net-(D177-A)") (class "Default")
      (node (ref "D177") (pin "1") (pinfunction "A_1") (pintype "passive"))
      (node (ref "SW104") (pin "1") (pintype "passive"))
    )
    (net (code "194") (name "Net-(D221-A)") (class "Default")
      (node (ref "D221") (pin "1") (pinfunction "A_1") (pintype "passive"))
      (node (ref "L1") (pin "2") (pinfunction "2_2") (pintype "passive"))
      (node (ref "Q18") (pin "3") (pinfunction "D_3") (pintype "input"))
    )
    (net (code "195") (name "Net-(R27-Pad2)") (class "Default")
      (node (ref "R27") (pin "2") (pinfunction "2_2") (pintype "passive"))
      (node (ref "SW100") (pin "2") (pintype "passive"))
      (node (ref "SW101") (pin "2") (pintype "passive"))
      (node (ref "SW102") (pin "2") (pintype "passive"))
      (node (ref "SW103") (pin "2") (pintype "passive"))
      (node (ref "SW104") (pin "2") (pintype "passive"))
      (node (ref "SW89") (pin "2") (pintype "passive"))
      (node (ref "SW90") (pin "2") (pintype "passive"))
      (node (ref "SW91") (pin "2") (pintype "passive"))
      (node (ref "SW92") (pin "2") (pintype "passive"))
      (node (ref "SW93") (pin "2") (pintype "passive"))
      (node (ref "SW94") (pin "2") (pintype "passive"))
      (node (ref "SW95") (pin "2") (pintype "passive"))
      (node (ref "SW96") (pin "2") (pintype "passive"))
      (node (ref "SW97") (pin "2") (pintype "passive"))
      (node (ref "SW98") (pin "2") (pintype "passive"))
      (node (ref "SW99") (pin "2") (pintype "passive"))
    )
    (net (code "196") (name "Net-(R28-Pad2)") (class "Default")
      (node (ref "R28") (pin "2") (pinfunction "2_2") (pintype "passive"))
      (node (ref "SW73") (pin "2") (pintype "passive"))
      (node (ref "SW74") (pin "2") (pintype "passive"))
      (node (ref "SW75") (pin "2") (pintype "passive"))
      (node (ref "SW76") (pin "2") (pintype "passive"))
      (node (ref "SW77") (pin "2") (pintype "passive"))
      (node (ref "SW78") (pin "2") (pintype "passive"))
      (node (ref "SW79") (pin "2") (pintype "passive"))
      (node (ref "SW80") (pin "2") (pintype "passive"))
      (node (ref "SW81") (pin "2") (pintype "passive"))
      (node (ref "SW82") (pin "2") (pintype "passive"))
      (node (ref "SW83") (pin "2") (pintype "passive"))
      (node (ref "SW84") (pin "2") (pintype "passive"))
      (node (ref "SW85") (pin "2") (pintype "passive"))
      (node (ref "SW86") (pin "2") (pintype "passive"))
      (node (ref "SW87") (pin "2") (pintype "passive"))
      (node (ref "SW88") (pin "2") (pintype "passive"))
    )
    (net (code "197") (name "Net-(R29-Pad2)") (class "Default")
      (node (ref "R29") (pin "2") (pinfunction "2_2") (pintype "passive"))
      (node (ref "SW57") (pin "2") (pintype "passive"))
      (node (ref "SW58") (pin "2") (pintype "passive"))
      (node (ref "SW59") (pin "2") (pintype "passive"))
      (node (ref "SW60") (pin "2") (pintype "passive"))
      (node (ref "SW61") (pin "2") (pintype "passive"))
      (node (ref "SW62") (pin "2") (pintype "passive"))
      (node (ref "SW63") (pin "2") (pintype "passive"))
      (node (ref "SW64") (pin "2") (pintype "passive"))
      (node (ref "SW65") (pin "2") (pintype "passive"))
      (node (ref "SW66") (pin "2") (pintype "passive"))
      (node (ref "SW67") (pin "2") (pintype "passive"))
      (node (ref "SW68") (pin "2") (pintype "passive"))
      (node (ref "SW69") (pin "2") (pintype "passive"))
      (node (ref "SW70") (pin "2") (pintype "passive"))
      (node (ref "SW71") (pin "2") (pintype "passive"))
      (node (ref "SW72") (pin "2") (pintype "passive"))
    )
    (net (code "198") (name "Net-(R30-Pad2)") (class "Default")
      (node (ref "R30") (pin "2") (pinfunction "2_2") (pintype "passive"))
      (node (ref "SW42") (pin "2") (pintype "passive"))
      (node (ref "SW43") (pin "2") (pintype "passive"))
      (node (ref "SW44") (pin "2") (pintype "passive"))
      (node (ref "SW45") (pin "2") (pintype "passive"))
      (node (ref "SW46") (pin "2") (pintype "passive"))
      (node (ref "SW47") (pin "2") (pintype "passive"))
      (node (ref "SW48") (pin "2") (pintype "passive"))
      (node (ref "SW49") (pin "2") (pintype "passive"))
      (node (ref "SW50") (pin "2") (pintype "passive"))
      (node (ref "SW51") (pin "2") (pintype "passive"))
      (node (ref "SW52") (pin "2") (pintype "passive"))
      (node (ref "SW53") (pin "2") (pintype "passive"))
      (node (ref "SW54") (pin "2") (pintype "passive"))
      (node (ref "SW55") (pin "2") (pintype "passive"))
      (node (ref "SW56") (pin "2") (pintype "passive"))
    )
    (net (code "199") (name "Net-(R31-Pad2)") (class "Default")
      (node (ref "R31") (pin "2") (pinfunction "2_2") (pintype "passive"))
      (node (ref "SW29") (pin "2") (pintype "passive"))
      (node (ref "SW30") (pin "2") (pintype "passive"))
      (node (ref "SW31") (pin "2") (pintype "passive"))
      (node (ref "SW32") (pin "2") (pintype "passive"))
      (node (ref "SW33") (pin "2") (pintype "passive"))
      (node (ref "SW34") (pin "2") (pintype "passive"))
      (node (ref "SW35") (pin "2") (pintype "passive"))
      (node (ref "SW36") (pin "2") (pintype "passive"))
      (node (ref "SW37") (pin "2") (pintype "passive"))
      (node (ref "SW38") (pin "2") (pintype "passive"))
      (node (ref "SW39") (pin "2") (pintype "passive"))
      (node (ref "SW40") (pin "2") (pintype "passive"))
      (node (ref "SW41") (pin "2") (pintype "passive"))
    )
    (net (code "200") (name "Net-(R32-Pad2)") (class "Default")
      (node (ref "R32") (pin "2") (pinfunction "2_2") (pintype "passive"))
      (node (ref "SW16") (pin "2") (pintype "passive"))
      (node (ref "SW17") (pin "2") (pintype "passive"))
      (node (ref "SW18") (pin "2") (pintype "passive"))
      (node (ref "SW19") (pin "2") (pintype "passive"))
      (node (ref "SW20") (pin "2") (pintype "passive"))
      (node (ref "SW21") (pin "2") (pintype "passive"))
      (node (ref "SW22") (pin "2") (pintype "passive"))
      (node (ref "SW23") (pin "2") (pintype "passive"))
      (node (ref "SW24") (pin "2") (pintype "passive"))
      (node (ref "SW25") (pin "2") (pintype "passive"))
      (node (ref "SW26") (pin "2") (pintype "passive"))
      (node (ref "SW27") (pin "2") (pintype "passive"))
      (node (ref "SW28") (pin "2") (pintype "passive"))
    )
    (net (code "201") (name "Net-(R33-Pad2)") (class "Default")
      (node (ref "R33") (pin "2") (pinfunction "2_2") (pintype "passive"))
      (node (ref "SW10") (pin "2") (pintype "passive"))
      (node (ref "SW105") (pin "2") (pintype "passive"))
      (node (ref "SW11") (pin "2") (pintype "passive"))
      (node (ref "SW12") (pin "2") (pintype "passive"))
      (node (ref "SW13") (pin "2") (pintype "passive"))
      (node (ref "SW14") (pin "2") (pintype "passive"))
      (node (ref "SW15") (pin "2") (pintype "passive"))
      (node (ref "SW2") (pin "2") (pintype "passive"))
      (node (ref "SW3") (pin "2") (pintype "passive"))
      (node (ref "SW4") (pin "2") (pintype "passive"))
      (node (ref "SW5") (pin "2") (pintype "passive"))
      (node (ref "SW6") (pin "2") (pintype "passive"))
      (node (ref "SW7") (pin "2") (pintype "passive"))
      (node (ref "SW8") (pin "2") (pintype "passive"))
      (node (ref "SW9") (pin "2") (pintype "passive"))
    )
    (net (code "202") (name "unconnected-(*-P6.4{slash}DCD-Pad3)") (class "Default")
      (node (ref "*") (pin "3") (pinfunction "P6.4/DCD_3") (pintype "bidirectional"))
    )
  )
)
